# RF08indx.net
KiCad netlist of a schematic drawn in EAGLE
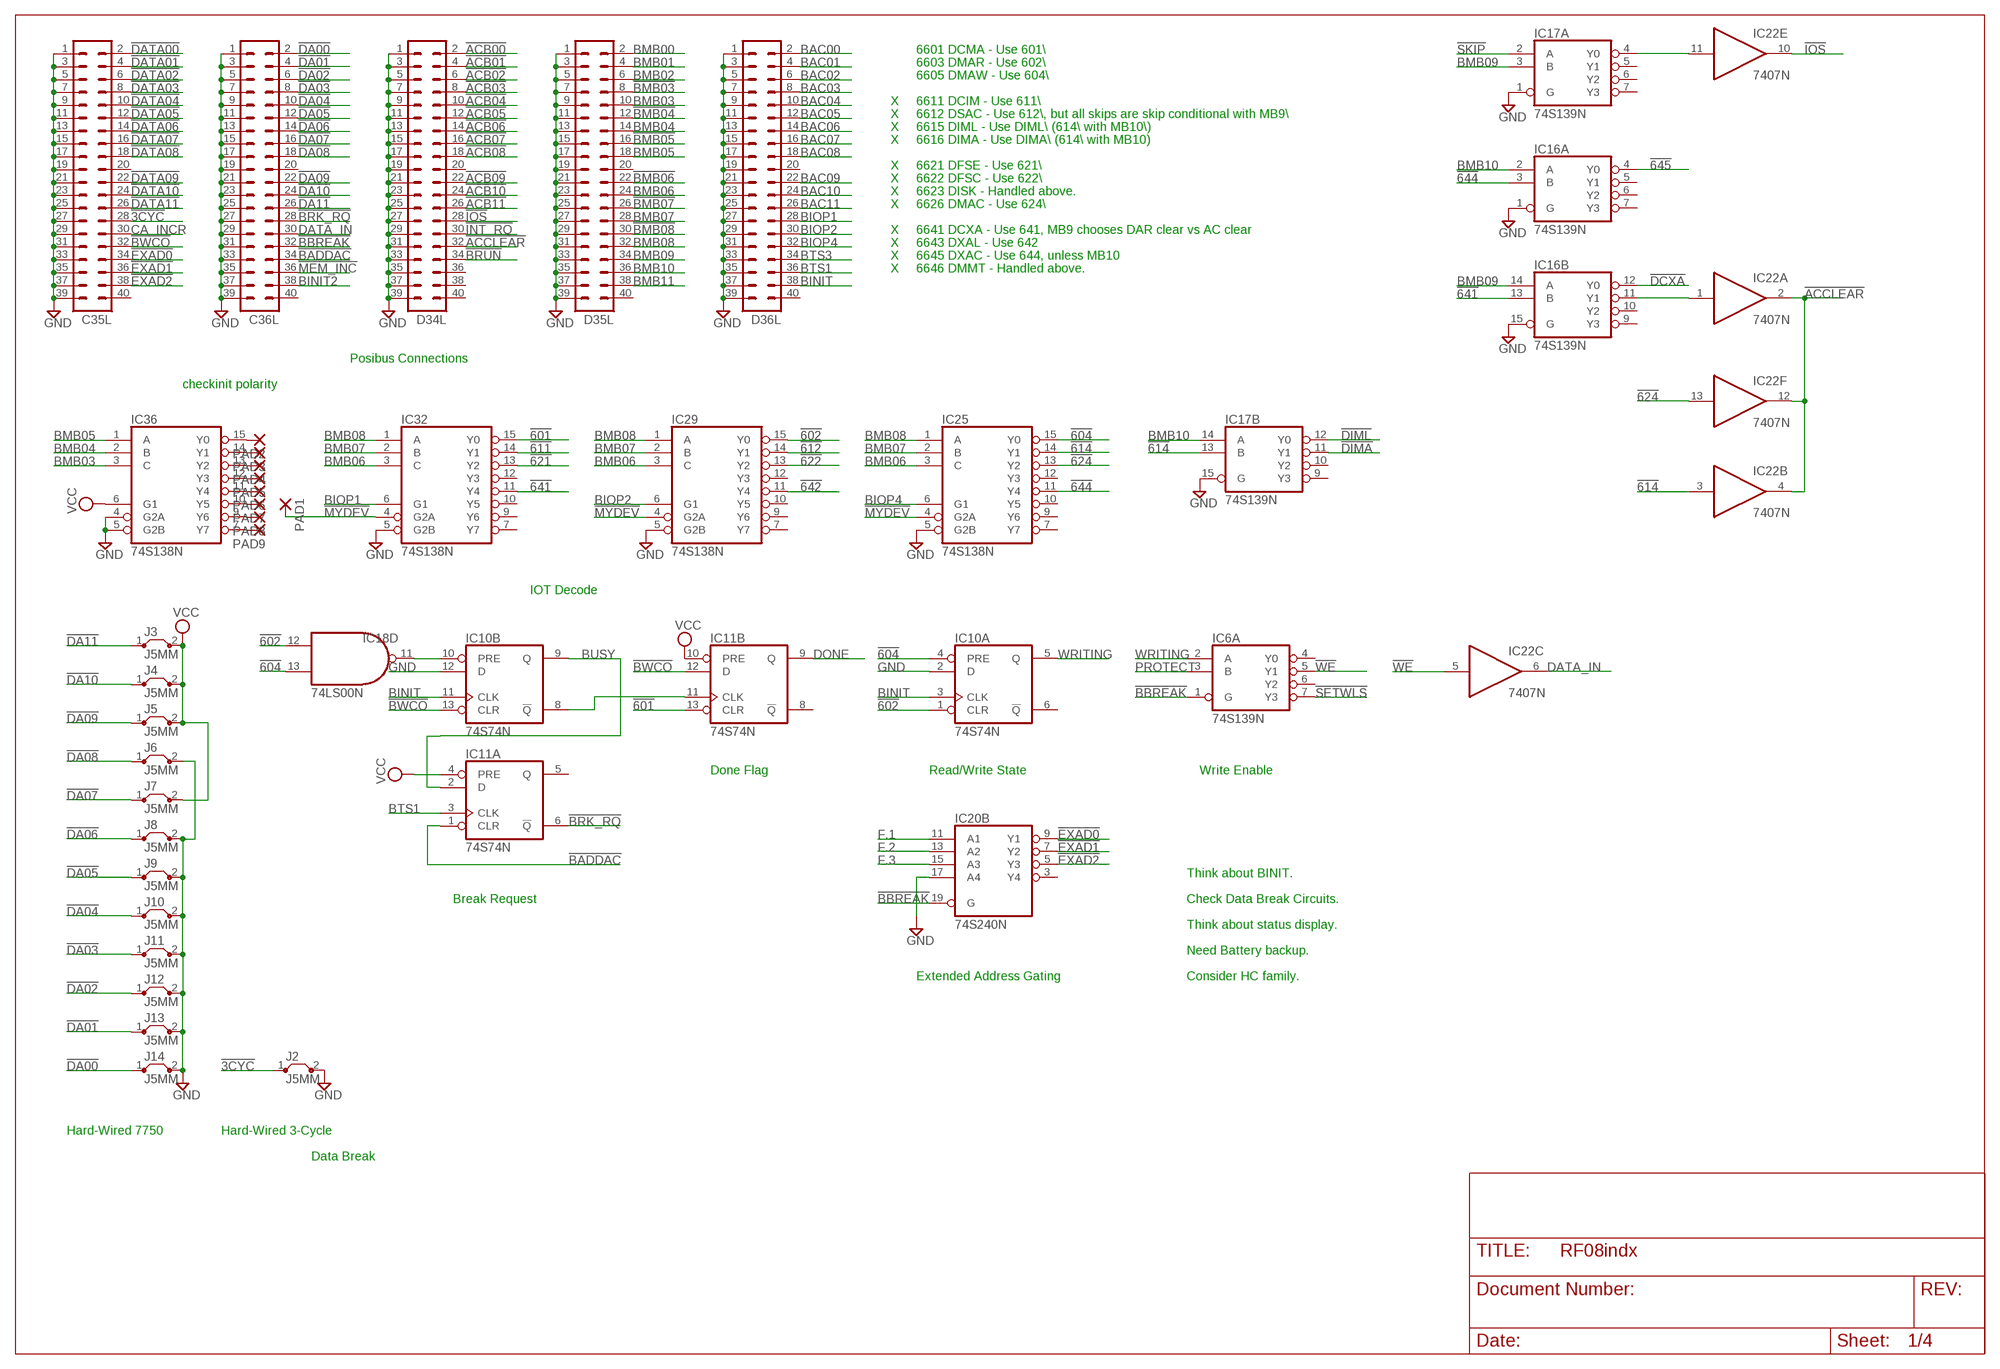
[diagram p0: schematic, sheet 1]
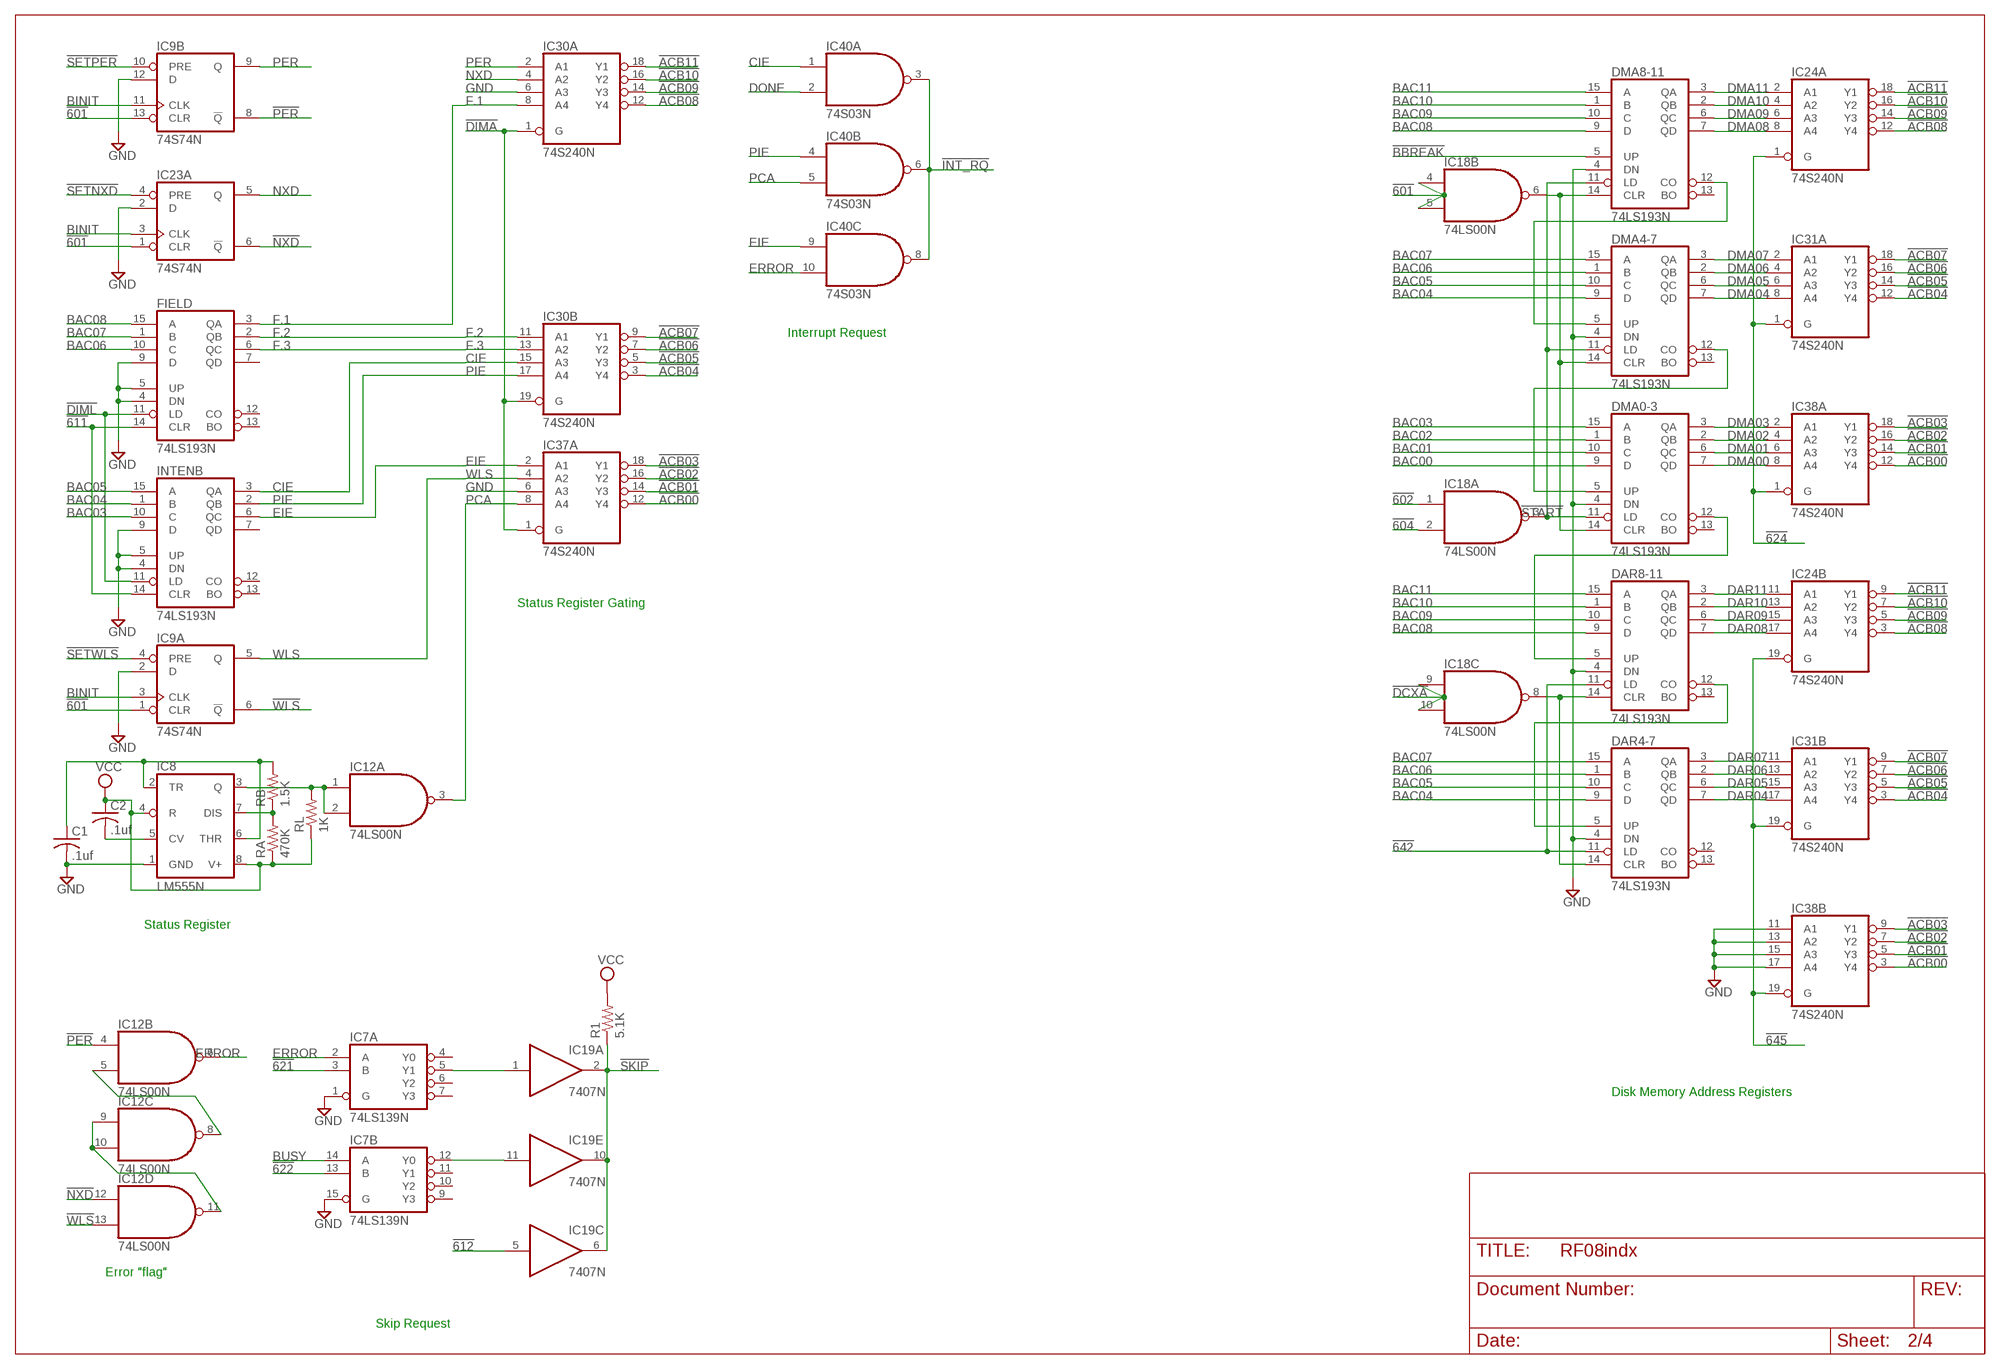
[diagram p1: schematic, sheet 2]
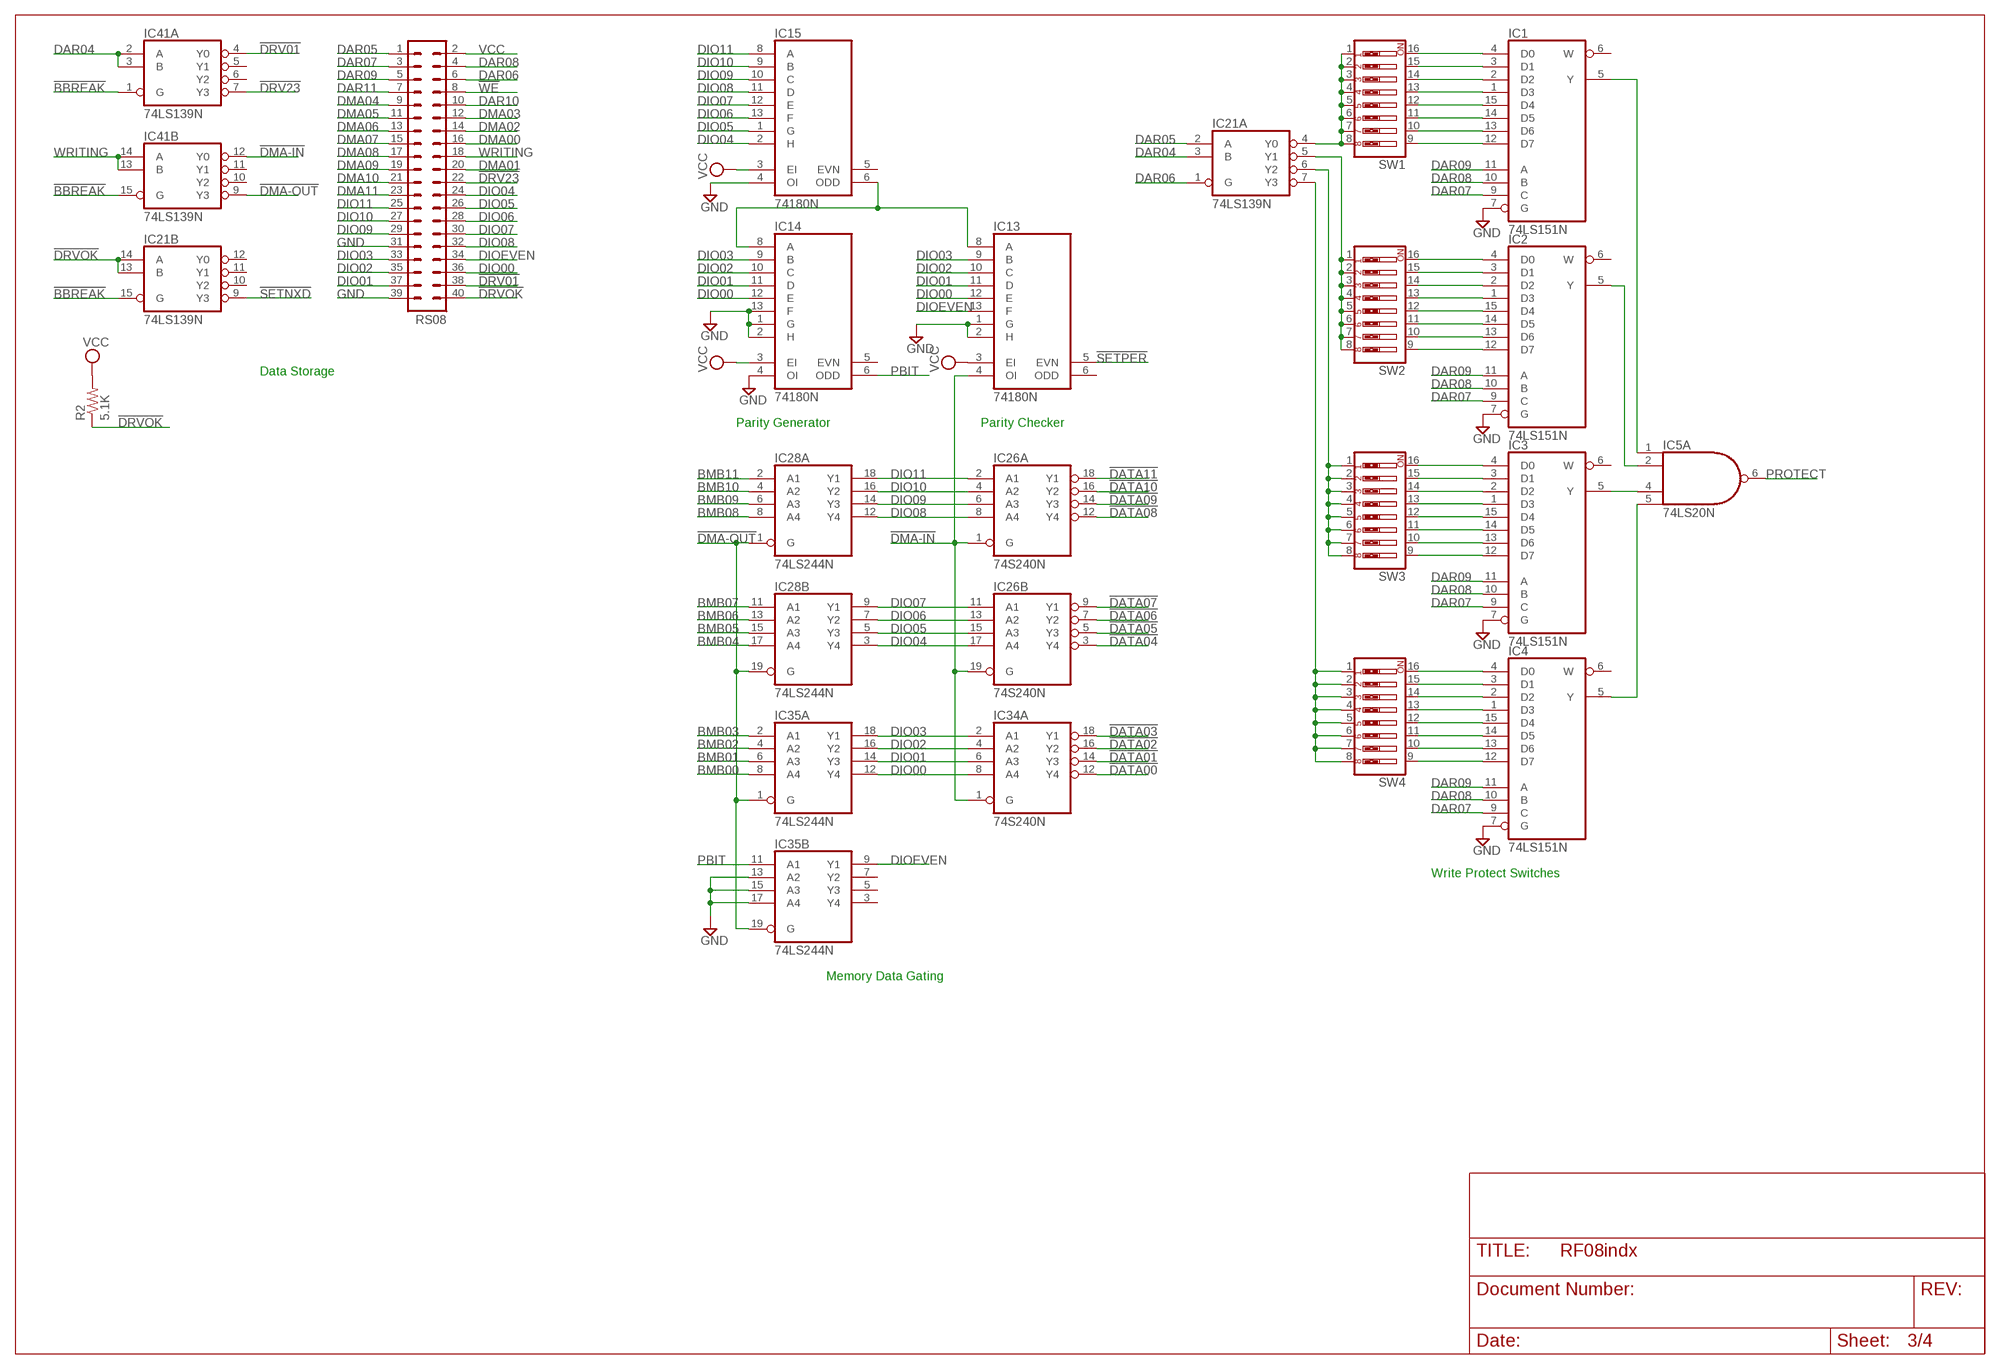
[diagram p2: schematic, sheet 3]
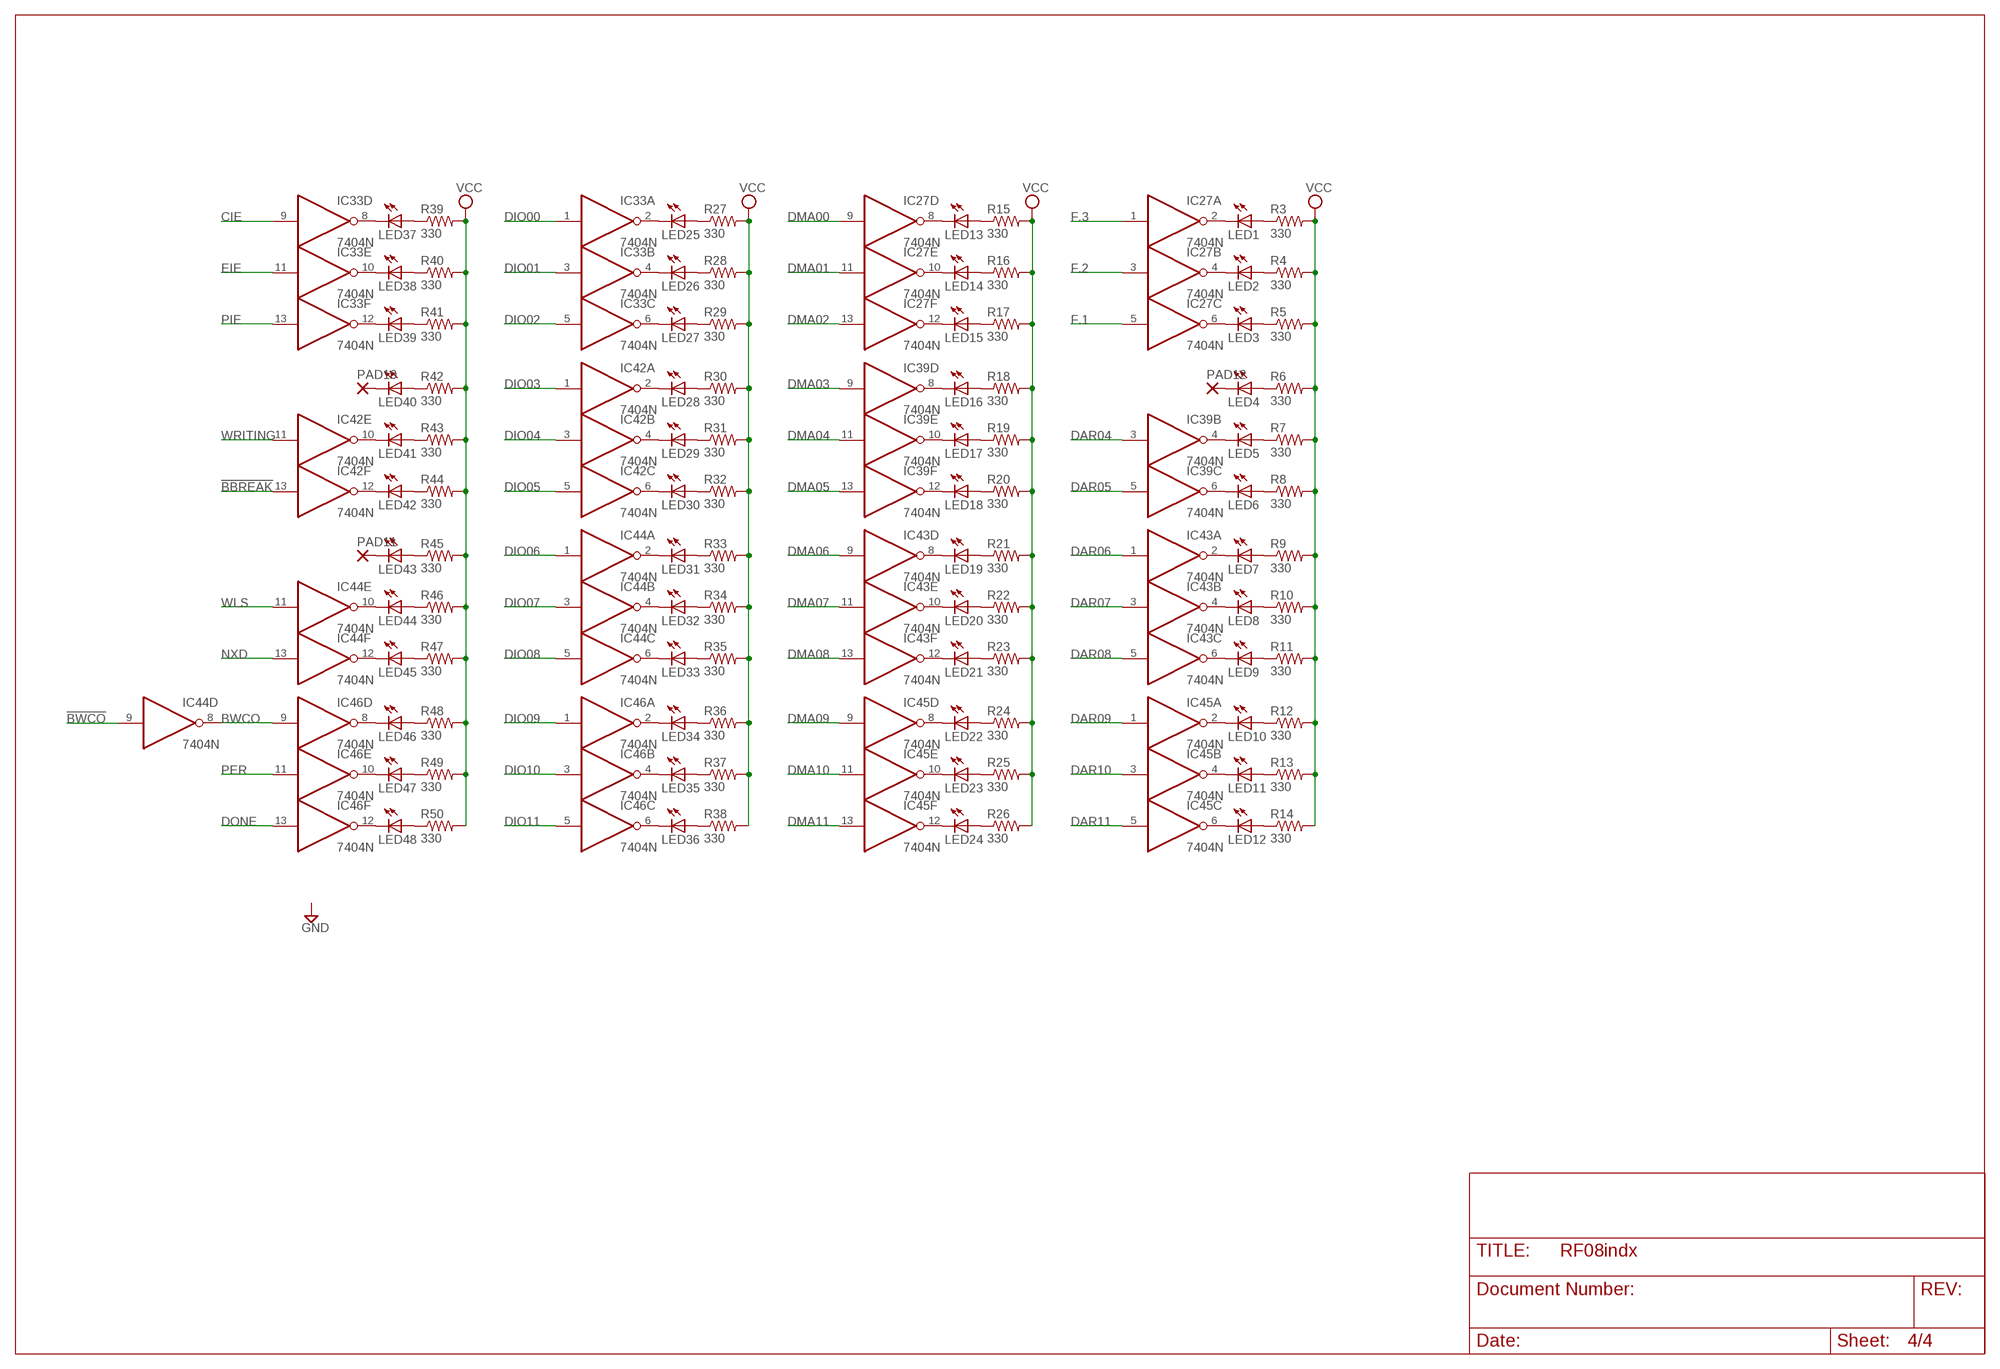
[diagram p3: schematic, sheet 4]

(export (version "E")
  (design (tool "Eeschema 10.0.6"))
  (components
    (comp (ref "C1")
      (value ".1uf")
      (footprint "eagle-import:C050-025X075")
      (libsource (lib "eagle-import") (part "C-US050-025X075"))
    )
    (comp (ref "C2")
      (value ".1uf")
      (footprint "eagle-import:C050-025X075")
      (libsource (lib "eagle-import") (part "C-US050-025X075"))
    )
    (comp (ref "DAR4-7")
      (value "74LS193N")
      (footprint "eagle-import:DIL16")
      (libsource (lib "eagle-import") (part "74192NLS"))
    )
    (comp (ref "DAR8-11")
      (value "74LS193N")
      (footprint "eagle-import:DIL16")
      (libsource (lib "eagle-import") (part "74192NLS"))
    )
    (comp (ref "DMA0-3")
      (value "74LS193N")
      (footprint "eagle-import:DIL16")
      (libsource (lib "eagle-import") (part "74192NLS"))
    )
    (comp (ref "DMA4-7")
      (value "74LS193N")
      (footprint "eagle-import:DIL16")
      (libsource (lib "eagle-import") (part "74192NLS"))
    )
    (comp (ref "DMA8-11")
      (value "74LS193N")
      (footprint "eagle-import:DIL16")
      (libsource (lib "eagle-import") (part "74192NLS"))
    )
    (comp (ref "FIELD")
      (value "74LS193N")
      (footprint "eagle-import:DIL16")
      (libsource (lib "eagle-import") (part "74192NLS"))
    )
    (comp (ref "IC7")
      (value "74LS139N")
      (footprint "eagle-import:DIL16")
      (libsource (lib "eagle-import") (part "74139NLS"))
    )
    (comp (ref "IC8")
      (value "LM555N")
      (footprint "eagle-import:DIL08")
      (libsource (lib "eagle-import") (part "555NLM"))
    )
    (comp (ref "IC9")
      (value "74S74N")
      (footprint "eagle-import:DIL14")
      (libsource (lib "eagle-import") (part "7474NS"))
    )
    (comp (ref "IC12")
      (value "74LS00N")
      (footprint "eagle-import:DIL14")
      (libsource (lib "eagle-import") (part "7400NLS"))
    )
    (comp (ref "IC18")
      (value "74LS00N")
      (footprint "eagle-import:DIL14")
      (libsource (lib "eagle-import") (part "7400NLS"))
    )
    (comp (ref "IC19")
      (value "7407N")
      (footprint "eagle-import:DIL14")
      (libsource (lib "eagle-import") (part "7407N"))
    )
    (comp (ref "IC23")
      (value "74S74N")
      (footprint "eagle-import:DIL14")
      (libsource (lib "eagle-import") (part "7474NS"))
    )
    (comp (ref "IC24")
      (value "74S240N")
      (footprint "eagle-import:DIL20")
      (libsource (lib "eagle-import") (part "74240NS"))
    )
    (comp (ref "IC30")
      (value "74S240N")
      (footprint "eagle-import:DIL20")
      (libsource (lib "eagle-import") (part "74240NS"))
    )
    (comp (ref "IC31")
      (value "74S240N")
      (footprint "eagle-import:DIL20")
      (libsource (lib "eagle-import") (part "74240NS"))
    )
    (comp (ref "IC37")
      (value "74S240N")
      (footprint "eagle-import:DIL20")
      (libsource (lib "eagle-import") (part "74240NS"))
    )
    (comp (ref "IC38")
      (value "74S240N")
      (footprint "eagle-import:DIL20")
      (libsource (lib "eagle-import") (part "74240NS"))
    )
    (comp (ref "IC40")
      (value "74S03N")
      (footprint "eagle-import:DIL14")
      (libsource (lib "eagle-import") (part "7403NS"))
    )
    (comp (ref "INTENB")
      (value "74LS193N")
      (footprint "eagle-import:DIL16")
      (libsource (lib "eagle-import") (part "74192NLS"))
    )
    (comp (ref "R1")
      (value "5.1K")
      (footprint "eagle-import:0207_10")
      (libsource (lib "eagle-import") (part "R-US_0207/10"))
    )
    (comp (ref "RA")
      (value "470K")
      (footprint "eagle-import:0207_10")
      (libsource (lib "eagle-import") (part "R-US_0207/10"))
    )
    (comp (ref "RB")
      (value "1.5K")
      (footprint "eagle-import:0207_10")
      (libsource (lib "eagle-import") (part "R-US_0207/10"))
    )
    (comp (ref "RL")
      (value "1K")
      (footprint "eagle-import:0207_10")
      (libsource (lib "eagle-import") (part "R-US_0207/10"))
    )
    (comp (ref "C35L")
      (value "MA20-2")
      (footprint "eagle-import:MA20-2")
      (libsource (lib "eagle-import") (part "MA20-2"))
    )
    (comp (ref "C36L")
      (value "MA20-2")
      (footprint "eagle-import:MA20-2")
      (libsource (lib "eagle-import") (part "MA20-2"))
    )
    (comp (ref "D34L")
      (value "MA20-2")
      (footprint "eagle-import:MA20-2")
      (libsource (lib "eagle-import") (part "MA20-2"))
    )
    (comp (ref "D35L")
      (value "MA20-2")
      (footprint "eagle-import:MA20-2")
      (libsource (lib "eagle-import") (part "MA20-2"))
    )
    (comp (ref "D36L")
      (value "MA20-2")
      (footprint "eagle-import:MA20-2")
      (libsource (lib "eagle-import") (part "MA20-2"))
    )
    (comp (ref "IC6")
      (value "74S139N")
      (footprint "eagle-import:DIL16")
      (libsource (lib "eagle-import") (part "74139NS"))
    )
    (comp (ref "IC10")
      (value "74S74N")
      (footprint "eagle-import:DIL14")
      (libsource (lib "eagle-import") (part "7474NS"))
    )
    (comp (ref "IC11")
      (value "74S74N")
      (footprint "eagle-import:DIL14")
      (libsource (lib "eagle-import") (part "7474NS"))
    )
    (comp (ref "IC16")
      (value "74S139N")
      (footprint "eagle-import:DIL16")
      (libsource (lib "eagle-import") (part "74139NS"))
    )
    (comp (ref "IC17")
      (value "74S139N")
      (footprint "eagle-import:DIL16")
      (libsource (lib "eagle-import") (part "74139NS"))
    )
    (comp (ref "IC20")
      (value "74S240N")
      (footprint "eagle-import:DIL20")
      (libsource (lib "eagle-import") (part "74240NS"))
    )
    (comp (ref "IC22")
      (value "7407N")
      (footprint "eagle-import:DIL14")
      (libsource (lib "eagle-import") (part "7407N"))
    )
    (comp (ref "IC25")
      (value "74S138N")
      (footprint "eagle-import:DIL16")
      (libsource (lib "eagle-import") (part "74138NS"))
    )
    (comp (ref "IC29")
      (value "74S138N")
      (footprint "eagle-import:DIL16")
      (libsource (lib "eagle-import") (part "74138NS"))
    )
    (comp (ref "IC32")
      (value "74S138N")
      (footprint "eagle-import:DIL16")
      (libsource (lib "eagle-import") (part "74138NS"))
    )
    (comp (ref "IC36")
      (value "74S138N")
      (footprint "eagle-import:DIL16")
      (libsource (lib "eagle-import") (part "74138NS"))
    )
    (comp (ref "J2")
      (value "J5MM")
      (footprint "eagle-import:05")
      (libsource (lib "eagle-import") (part "J5MM"))
    )
    (comp (ref "J3")
      (value "J5MM")
      (footprint "eagle-import:05")
      (libsource (lib "eagle-import") (part "J5MM"))
    )
    (comp (ref "J4")
      (value "J5MM")
      (footprint "eagle-import:05")
      (libsource (lib "eagle-import") (part "J5MM"))
    )
    (comp (ref "J5")
      (value "J5MM")
      (footprint "eagle-import:05")
      (libsource (lib "eagle-import") (part "J5MM"))
    )
    (comp (ref "J6")
      (value "J5MM")
      (footprint "eagle-import:05")
      (libsource (lib "eagle-import") (part "J5MM"))
    )
    (comp (ref "J7")
      (value "J5MM")
      (footprint "eagle-import:05")
      (libsource (lib "eagle-import") (part "J5MM"))
    )
    (comp (ref "J8")
      (value "J5MM")
      (footprint "eagle-import:05")
      (libsource (lib "eagle-import") (part "J5MM"))
    )
    (comp (ref "J9")
      (value "J5MM")
      (footprint "eagle-import:05")
      (libsource (lib "eagle-import") (part "J5MM"))
    )
    (comp (ref "J10")
      (value "J5MM")
      (footprint "eagle-import:05")
      (libsource (lib "eagle-import") (part "J5MM"))
    )
    (comp (ref "J11")
      (value "J5MM")
      (footprint "eagle-import:05")
      (libsource (lib "eagle-import") (part "J5MM"))
    )
    (comp (ref "J12")
      (value "J5MM")
      (footprint "eagle-import:05")
      (libsource (lib "eagle-import") (part "J5MM"))
    )
    (comp (ref "J13")
      (value "J5MM")
      (footprint "eagle-import:05")
      (libsource (lib "eagle-import") (part "J5MM"))
    )
    (comp (ref "J14")
      (value "J5MM")
      (footprint "eagle-import:05")
      (libsource (lib "eagle-import") (part "J5MM"))
    )
    (comp (ref "PAD1")
      (value "1,6/0,8")
      (footprint "eagle-import:1,6_0,8")
      (libsource (lib "eagle-import") (part "1,6/0,8"))
    )
    (comp (ref "PAD2")
      (value "1,6/0,8")
      (footprint "eagle-import:1,6_0,8")
      (libsource (lib "eagle-import") (part "1,6/0,8"))
    )
    (comp (ref "PAD3")
      (value "1,6/0,8")
      (footprint "eagle-import:1,6_0,8")
      (libsource (lib "eagle-import") (part "1,6/0,8"))
    )
    (comp (ref "PAD4")
      (value "1,6/0,8")
      (footprint "eagle-import:1,6_0,8")
      (libsource (lib "eagle-import") (part "1,6/0,8"))
    )
    (comp (ref "PAD5")
      (value "1,6/0,8")
      (footprint "eagle-import:1,6_0,8")
      (libsource (lib "eagle-import") (part "1,6/0,8"))
    )
    (comp (ref "PAD6")
      (value "1,6/0,8")
      (footprint "eagle-import:1,6_0,8")
      (libsource (lib "eagle-import") (part "1,6/0,8"))
    )
    (comp (ref "PAD7")
      (value "1,6/0,8")
      (footprint "eagle-import:1,6_0,8")
      (libsource (lib "eagle-import") (part "1,6/0,8"))
    )
    (comp (ref "PAD8")
      (value "1,6/0,8")
      (footprint "eagle-import:1,6_0,8")
      (libsource (lib "eagle-import") (part "1,6/0,8"))
    )
    (comp (ref "PAD9")
      (value "1,6/0,8")
      (footprint "eagle-import:1,6_0,8")
      (libsource (lib "eagle-import") (part "1,6/0,8"))
    )
    (comp (ref "IC1")
      (value "74LS151N")
      (footprint "eagle-import:DIL16")
      (libsource (lib "eagle-import") (part "74151NLS"))
    )
    (comp (ref "IC2")
      (value "74LS151N")
      (footprint "eagle-import:DIL16")
      (libsource (lib "eagle-import") (part "74151NLS"))
    )
    (comp (ref "IC3")
      (value "74LS151N")
      (footprint "eagle-import:DIL16")
      (libsource (lib "eagle-import") (part "74151NLS"))
    )
    (comp (ref "IC4")
      (value "74LS151N")
      (footprint "eagle-import:DIL16")
      (libsource (lib "eagle-import") (part "74151NLS"))
    )
    (comp (ref "IC5")
      (value "74LS20N")
      (footprint "eagle-import:DIL14")
      (libsource (lib "eagle-import") (part "7420NLS"))
    )
    (comp (ref "IC13")
      (value "74180N")
      (footprint "eagle-import:DIL14")
      (libsource (lib "eagle-import") (part "74180N"))
    )
    (comp (ref "IC14")
      (value "74180N")
      (footprint "eagle-import:DIL14")
      (libsource (lib "eagle-import") (part "74180N"))
    )
    (comp (ref "IC15")
      (value "74180N")
      (footprint "eagle-import:DIL14")
      (libsource (lib "eagle-import") (part "74180N"))
    )
    (comp (ref "IC21")
      (value "74LS139N")
      (footprint "eagle-import:DIL16")
      (libsource (lib "eagle-import") (part "74139NLS"))
    )
    (comp (ref "IC26")
      (value "74S240N")
      (footprint "eagle-import:DIL20")
      (libsource (lib "eagle-import") (part "74240NS"))
    )
    (comp (ref "IC28")
      (value "74LS244N")
      (footprint "eagle-import:DIL20")
      (libsource (lib "eagle-import") (part "74244NLS"))
    )
    (comp (ref "IC34")
      (value "74S240N")
      (footprint "eagle-import:DIL20")
      (libsource (lib "eagle-import") (part "74240NS"))
    )
    (comp (ref "IC35")
      (value "74LS244N")
      (footprint "eagle-import:DIL20")
      (libsource (lib "eagle-import") (part "74244NLS"))
    )
    (comp (ref "IC41")
      (value "74LS139N")
      (footprint "eagle-import:DIL16")
      (libsource (lib "eagle-import") (part "74139NLS"))
    )
    (comp (ref "R2")
      (value "5.1K")
      (footprint "eagle-import:0207_10")
      (libsource (lib "eagle-import") (part "R-US_0207/10"))
    )
    (comp (ref "RS08")
      (value "MA20-2")
      (footprint "eagle-import:MA20-2")
      (libsource (lib "eagle-import") (part "MA20-2"))
    )
    (comp (ref "SW1")
      (value "SW_DIP-8")
      (footprint "eagle-import:EDG-08")
      (libsource (lib "eagle-import") (part "SW_DIP-8"))
    )
    (comp (ref "SW2")
      (value "SW_DIP-8")
      (footprint "eagle-import:EDG-08")
      (libsource (lib "eagle-import") (part "SW_DIP-8"))
    )
    (comp (ref "SW3")
      (value "SW_DIP-8")
      (footprint "eagle-import:EDG-08")
      (libsource (lib "eagle-import") (part "SW_DIP-8"))
    )
    (comp (ref "SW4")
      (value "SW_DIP-8")
      (footprint "eagle-import:EDG-08")
      (libsource (lib "eagle-import") (part "SW_DIP-8"))
    )
    (comp (ref "IC27")
      (value "7404N")
      (footprint "eagle-import:DIL14")
      (libsource (lib "eagle-import") (part "7404N"))
    )
    (comp (ref "IC33")
      (value "7404N")
      (footprint "eagle-import:DIL14")
      (libsource (lib "eagle-import") (part "7404N"))
    )
    (comp (ref "IC39")
      (value "7404N")
      (footprint "eagle-import:DIL14")
      (libsource (lib "eagle-import") (part "7404N"))
    )
    (comp (ref "IC42")
      (value "7404N")
      (footprint "eagle-import:DIL14")
      (libsource (lib "eagle-import") (part "7404N"))
    )
    (comp (ref "IC43")
      (value "7404N")
      (footprint "eagle-import:DIL14")
      (libsource (lib "eagle-import") (part "7404N"))
    )
    (comp (ref "IC44")
      (value "7404N")
      (footprint "eagle-import:DIL14")
      (libsource (lib "eagle-import") (part "7404N"))
    )
    (comp (ref "IC45")
      (value "7404N")
      (footprint "eagle-import:DIL14")
      (libsource (lib "eagle-import") (part "7404N"))
    )
    (comp (ref "IC46")
      (value "7404N")
      (footprint "eagle-import:DIL14")
      (libsource (lib "eagle-import") (part "7404N"))
    )
    (comp (ref "LED1")
      (value "LED5MM")
      (footprint "eagle-import:LED5MM")
      (libsource (lib "eagle-import") (part "LED5MM"))
    )
    (comp (ref "LED2")
      (value "LED5MM")
      (footprint "eagle-import:LED5MM")
      (libsource (lib "eagle-import") (part "LED5MM"))
    )
    (comp (ref "LED3")
      (value "LED5MM")
      (footprint "eagle-import:LED5MM")
      (libsource (lib "eagle-import") (part "LED5MM"))
    )
    (comp (ref "LED4")
      (value "LED5MM")
      (footprint "eagle-import:LED5MM")
      (libsource (lib "eagle-import") (part "LED5MM"))
    )
    (comp (ref "LED5")
      (value "LED5MM")
      (footprint "eagle-import:LED5MM")
      (libsource (lib "eagle-import") (part "LED5MM"))
    )
    (comp (ref "LED6")
      (value "LED5MM")
      (footprint "eagle-import:LED5MM")
      (libsource (lib "eagle-import") (part "LED5MM"))
    )
    (comp (ref "LED7")
      (value "LED5MM")
      (footprint "eagle-import:LED5MM")
      (libsource (lib "eagle-import") (part "LED5MM"))
    )
    (comp (ref "LED8")
      (value "LED5MM")
      (footprint "eagle-import:LED5MM")
      (libsource (lib "eagle-import") (part "LED5MM"))
    )
    (comp (ref "LED9")
      (value "LED5MM")
      (footprint "eagle-import:LED5MM")
      (libsource (lib "eagle-import") (part "LED5MM"))
    )
    (comp (ref "LED10")
      (value "LED5MM")
      (footprint "eagle-import:LED5MM")
      (libsource (lib "eagle-import") (part "LED5MM"))
    )
    (comp (ref "LED11")
      (value "LED5MM")
      (footprint "eagle-import:LED5MM")
      (libsource (lib "eagle-import") (part "LED5MM"))
    )
    (comp (ref "LED12")
      (value "LED5MM")
      (footprint "eagle-import:LED5MM")
      (libsource (lib "eagle-import") (part "LED5MM"))
    )
    (comp (ref "LED13")
      (value "LED5MM")
      (footprint "eagle-import:LED5MM")
      (libsource (lib "eagle-import") (part "LED5MM"))
    )
    (comp (ref "LED14")
      (value "LED5MM")
      (footprint "eagle-import:LED5MM")
      (libsource (lib "eagle-import") (part "LED5MM"))
    )
    (comp (ref "LED15")
      (value "LED5MM")
      (footprint "eagle-import:LED5MM")
      (libsource (lib "eagle-import") (part "LED5MM"))
    )
    (comp (ref "LED16")
      (value "LED5MM")
      (footprint "eagle-import:LED5MM")
      (libsource (lib "eagle-import") (part "LED5MM"))
    )
    (comp (ref "LED17")
      (value "LED5MM")
      (footprint "eagle-import:LED5MM")
      (libsource (lib "eagle-import") (part "LED5MM"))
    )
    (comp (ref "LED18")
      (value "LED5MM")
      (footprint "eagle-import:LED5MM")
      (libsource (lib "eagle-import") (part "LED5MM"))
    )
    (comp (ref "LED19")
      (value "LED5MM")
      (footprint "eagle-import:LED5MM")
      (libsource (lib "eagle-import") (part "LED5MM"))
    )
    (comp (ref "LED20")
      (value "LED5MM")
      (footprint "eagle-import:LED5MM")
      (libsource (lib "eagle-import") (part "LED5MM"))
    )
    (comp (ref "LED21")
      (value "LED5MM")
      (footprint "eagle-import:LED5MM")
      (libsource (lib "eagle-import") (part "LED5MM"))
    )
    (comp (ref "LED22")
      (value "LED5MM")
      (footprint "eagle-import:LED5MM")
      (libsource (lib "eagle-import") (part "LED5MM"))
    )
    (comp (ref "LED23")
      (value "LED5MM")
      (footprint "eagle-import:LED5MM")
      (libsource (lib "eagle-import") (part "LED5MM"))
    )
    (comp (ref "LED24")
      (value "LED5MM")
      (footprint "eagle-import:LED5MM")
      (libsource (lib "eagle-import") (part "LED5MM"))
    )
    (comp (ref "LED25")
      (value "LED5MM")
      (footprint "eagle-import:LED5MM")
      (libsource (lib "eagle-import") (part "LED5MM"))
    )
    (comp (ref "LED26")
      (value "LED5MM")
      (footprint "eagle-import:LED5MM")
      (libsource (lib "eagle-import") (part "LED5MM"))
    )
    (comp (ref "LED27")
      (value "LED5MM")
      (footprint "eagle-import:LED5MM")
      (libsource (lib "eagle-import") (part "LED5MM"))
    )
    (comp (ref "LED28")
      (value "LED5MM")
      (footprint "eagle-import:LED5MM")
      (libsource (lib "eagle-import") (part "LED5MM"))
    )
    (comp (ref "LED29")
      (value "LED5MM")
      (footprint "eagle-import:LED5MM")
      (libsource (lib "eagle-import") (part "LED5MM"))
    )
    (comp (ref "LED30")
      (value "LED5MM")
      (footprint "eagle-import:LED5MM")
      (libsource (lib "eagle-import") (part "LED5MM"))
    )
    (comp (ref "LED31")
      (value "LED5MM")
      (footprint "eagle-import:LED5MM")
      (libsource (lib "eagle-import") (part "LED5MM"))
    )
    (comp (ref "LED32")
      (value "LED5MM")
      (footprint "eagle-import:LED5MM")
      (libsource (lib "eagle-import") (part "LED5MM"))
    )
    (comp (ref "LED33")
      (value "LED5MM")
      (footprint "eagle-import:LED5MM")
      (libsource (lib "eagle-import") (part "LED5MM"))
    )
    (comp (ref "LED34")
      (value "LED5MM")
      (footprint "eagle-import:LED5MM")
      (libsource (lib "eagle-import") (part "LED5MM"))
    )
    (comp (ref "LED35")
      (value "LED5MM")
      (footprint "eagle-import:LED5MM")
      (libsource (lib "eagle-import") (part "LED5MM"))
    )
    (comp (ref "LED36")
      (value "LED5MM")
      (footprint "eagle-import:LED5MM")
      (libsource (lib "eagle-import") (part "LED5MM"))
    )
    (comp (ref "LED37")
      (value "LED5MM")
      (footprint "eagle-import:LED5MM")
      (libsource (lib "eagle-import") (part "LED5MM"))
    )
    (comp (ref "LED38")
      (value "LED5MM")
      (footprint "eagle-import:LED5MM")
      (libsource (lib "eagle-import") (part "LED5MM"))
    )
    (comp (ref "LED39")
      (value "LED5MM")
      (footprint "eagle-import:LED5MM")
      (libsource (lib "eagle-import") (part "LED5MM"))
    )
    (comp (ref "LED40")
      (value "LED5MM")
      (footprint "eagle-import:LED5MM")
      (libsource (lib "eagle-import") (part "LED5MM"))
    )
    (comp (ref "LED41")
      (value "LED5MM")
      (footprint "eagle-import:LED5MM")
      (libsource (lib "eagle-import") (part "LED5MM"))
    )
    (comp (ref "LED42")
      (value "LED5MM")
      (footprint "eagle-import:LED5MM")
      (libsource (lib "eagle-import") (part "LED5MM"))
    )
    (comp (ref "LED43")
      (value "LED5MM")
      (footprint "eagle-import:LED5MM")
      (libsource (lib "eagle-import") (part "LED5MM"))
    )
    (comp (ref "LED44")
      (value "LED5MM")
      (footprint "eagle-import:LED5MM")
      (libsource (lib "eagle-import") (part "LED5MM"))
    )
    (comp (ref "LED45")
      (value "LED5MM")
      (footprint "eagle-import:LED5MM")
      (libsource (lib "eagle-import") (part "LED5MM"))
    )
    (comp (ref "LED46")
      (value "LED5MM")
      (footprint "eagle-import:LED5MM")
      (libsource (lib "eagle-import") (part "LED5MM"))
    )
    (comp (ref "LED47")
      (value "LED5MM")
      (footprint "eagle-import:LED5MM")
      (libsource (lib "eagle-import") (part "LED5MM"))
    )
    (comp (ref "LED48")
      (value "LED5MM")
      (footprint "eagle-import:LED5MM")
      (libsource (lib "eagle-import") (part "LED5MM"))
    )
    (comp (ref "PAD10")
      (value "1,6/0,8")
      (footprint "eagle-import:1,6_0,8")
      (libsource (lib "eagle-import") (part "1,6/0,8"))
    )
    (comp (ref "PAD11")
      (value "1,6/0,8")
      (footprint "eagle-import:1,6_0,8")
      (libsource (lib "eagle-import") (part "1,6/0,8"))
    )
    (comp (ref "PAD12")
      (value "1,6/0,8")
      (footprint "eagle-import:1,6_0,8")
      (libsource (lib "eagle-import") (part "1,6/0,8"))
    )
    (comp (ref "R3")
      (value "330")
      (footprint "eagle-import:0207_10")
      (libsource (lib "eagle-import") (part "R-US_0207/10"))
    )
    (comp (ref "R4")
      (value "330")
      (footprint "eagle-import:0207_10")
      (libsource (lib "eagle-import") (part "R-US_0207/10"))
    )
    (comp (ref "R5")
      (value "330")
      (footprint "eagle-import:0207_10")
      (libsource (lib "eagle-import") (part "R-US_0207/10"))
    )
    (comp (ref "R6")
      (value "330")
      (footprint "eagle-import:0207_10")
      (libsource (lib "eagle-import") (part "R-US_0207/10"))
    )
    (comp (ref "R7")
      (value "330")
      (footprint "eagle-import:0207_10")
      (libsource (lib "eagle-import") (part "R-US_0207/10"))
    )
    (comp (ref "R8")
      (value "330")
      (footprint "eagle-import:0207_10")
      (libsource (lib "eagle-import") (part "R-US_0207/10"))
    )
    (comp (ref "R9")
      (value "330")
      (footprint "eagle-import:0207_10")
      (libsource (lib "eagle-import") (part "R-US_0207/10"))
    )
    (comp (ref "R10")
      (value "330")
      (footprint "eagle-import:0207_10")
      (libsource (lib "eagle-import") (part "R-US_0207/10"))
    )
    (comp (ref "R11")
      (value "330")
      (footprint "eagle-import:0207_10")
      (libsource (lib "eagle-import") (part "R-US_0207/10"))
    )
    (comp (ref "R12")
      (value "330")
      (footprint "eagle-import:0207_10")
      (libsource (lib "eagle-import") (part "R-US_0207/10"))
    )
    (comp (ref "R13")
      (value "330")
      (footprint "eagle-import:0207_10")
      (libsource (lib "eagle-import") (part "R-US_0207/10"))
    )
    (comp (ref "R14")
      (value "330")
      (footprint "eagle-import:0207_10")
      (libsource (lib "eagle-import") (part "R-US_0207/10"))
    )
    (comp (ref "R15")
      (value "330")
      (footprint "eagle-import:0207_10")
      (libsource (lib "eagle-import") (part "R-US_0207/10"))
    )
    (comp (ref "R16")
      (value "330")
      (footprint "eagle-import:0207_10")
      (libsource (lib "eagle-import") (part "R-US_0207/10"))
    )
    (comp (ref "R17")
      (value "330")
      (footprint "eagle-import:0207_10")
      (libsource (lib "eagle-import") (part "R-US_0207/10"))
    )
    (comp (ref "R18")
      (value "330")
      (footprint "eagle-import:0207_10")
      (libsource (lib "eagle-import") (part "R-US_0207/10"))
    )
    (comp (ref "R19")
      (value "330")
      (footprint "eagle-import:0207_10")
      (libsource (lib "eagle-import") (part "R-US_0207/10"))
    )
    (comp (ref "R20")
      (value "330")
      (footprint "eagle-import:0207_10")
      (libsource (lib "eagle-import") (part "R-US_0207/10"))
    )
    (comp (ref "R21")
      (value "330")
      (footprint "eagle-import:0207_10")
      (libsource (lib "eagle-import") (part "R-US_0207/10"))
    )
    (comp (ref "R22")
      (value "330")
      (footprint "eagle-import:0207_10")
      (libsource (lib "eagle-import") (part "R-US_0207/10"))
    )
    (comp (ref "R23")
      (value "330")
      (footprint "eagle-import:0207_10")
      (libsource (lib "eagle-import") (part "R-US_0207/10"))
    )
    (comp (ref "R24")
      (value "330")
      (footprint "eagle-import:0207_10")
      (libsource (lib "eagle-import") (part "R-US_0207/10"))
    )
    (comp (ref "R25")
      (value "330")
      (footprint "eagle-import:0207_10")
      (libsource (lib "eagle-import") (part "R-US_0207/10"))
    )
    (comp (ref "R26")
      (value "330")
      (footprint "eagle-import:0207_10")
      (libsource (lib "eagle-import") (part "R-US_0207/10"))
    )
    (comp (ref "R27")
      (value "330")
      (footprint "eagle-import:0207_10")
      (libsource (lib "eagle-import") (part "R-US_0207/10"))
    )
    (comp (ref "R28")
      (value "330")
      (footprint "eagle-import:0207_10")
      (libsource (lib "eagle-import") (part "R-US_0207/10"))
    )
    (comp (ref "R29")
      (value "330")
      (footprint "eagle-import:0207_10")
      (libsource (lib "eagle-import") (part "R-US_0207/10"))
    )
    (comp (ref "R30")
      (value "330")
      (footprint "eagle-import:0207_10")
      (libsource (lib "eagle-import") (part "R-US_0207/10"))
    )
    (comp (ref "R31")
      (value "330")
      (footprint "eagle-import:0207_10")
      (libsource (lib "eagle-import") (part "R-US_0207/10"))
    )
    (comp (ref "R32")
      (value "330")
      (footprint "eagle-import:0207_10")
      (libsource (lib "eagle-import") (part "R-US_0207/10"))
    )
    (comp (ref "R33")
      (value "330")
      (footprint "eagle-import:0207_10")
      (libsource (lib "eagle-import") (part "R-US_0207/10"))
    )
    (comp (ref "R34")
      (value "330")
      (footprint "eagle-import:0207_10")
      (libsource (lib "eagle-import") (part "R-US_0207/10"))
    )
    (comp (ref "R35")
      (value "330")
      (footprint "eagle-import:0207_10")
      (libsource (lib "eagle-import") (part "R-US_0207/10"))
    )
    (comp (ref "R36")
      (value "330")
      (footprint "eagle-import:0207_10")
      (libsource (lib "eagle-import") (part "R-US_0207/10"))
    )
    (comp (ref "R37")
      (value "330")
      (footprint "eagle-import:0207_10")
      (libsource (lib "eagle-import") (part "R-US_0207/10"))
    )
    (comp (ref "R38")
      (value "330")
      (footprint "eagle-import:0207_10")
      (libsource (lib "eagle-import") (part "R-US_0207/10"))
    )
    (comp (ref "R39")
      (value "330")
      (footprint "eagle-import:0207_10")
      (libsource (lib "eagle-import") (part "R-US_0207/10"))
    )
    (comp (ref "R40")
      (value "330")
      (footprint "eagle-import:0207_10")
      (libsource (lib "eagle-import") (part "R-US_0207/10"))
    )
    (comp (ref "R41")
      (value "330")
      (footprint "eagle-import:0207_10")
      (libsource (lib "eagle-import") (part "R-US_0207/10"))
    )
    (comp (ref "R42")
      (value "330")
      (footprint "eagle-import:0207_10")
      (libsource (lib "eagle-import") (part "R-US_0207/10"))
    )
    (comp (ref "R43")
      (value "330")
      (footprint "eagle-import:0207_10")
      (libsource (lib "eagle-import") (part "R-US_0207/10"))
    )
    (comp (ref "R44")
      (value "330")
      (footprint "eagle-import:0207_10")
      (libsource (lib "eagle-import") (part "R-US_0207/10"))
    )
    (comp (ref "R45")
      (value "330")
      (footprint "eagle-import:0207_10")
      (libsource (lib "eagle-import") (part "R-US_0207/10"))
    )
    (comp (ref "R46")
      (value "330")
      (footprint "eagle-import:0207_10")
      (libsource (lib "eagle-import") (part "R-US_0207/10"))
    )
    (comp (ref "R47")
      (value "330")
      (footprint "eagle-import:0207_10")
      (libsource (lib "eagle-import") (part "R-US_0207/10"))
    )
    (comp (ref "R48")
      (value "330")
      (footprint "eagle-import:0207_10")
      (libsource (lib "eagle-import") (part "R-US_0207/10"))
    )
    (comp (ref "R49")
      (value "330")
      (footprint "eagle-import:0207_10")
      (libsource (lib "eagle-import") (part "R-US_0207/10"))
    )
    (comp (ref "R50")
      (value "330")
      (footprint "eagle-import:0207_10")
      (libsource (lib "eagle-import") (part "R-US_0207/10"))
    )
  )
  (nets
    (net (code "1") (name "BAC00") (class "Default")
      (node (ref "D36L") (pin "2") (pinfunction "2_2") (pintype "passive"))
      (node (ref "DMA0-3") (pin "9") (pinfunction "D_9") (pintype "input"))
    )
    (net (code "2") (name "BAC01") (class "Default")
      (node (ref "D36L") (pin "4") (pinfunction "4_4") (pintype "passive"))
      (node (ref "DMA0-3") (pin "10") (pinfunction "C_10") (pintype "input"))
    )
    (net (code "3") (name "BAC02") (class "Default")
      (node (ref "D36L") (pin "6") (pinfunction "6_6") (pintype "passive"))
      (node (ref "DMA0-3") (pin "1") (pinfunction "B_1") (pintype "input"))
    )
    (net (code "4") (name "BAC03") (class "Default")
      (node (ref "D36L") (pin "8") (pinfunction "8_8") (pintype "passive"))
      (node (ref "DMA0-3") (pin "15") (pinfunction "A_15") (pintype "input"))
      (node (ref "INTENB") (pin "10") (pinfunction "C_10") (pintype "input"))
    )
    (net (code "5") (name "BAC04") (class "Default")
      (node (ref "D36L") (pin "10") (pinfunction "10_10") (pintype "passive"))
      (node (ref "DAR4-7") (pin "9") (pinfunction "D_9") (pintype "input"))
      (node (ref "DMA4-7") (pin "9") (pinfunction "D_9") (pintype "input"))
      (node (ref "INTENB") (pin "1") (pinfunction "B_1") (pintype "input"))
    )
    (net (code "6") (name "BAC05") (class "Default")
      (node (ref "D36L") (pin "12") (pinfunction "12_12") (pintype "passive"))
      (node (ref "DAR4-7") (pin "10") (pinfunction "C_10") (pintype "input"))
      (node (ref "DMA4-7") (pin "10") (pinfunction "C_10") (pintype "input"))
      (node (ref "INTENB") (pin "15") (pinfunction "A_15") (pintype "input"))
    )
    (net (code "7") (name "BAC06") (class "Default")
      (node (ref "D36L") (pin "14") (pinfunction "14_14") (pintype "passive"))
      (node (ref "DAR4-7") (pin "1") (pinfunction "B_1") (pintype "input"))
      (node (ref "DMA4-7") (pin "1") (pinfunction "B_1") (pintype "input"))
      (node (ref "FIELD") (pin "10") (pinfunction "C_10") (pintype "input"))
    )
    (net (code "8") (name "BAC07") (class "Default")
      (node (ref "D36L") (pin "16") (pinfunction "16_16") (pintype "passive"))
      (node (ref "DAR4-7") (pin "15") (pinfunction "A_15") (pintype "input"))
      (node (ref "DMA4-7") (pin "15") (pinfunction "A_15") (pintype "input"))
      (node (ref "FIELD") (pin "1") (pinfunction "B_1") (pintype "input"))
    )
    (net (code "9") (name "BAC08") (class "Default")
      (node (ref "D36L") (pin "18") (pinfunction "18_18") (pintype "passive"))
      (node (ref "DAR8-11") (pin "9") (pinfunction "D_9") (pintype "input"))
      (node (ref "DMA8-11") (pin "9") (pinfunction "D_9") (pintype "input"))
      (node (ref "FIELD") (pin "15") (pinfunction "A_15") (pintype "input"))
    )
    (net (code "10") (name "BAC09") (class "Default")
      (node (ref "D36L") (pin "22") (pinfunction "22_22") (pintype "passive"))
      (node (ref "DAR8-11") (pin "10") (pinfunction "C_10") (pintype "input"))
      (node (ref "DMA8-11") (pin "10") (pinfunction "C_10") (pintype "input"))
    )
    (net (code "11") (name "BAC10") (class "Default")
      (node (ref "D36L") (pin "24") (pinfunction "24_24") (pintype "passive"))
      (node (ref "DAR8-11") (pin "1") (pinfunction "B_1") (pintype "input"))
      (node (ref "DMA8-11") (pin "1") (pinfunction "B_1") (pintype "input"))
    )
    (net (code "12") (name "BAC11") (class "Default")
      (node (ref "D36L") (pin "26") (pinfunction "26_26") (pintype "passive"))
      (node (ref "DAR8-11") (pin "15") (pinfunction "A_15") (pintype "input"))
      (node (ref "DMA8-11") (pin "15") (pinfunction "A_15") (pintype "input"))
    )
    (net (code "13") (name "BINIT") (class "Default")
      (node (ref "D36L") (pin "38") (pinfunction "38_38") (pintype "passive"))
      (node (ref "IC10") (pin "11") (pinfunction "CLK_11") (pintype "input"))
      (node (ref "IC10") (pin "3") (pinfunction "CLK_3") (pintype "input"))
      (node (ref "IC23") (pin "3") (pinfunction "CLK_3") (pintype "input"))
      (node (ref "IC9") (pin "11") (pinfunction "CLK_11") (pintype "input"))
      (node (ref "IC9") (pin "3") (pinfunction "CLK_3") (pintype "input"))
    )
    (net (code "14") (name "BINIT2") (class "Default")
      (node (ref "C36L") (pin "38") (pinfunction "38_38") (pintype "passive"))
    )
    (net (code "15") (name "BIOP1") (class "Default")
      (node (ref "D36L") (pin "28") (pinfunction "28_28") (pintype "passive"))
      (node (ref "IC32") (pin "6") (pinfunction "G1_6") (pintype "input"))
    )
    (net (code "16") (name "BIOP2") (class "Default")
      (node (ref "D36L") (pin "30") (pinfunction "30_30") (pintype "passive"))
      (node (ref "IC29") (pin "6") (pinfunction "G1_6") (pintype "input"))
    )
    (net (code "17") (name "BIOP4") (class "Default")
      (node (ref "D36L") (pin "32") (pinfunction "32_32") (pintype "passive"))
      (node (ref "IC25") (pin "6") (pinfunction "G1_6") (pintype "input"))
    )
    (net (code "18") (name "BMB00") (class "Default")
      (node (ref "D35L") (pin "2") (pinfunction "2_2") (pintype "passive"))
      (node (ref "IC35") (pin "8") (pinfunction "A4_8") (pintype "input"))
    )
    (net (code "19") (name "BMB01") (class "Default")
      (node (ref "D35L") (pin "4") (pinfunction "4_4") (pintype "passive"))
      (node (ref "IC35") (pin "6") (pinfunction "A3_6") (pintype "input"))
    )
    (net (code "20") (name "BMB02") (class "Default")
      (node (ref "D35L") (pin "6") (pinfunction "6_6") (pintype "passive"))
      (node (ref "IC35") (pin "4") (pinfunction "A2_4") (pintype "input"))
    )
    (net (code "21") (name "BMB03") (class "Default")
      (node (ref "D35L") (pin "10") (pinfunction "10_10") (pintype "passive"))
      (node (ref "IC35") (pin "2") (pinfunction "A1_2") (pintype "input"))
      (node (ref "IC36") (pin "3") (pinfunction "C_3") (pintype "input"))
    )
    (net (code "22") (name "BMB04") (class "Default")
      (node (ref "D35L") (pin "14") (pinfunction "14_14") (pintype "passive"))
      (node (ref "IC28") (pin "17") (pinfunction "A4_17") (pintype "input"))
      (node (ref "IC36") (pin "2") (pinfunction "B_2") (pintype "input"))
    )
    (net (code "23") (name "BMB05") (class "Default")
      (node (ref "D35L") (pin "18") (pinfunction "18_18") (pintype "passive"))
      (node (ref "IC28") (pin "15") (pinfunction "A3_15") (pintype "input"))
      (node (ref "IC36") (pin "1") (pinfunction "A_1") (pintype "input"))
    )
    (net (code "24") (name "BMB06") (class "Default")
      (node (ref "D35L") (pin "24") (pinfunction "24_24") (pintype "passive"))
      (node (ref "IC25") (pin "3") (pinfunction "C_3") (pintype "input"))
      (node (ref "IC28") (pin "13") (pinfunction "A2_13") (pintype "input"))
      (node (ref "IC29") (pin "3") (pinfunction "C_3") (pintype "input"))
      (node (ref "IC32") (pin "3") (pinfunction "C_3") (pintype "input"))
    )
    (net (code "25") (name "BMB07") (class "Default")
      (node (ref "D35L") (pin "28") (pinfunction "28_28") (pintype "passive"))
      (node (ref "IC25") (pin "2") (pinfunction "B_2") (pintype "input"))
      (node (ref "IC28") (pin "11") (pinfunction "A1_11") (pintype "input"))
      (node (ref "IC29") (pin "2") (pinfunction "B_2") (pintype "input"))
      (node (ref "IC32") (pin "2") (pinfunction "B_2") (pintype "input"))
    )
    (net (code "26") (name "BMB08") (class "Default")
      (node (ref "D35L") (pin "32") (pinfunction "32_32") (pintype "passive"))
      (node (ref "IC25") (pin "1") (pinfunction "A_1") (pintype "input"))
      (node (ref "IC28") (pin "8") (pinfunction "A4_8") (pintype "input"))
      (node (ref "IC29") (pin "1") (pinfunction "A_1") (pintype "input"))
      (node (ref "IC32") (pin "1") (pinfunction "A_1") (pintype "input"))
    )
    (net (code "27") (name "BMB09") (class "Default")
      (node (ref "D35L") (pin "34") (pinfunction "34_34") (pintype "passive"))
      (node (ref "IC16") (pin "14") (pinfunction "A_14") (pintype "input"))
      (node (ref "IC17") (pin "3") (pinfunction "B_3") (pintype "input"))
      (node (ref "IC28") (pin "6") (pinfunction "A3_6") (pintype "input"))
    )
    (net (code "28") (name "BMB10") (class "Default")
      (node (ref "D35L") (pin "36") (pinfunction "36_36") (pintype "passive"))
      (node (ref "IC16") (pin "2") (pinfunction "A_2") (pintype "input"))
      (node (ref "IC17") (pin "14") (pinfunction "A_14") (pintype "input"))
      (node (ref "IC28") (pin "4") (pinfunction "A2_4") (pintype "input"))
    )
    (net (code "29") (name "BMB11") (class "Default")
      (node (ref "D35L") (pin "38") (pinfunction "38_38") (pintype "passive"))
      (node (ref "IC28") (pin "2") (pinfunction "A1_2") (pintype "input"))
    )
    (net (code "30") (name "BTS1") (class "Default")
      (node (ref "D36L") (pin "36") (pinfunction "36_36") (pintype "passive"))
      (node (ref "IC11") (pin "3") (pinfunction "CLK_3") (pintype "input"))
    )
    (net (code "31") (name "BTS3") (class "Default")
      (node (ref "D36L") (pin "34") (pinfunction "34_34") (pintype "passive"))
    )
    (net (code "32") (name "BUSY") (class "Default")
      (node (ref "IC10") (pin "9") (pinfunction "Q_9") (pintype "output"))
      (node (ref "IC11") (pin "2") (pinfunction "D_2") (pintype "input"))
      (node (ref "IC7") (pin "14") (pinfunction "A_14") (pintype "input"))
    )
    (net (code "33") (name "BWCO") (class "Default")
      (node (ref "IC44") (pin "8") (pinfunction "O_8") (pintype "output"))
      (node (ref "IC46") (pin "9") (pinfunction "I_9") (pintype "input"))
    )
    (net (code "34") (name "CA_INCR") (class "Default")
      (node (ref "C35L") (pin "30") (pinfunction "30_30") (pintype "passive"))
    )
    (net (code "35") (name "CIE") (class "Default")
      (node (ref "IC30") (pin "15") (pinfunction "A3_15") (pintype "input"))
      (node (ref "IC33") (pin "9") (pinfunction "I_9") (pintype "input"))
      (node (ref "IC40") (pin "1") (pinfunction "I0_1") (pintype "input"))
      (node (ref "INTENB") (pin "3") (pinfunction "QA_3") (pintype "output"))
    )
    (net (code "36") (name "DAR04") (class "Default")
      (node (ref "DAR4-7") (pin "7") (pinfunction "QD_7") (pintype "output"))
      (node (ref "IC21") (pin "3") (pinfunction "B_3") (pintype "input"))
      (node (ref "IC31") (pin "17") (pinfunction "A4_17") (pintype "input"))
      (node (ref "IC39") (pin "3") (pinfunction "I_3") (pintype "input"))
      (node (ref "IC41") (pin "2") (pinfunction "A_2") (pintype "input"))
      (node (ref "IC41") (pin "3") (pinfunction "B_3") (pintype "input"))
    )
    (net (code "37") (name "DAR05") (class "Default")
      (node (ref "DAR4-7") (pin "6") (pinfunction "QC_6") (pintype "output"))
      (node (ref "IC21") (pin "2") (pinfunction "A_2") (pintype "input"))
      (node (ref "IC31") (pin "15") (pinfunction "A3_15") (pintype "input"))
      (node (ref "IC39") (pin "5") (pinfunction "I_5") (pintype "input"))
      (node (ref "RS08") (pin "1") (pinfunction "1_1") (pintype "passive"))
    )
    (net (code "38") (name "DAR06") (class "Default")
      (node (ref "DAR4-7") (pin "2") (pinfunction "QB_2") (pintype "output"))
      (node (ref "IC21") (pin "1") (pinfunction "G_1") (pintype "input"))
      (node (ref "IC31") (pin "13") (pinfunction "A2_13") (pintype "input"))
      (node (ref "IC43") (pin "1") (pinfunction "I_1") (pintype "input"))
      (node (ref "RS08") (pin "6") (pinfunction "6_6") (pintype "passive"))
    )
    (net (code "39") (name "DAR07") (class "Default")
      (node (ref "DAR4-7") (pin "3") (pinfunction "QA_3") (pintype "output"))
      (node (ref "IC1") (pin "9") (pinfunction "C_9") (pintype "input"))
      (node (ref "IC2") (pin "9") (pinfunction "C_9") (pintype "input"))
      (node (ref "IC3") (pin "9") (pinfunction "C_9") (pintype "input"))
      (node (ref "IC31") (pin "11") (pinfunction "A1_11") (pintype "input"))
      (node (ref "IC4") (pin "9") (pinfunction "C_9") (pintype "input"))
      (node (ref "IC43") (pin "3") (pinfunction "I_3") (pintype "input"))
      (node (ref "RS08") (pin "3") (pinfunction "3_3") (pintype "passive"))
    )
    (net (code "40") (name "DAR08") (class "Default")
      (node (ref "DAR8-11") (pin "7") (pinfunction "QD_7") (pintype "output"))
      (node (ref "IC1") (pin "10") (pinfunction "B_10") (pintype "input"))
      (node (ref "IC2") (pin "10") (pinfunction "B_10") (pintype "input"))
      (node (ref "IC24") (pin "17") (pinfunction "A4_17") (pintype "input"))
      (node (ref "IC3") (pin "10") (pinfunction "B_10") (pintype "input"))
      (node (ref "IC4") (pin "10") (pinfunction "B_10") (pintype "input"))
      (node (ref "IC43") (pin "5") (pinfunction "I_5") (pintype "input"))
      (node (ref "RS08") (pin "4") (pinfunction "4_4") (pintype "passive"))
    )
    (net (code "41") (name "DAR09") (class "Default")
      (node (ref "DAR8-11") (pin "6") (pinfunction "QC_6") (pintype "output"))
      (node (ref "IC1") (pin "11") (pinfunction "A_11") (pintype "input"))
      (node (ref "IC2") (pin "11") (pinfunction "A_11") (pintype "input"))
      (node (ref "IC24") (pin "15") (pinfunction "A3_15") (pintype "input"))
      (node (ref "IC3") (pin "11") (pinfunction "A_11") (pintype "input"))
      (node (ref "IC4") (pin "11") (pinfunction "A_11") (pintype "input"))
      (node (ref "IC45") (pin "1") (pinfunction "I_1") (pintype "input"))
      (node (ref "RS08") (pin "5") (pinfunction "5_5") (pintype "passive"))
    )
    (net (code "42") (name "DAR10") (class "Default")
      (node (ref "DAR8-11") (pin "2") (pinfunction "QB_2") (pintype "output"))
      (node (ref "IC24") (pin "13") (pinfunction "A2_13") (pintype "input"))
      (node (ref "IC45") (pin "3") (pinfunction "I_3") (pintype "input"))
      (node (ref "RS08") (pin "10") (pinfunction "10_10") (pintype "passive"))
    )
    (net (code "43") (name "DAR11") (class "Default")
      (node (ref "DAR8-11") (pin "3") (pinfunction "QA_3") (pintype "output"))
      (node (ref "IC24") (pin "11") (pinfunction "A1_11") (pintype "input"))
      (node (ref "IC45") (pin "5") (pinfunction "I_5") (pintype "input"))
      (node (ref "RS08") (pin "7") (pinfunction "7_7") (pintype "passive"))
    )
    (net (code "44") (name "DATA_IN") (class "Default")
      (node (ref "C36L") (pin "30") (pinfunction "30_30") (pintype "passive"))
      (node (ref "IC22") (pin "6") (pinfunction "O_6") (pintype "open_collector"))
    )
    (net (code "45") (name "DIO00") (class "Default")
      (node (ref "IC13") (pin "12") (pinfunction "E_12") (pintype "input"))
      (node (ref "IC14") (pin "12") (pinfunction "E_12") (pintype "input"))
      (node (ref "IC33") (pin "1") (pinfunction "I_1") (pintype "input"))
      (node (ref "IC34") (pin "8") (pinfunction "A4_8") (pintype "input"))
      (node (ref "IC35") (pin "12") (pinfunction "Y4_12") (pintype "tri_state"))
      (node (ref "RS08") (pin "36") (pinfunction "36_36") (pintype "passive"))
    )
    (net (code "46") (name "DIO01") (class "Default")
      (node (ref "IC13") (pin "11") (pinfunction "D_11") (pintype "input"))
      (node (ref "IC14") (pin "11") (pinfunction "D_11") (pintype "input"))
      (node (ref "IC33") (pin "3") (pinfunction "I_3") (pintype "input"))
      (node (ref "IC34") (pin "6") (pinfunction "A3_6") (pintype "input"))
      (node (ref "IC35") (pin "14") (pinfunction "Y3_14") (pintype "tri_state"))
      (node (ref "RS08") (pin "37") (pinfunction "37_37") (pintype "passive"))
    )
    (net (code "47") (name "DIO02") (class "Default")
      (node (ref "IC13") (pin "10") (pinfunction "C_10") (pintype "input"))
      (node (ref "IC14") (pin "10") (pinfunction "C_10") (pintype "input"))
      (node (ref "IC33") (pin "5") (pinfunction "I_5") (pintype "input"))
      (node (ref "IC34") (pin "4") (pinfunction "A2_4") (pintype "input"))
      (node (ref "IC35") (pin "16") (pinfunction "Y2_16") (pintype "tri_state"))
      (node (ref "RS08") (pin "35") (pinfunction "35_35") (pintype "passive"))
    )
    (net (code "48") (name "DIO03") (class "Default")
      (node (ref "IC13") (pin "9") (pinfunction "B_9") (pintype "input"))
      (node (ref "IC14") (pin "9") (pinfunction "B_9") (pintype "input"))
      (node (ref "IC34") (pin "2") (pinfunction "A1_2") (pintype "input"))
      (node (ref "IC35") (pin "18") (pinfunction "Y1_18") (pintype "tri_state"))
      (node (ref "IC42") (pin "1") (pinfunction "I_1") (pintype "input"))
      (node (ref "RS08") (pin "33") (pinfunction "33_33") (pintype "passive"))
    )
    (net (code "49") (name "DIO04") (class "Default")
      (node (ref "IC15") (pin "2") (pinfunction "H_2") (pintype "input"))
      (node (ref "IC26") (pin "17") (pinfunction "A4_17") (pintype "input"))
      (node (ref "IC28") (pin "3") (pinfunction "Y4_3") (pintype "tri_state"))
      (node (ref "IC42") (pin "3") (pinfunction "I_3") (pintype "input"))
      (node (ref "RS08") (pin "24") (pinfunction "24_24") (pintype "passive"))
    )
    (net (code "50") (name "DIO05") (class "Default")
      (node (ref "IC15") (pin "1") (pinfunction "G_1") (pintype "input"))
      (node (ref "IC26") (pin "15") (pinfunction "A3_15") (pintype "input"))
      (node (ref "IC28") (pin "5") (pinfunction "Y3_5") (pintype "tri_state"))
      (node (ref "IC42") (pin "5") (pinfunction "I_5") (pintype "input"))
      (node (ref "RS08") (pin "26") (pinfunction "26_26") (pintype "passive"))
    )
    (net (code "51") (name "DIO06") (class "Default")
      (node (ref "IC15") (pin "13") (pinfunction "F_13") (pintype "input"))
      (node (ref "IC26") (pin "13") (pinfunction "A2_13") (pintype "input"))
      (node (ref "IC28") (pin "7") (pinfunction "Y2_7") (pintype "tri_state"))
      (node (ref "IC44") (pin "1") (pinfunction "I_1") (pintype "input"))
      (node (ref "RS08") (pin "28") (pinfunction "28_28") (pintype "passive"))
    )
    (net (code "52") (name "DIO07") (class "Default")
      (node (ref "IC15") (pin "12") (pinfunction "E_12") (pintype "input"))
      (node (ref "IC26") (pin "11") (pinfunction "A1_11") (pintype "input"))
      (node (ref "IC28") (pin "9") (pinfunction "Y1_9") (pintype "tri_state"))
      (node (ref "IC44") (pin "3") (pinfunction "I_3") (pintype "input"))
      (node (ref "RS08") (pin "30") (pinfunction "30_30") (pintype "passive"))
    )
    (net (code "53") (name "DIO08") (class "Default")
      (node (ref "IC15") (pin "11") (pinfunction "D_11") (pintype "input"))
      (node (ref "IC26") (pin "8") (pinfunction "A4_8") (pintype "input"))
      (node (ref "IC28") (pin "12") (pinfunction "Y4_12") (pintype "tri_state"))
      (node (ref "IC44") (pin "5") (pinfunction "I_5") (pintype "input"))
      (node (ref "RS08") (pin "32") (pinfunction "32_32") (pintype "passive"))
    )
    (net (code "54") (name "DIO09") (class "Default")
      (node (ref "IC15") (pin "10") (pinfunction "C_10") (pintype "input"))
      (node (ref "IC26") (pin "6") (pinfunction "A3_6") (pintype "input"))
      (node (ref "IC28") (pin "14") (pinfunction "Y3_14") (pintype "tri_state"))
      (node (ref "IC46") (pin "1") (pinfunction "I_1") (pintype "input"))
      (node (ref "RS08") (pin "29") (pinfunction "29_29") (pintype "passive"))
    )
    (net (code "55") (name "DIO10") (class "Default")
      (node (ref "IC15") (pin "9") (pinfunction "B_9") (pintype "input"))
      (node (ref "IC26") (pin "4") (pinfunction "A2_4") (pintype "input"))
      (node (ref "IC28") (pin "16") (pinfunction "Y2_16") (pintype "tri_state"))
      (node (ref "IC46") (pin "3") (pinfunction "I_3") (pintype "input"))
      (node (ref "RS08") (pin "27") (pinfunction "27_27") (pintype "passive"))
    )
    (net (code "56") (name "DIO11") (class "Default")
      (node (ref "IC15") (pin "8") (pinfunction "A_8") (pintype "input"))
      (node (ref "IC26") (pin "2") (pinfunction "A1_2") (pintype "input"))
      (node (ref "IC28") (pin "18") (pinfunction "Y1_18") (pintype "tri_state"))
      (node (ref "IC46") (pin "5") (pinfunction "I_5") (pintype "input"))
      (node (ref "RS08") (pin "25") (pinfunction "25_25") (pintype "passive"))
    )
    (net (code "57") (name "DIOEVEN") (class "Default")
      (node (ref "IC13") (pin "13") (pinfunction "F_13") (pintype "input"))
      (node (ref "IC35") (pin "9") (pinfunction "Y1_9") (pintype "tri_state"))
      (node (ref "RS08") (pin "34") (pinfunction "34_34") (pintype "passive"))
    )
    (net (code "58") (name "DMA00") (class "Default")
      (node (ref "DMA0-3") (pin "7") (pinfunction "QD_7") (pintype "output"))
      (node (ref "IC27") (pin "9") (pinfunction "I_9") (pintype "input"))
      (node (ref "IC38") (pin "8") (pinfunction "A4_8") (pintype "input"))
      (node (ref "RS08") (pin "16") (pinfunction "16_16") (pintype "passive"))
    )
    (net (code "59") (name "DMA01") (class "Default")
      (node (ref "DMA0-3") (pin "6") (pinfunction "QC_6") (pintype "output"))
      (node (ref "IC27") (pin "11") (pinfunction "I_11") (pintype "input"))
      (node (ref "IC38") (pin "6") (pinfunction "A3_6") (pintype "input"))
      (node (ref "RS08") (pin "20") (pinfunction "20_20") (pintype "passive"))
    )
    (net (code "60") (name "DMA02") (class "Default")
      (node (ref "DMA0-3") (pin "2") (pinfunction "QB_2") (pintype "output"))
      (node (ref "IC27") (pin "13") (pinfunction "I_13") (pintype "input"))
      (node (ref "IC38") (pin "4") (pinfunction "A2_4") (pintype "input"))
      (node (ref "RS08") (pin "14") (pinfunction "14_14") (pintype "passive"))
    )
    (net (code "61") (name "DMA03") (class "Default")
      (node (ref "DMA0-3") (pin "3") (pinfunction "QA_3") (pintype "output"))
      (node (ref "IC38") (pin "2") (pinfunction "A1_2") (pintype "input"))
      (node (ref "IC39") (pin "9") (pinfunction "I_9") (pintype "input"))
      (node (ref "RS08") (pin "12") (pinfunction "12_12") (pintype "passive"))
    )
    (net (code "62") (name "DMA04") (class "Default")
      (node (ref "DMA4-7") (pin "7") (pinfunction "QD_7") (pintype "output"))
      (node (ref "IC31") (pin "8") (pinfunction "A4_8") (pintype "input"))
      (node (ref "IC39") (pin "11") (pinfunction "I_11") (pintype "input"))
      (node (ref "RS08") (pin "9") (pinfunction "9_9") (pintype "passive"))
    )
    (net (code "63") (name "DMA05") (class "Default")
      (node (ref "DMA4-7") (pin "6") (pinfunction "QC_6") (pintype "output"))
      (node (ref "IC31") (pin "6") (pinfunction "A3_6") (pintype "input"))
      (node (ref "IC39") (pin "13") (pinfunction "I_13") (pintype "input"))
      (node (ref "RS08") (pin "11") (pinfunction "11_11") (pintype "passive"))
    )
    (net (code "64") (name "DMA06") (class "Default")
      (node (ref "DMA4-7") (pin "2") (pinfunction "QB_2") (pintype "output"))
      (node (ref "IC31") (pin "4") (pinfunction "A2_4") (pintype "input"))
      (node (ref "IC43") (pin "9") (pinfunction "I_9") (pintype "input"))
      (node (ref "RS08") (pin "13") (pinfunction "13_13") (pintype "passive"))
    )
    (net (code "65") (name "DMA07") (class "Default")
      (node (ref "DMA4-7") (pin "3") (pinfunction "QA_3") (pintype "output"))
      (node (ref "IC31") (pin "2") (pinfunction "A1_2") (pintype "input"))
      (node (ref "IC43") (pin "11") (pinfunction "I_11") (pintype "input"))
      (node (ref "RS08") (pin "15") (pinfunction "15_15") (pintype "passive"))
    )
    (net (code "66") (name "DMA08") (class "Default")
      (node (ref "DMA8-11") (pin "7") (pinfunction "QD_7") (pintype "output"))
      (node (ref "IC24") (pin "8") (pinfunction "A4_8") (pintype "input"))
      (node (ref "IC43") (pin "13") (pinfunction "I_13") (pintype "input"))
      (node (ref "RS08") (pin "17") (pinfunction "17_17") (pintype "passive"))
    )
    (net (code "67") (name "DMA09") (class "Default")
      (node (ref "DMA8-11") (pin "6") (pinfunction "QC_6") (pintype "output"))
      (node (ref "IC24") (pin "6") (pinfunction "A3_6") (pintype "input"))
      (node (ref "IC45") (pin "9") (pinfunction "I_9") (pintype "input"))
      (node (ref "RS08") (pin "19") (pinfunction "19_19") (pintype "passive"))
    )
    (net (code "68") (name "DMA10") (class "Default")
      (node (ref "DMA8-11") (pin "2") (pinfunction "QB_2") (pintype "output"))
      (node (ref "IC24") (pin "4") (pinfunction "A2_4") (pintype "input"))
      (node (ref "IC45") (pin "11") (pinfunction "I_11") (pintype "input"))
      (node (ref "RS08") (pin "21") (pinfunction "21_21") (pintype "passive"))
    )
    (net (code "69") (name "DMA11") (class "Default")
      (node (ref "DMA8-11") (pin "3") (pinfunction "QA_3") (pintype "output"))
      (node (ref "IC24") (pin "2") (pinfunction "A1_2") (pintype "input"))
      (node (ref "IC45") (pin "13") (pinfunction "I_13") (pintype "input"))
      (node (ref "RS08") (pin "23") (pinfunction "23_23") (pintype "passive"))
    )
    (net (code "70") (name "DONE") (class "Default")
      (node (ref "IC11") (pin "9") (pinfunction "Q_9") (pintype "output"))
      (node (ref "IC40") (pin "2") (pinfunction "I1_2") (pintype "input"))
      (node (ref "IC46") (pin "13") (pinfunction "I_13") (pintype "input"))
    )
    (net (code "71") (name "EIE") (class "Default")
      (node (ref "IC33") (pin "11") (pinfunction "I_11") (pintype "input"))
      (node (ref "IC37") (pin "2") (pinfunction "A1_2") (pintype "input"))
      (node (ref "IC40") (pin "9") (pinfunction "I0_9") (pintype "input"))
      (node (ref "INTENB") (pin "6") (pinfunction "QC_6") (pintype "output"))
    )
    (net (code "72") (name "ERROR") (class "Default")
      (node (ref "IC12") (pin "6") (pinfunction "O_6") (pintype "output"))
      (node (ref "IC40") (pin "10") (pinfunction "I1_10") (pintype "input"))
      (node (ref "IC7") (pin "2") (pinfunction "A_2") (pintype "input"))
    )
    (net (code "73") (name "F.1") (class "Default")
      (node (ref "FIELD") (pin "3") (pinfunction "QA_3") (pintype "output"))
      (node (ref "IC20") (pin "11") (pinfunction "A1_11") (pintype "input"))
      (node (ref "IC27") (pin "5") (pinfunction "I_5") (pintype "input"))
      (node (ref "IC30") (pin "8") (pinfunction "A4_8") (pintype "input"))
    )
    (net (code "74") (name "F.2") (class "Default")
      (node (ref "FIELD") (pin "2") (pinfunction "QB_2") (pintype "output"))
      (node (ref "IC20") (pin "13") (pinfunction "A2_13") (pintype "input"))
      (node (ref "IC27") (pin "3") (pinfunction "I_3") (pintype "input"))
      (node (ref "IC30") (pin "11") (pinfunction "A1_11") (pintype "input"))
    )
    (net (code "75") (name "F.3") (class "Default")
      (node (ref "FIELD") (pin "6") (pinfunction "QC_6") (pintype "output"))
      (node (ref "IC20") (pin "15") (pinfunction "A3_15") (pintype "input"))
      (node (ref "IC27") (pin "1") (pinfunction "I_1") (pintype "input"))
      (node (ref "IC30") (pin "13") (pinfunction "A2_13") (pintype "input"))
    )
    (net (code "76") (name "GND") (class "Default")
      (node (ref "C1") (pin "2") (pinfunction "2_2") (pintype "passive"))
      (node (ref "C35L") (pin "1") (pinfunction "1_1") (pintype "passive"))
      (node (ref "C35L") (pin "11") (pinfunction "11_11") (pintype "passive"))
      (node (ref "C35L") (pin "13") (pinfunction "13_13") (pintype "passive"))
      (node (ref "C35L") (pin "15") (pinfunction "15_15") (pintype "passive"))
      (node (ref "C35L") (pin "17") (pinfunction "17_17") (pintype "passive"))
      (node (ref "C35L") (pin "19") (pinfunction "19_19") (pintype "passive"))
      (node (ref "C35L") (pin "21") (pinfunction "21_21") (pintype "passive"))
      (node (ref "C35L") (pin "23") (pinfunction "23_23") (pintype "passive"))
      (node (ref "C35L") (pin "25") (pinfunction "25_25") (pintype "passive"))
      (node (ref "C35L") (pin "27") (pinfunction "27_27") (pintype "passive"))
      (node (ref "C35L") (pin "29") (pinfunction "29_29") (pintype "passive"))
      (node (ref "C35L") (pin "3") (pinfunction "3_3") (pintype "passive"))
      (node (ref "C35L") (pin "31") (pinfunction "31_31") (pintype "passive"))
      (node (ref "C35L") (pin "33") (pinfunction "33_33") (pintype "passive"))
      (node (ref "C35L") (pin "35") (pinfunction "35_35") (pintype "passive"))
      (node (ref "C35L") (pin "37") (pinfunction "37_37") (pintype "passive"))
      (node (ref "C35L") (pin "39") (pinfunction "39_39") (pintype "passive"))
      (node (ref "C35L") (pin "5") (pinfunction "5_5") (pintype "passive"))
      (node (ref "C35L") (pin "7") (pinfunction "7_7") (pintype "passive"))
      (node (ref "C35L") (pin "9") (pinfunction "9_9") (pintype "passive"))
      (node (ref "C36L") (pin "1") (pinfunction "1_1") (pintype "passive"))
      (node (ref "C36L") (pin "11") (pinfunction "11_11") (pintype "passive"))
      (node (ref "C36L") (pin "13") (pinfunction "13_13") (pintype "passive"))
      (node (ref "C36L") (pin "15") (pinfunction "15_15") (pintype "passive"))
      (node (ref "C36L") (pin "17") (pinfunction "17_17") (pintype "passive"))
      (node (ref "C36L") (pin "19") (pinfunction "19_19") (pintype "passive"))
      (node (ref "C36L") (pin "21") (pinfunction "21_21") (pintype "passive"))
      (node (ref "C36L") (pin "23") (pinfunction "23_23") (pintype "passive"))
      (node (ref "C36L") (pin "25") (pinfunction "25_25") (pintype "passive"))
      (node (ref "C36L") (pin "27") (pinfunction "27_27") (pintype "passive"))
      (node (ref "C36L") (pin "29") (pinfunction "29_29") (pintype "passive"))
      (node (ref "C36L") (pin "3") (pinfunction "3_3") (pintype "passive"))
      (node (ref "C36L") (pin "31") (pinfunction "31_31") (pintype "passive"))
      (node (ref "C36L") (pin "33") (pinfunction "33_33") (pintype "passive"))
      (node (ref "C36L") (pin "35") (pinfunction "35_35") (pintype "passive"))
      (node (ref "C36L") (pin "37") (pinfunction "37_37") (pintype "passive"))
      (node (ref "C36L") (pin "39") (pinfunction "39_39") (pintype "passive"))
      (node (ref "C36L") (pin "5") (pinfunction "5_5") (pintype "passive"))
      (node (ref "C36L") (pin "7") (pinfunction "7_7") (pintype "passive"))
      (node (ref "C36L") (pin "9") (pinfunction "9_9") (pintype "passive"))
      (node (ref "D34L") (pin "1") (pinfunction "1_1") (pintype "passive"))
      (node (ref "D34L") (pin "11") (pinfunction "11_11") (pintype "passive"))
      (node (ref "D34L") (pin "13") (pinfunction "13_13") (pintype "passive"))
      (node (ref "D34L") (pin "15") (pinfunction "15_15") (pintype "passive"))
      (node (ref "D34L") (pin "17") (pinfunction "17_17") (pintype "passive"))
      (node (ref "D34L") (pin "19") (pinfunction "19_19") (pintype "passive"))
      (node (ref "D34L") (pin "21") (pinfunction "21_21") (pintype "passive"))
      (node (ref "D34L") (pin "23") (pinfunction "23_23") (pintype "passive"))
      (node (ref "D34L") (pin "25") (pinfunction "25_25") (pintype "passive"))
      (node (ref "D34L") (pin "27") (pinfunction "27_27") (pintype "passive"))
      (node (ref "D34L") (pin "29") (pinfunction "29_29") (pintype "passive"))
      (node (ref "D34L") (pin "3") (pinfunction "3_3") (pintype "passive"))
      (node (ref "D34L") (pin "31") (pinfunction "31_31") (pintype "passive"))
      (node (ref "D34L") (pin "33") (pinfunction "33_33") (pintype "passive"))
      (node (ref "D34L") (pin "35") (pinfunction "35_35") (pintype "passive"))
      (node (ref "D34L") (pin "37") (pinfunction "37_37") (pintype "passive"))
      (node (ref "D34L") (pin "39") (pinfunction "39_39") (pintype "passive"))
      (node (ref "D34L") (pin "5") (pinfunction "5_5") (pintype "passive"))
      (node (ref "D34L") (pin "7") (pinfunction "7_7") (pintype "passive"))
      (node (ref "D34L") (pin "9") (pinfunction "9_9") (pintype "passive"))
      (node (ref "D35L") (pin "1") (pinfunction "1_1") (pintype "passive"))
      (node (ref "D35L") (pin "11") (pinfunction "11_11") (pintype "passive"))
      (node (ref "D35L") (pin "13") (pinfunction "13_13") (pintype "passive"))
      (node (ref "D35L") (pin "15") (pinfunction "15_15") (pintype "passive"))
      (node (ref "D35L") (pin "17") (pinfunction "17_17") (pintype "passive"))
      (node (ref "D35L") (pin "19") (pinfunction "19_19") (pintype "passive"))
      (node (ref "D35L") (pin "21") (pinfunction "21_21") (pintype "passive"))
      (node (ref "D35L") (pin "23") (pinfunction "23_23") (pintype "passive"))
      (node (ref "D35L") (pin "25") (pinfunction "25_25") (pintype "passive"))
      (node (ref "D35L") (pin "27") (pinfunction "27_27") (pintype "passive"))
      (node (ref "D35L") (pin "29") (pinfunction "29_29") (pintype "passive"))
      (node (ref "D35L") (pin "3") (pinfunction "3_3") (pintype "passive"))
      (node (ref "D35L") (pin "31") (pinfunction "31_31") (pintype "passive"))
      (node (ref "D35L") (pin "33") (pinfunction "33_33") (pintype "passive"))
      (node (ref "D35L") (pin "35") (pinfunction "35_35") (pintype "passive"))
      (node (ref "D35L") (pin "37") (pinfunction "37_37") (pintype "passive"))
      (node (ref "D35L") (pin "39") (pinfunction "39_39") (pintype "passive"))
      (node (ref "D35L") (pin "5") (pinfunction "5_5") (pintype "passive"))
      (node (ref "D35L") (pin "7") (pinfunction "7_7") (pintype "passive"))
      (node (ref "D35L") (pin "9") (pinfunction "9_9") (pintype "passive"))
      (node (ref "D36L") (pin "1") (pinfunction "1_1") (pintype "passive"))
      (node (ref "D36L") (pin "11") (pinfunction "11_11") (pintype "passive"))
      (node (ref "D36L") (pin "13") (pinfunction "13_13") (pintype "passive"))
      (node (ref "D36L") (pin "15") (pinfunction "15_15") (pintype "passive"))
      (node (ref "D36L") (pin "17") (pinfunction "17_17") (pintype "passive"))
      (node (ref "D36L") (pin "19") (pinfunction "19_19") (pintype "passive"))
      (node (ref "D36L") (pin "21") (pinfunction "21_21") (pintype "passive"))
      (node (ref "D36L") (pin "23") (pinfunction "23_23") (pintype "passive"))
      (node (ref "D36L") (pin "25") (pinfunction "25_25") (pintype "passive"))
      (node (ref "D36L") (pin "27") (pinfunction "27_27") (pintype "passive"))
      (node (ref "D36L") (pin "29") (pinfunction "29_29") (pintype "passive"))
      (node (ref "D36L") (pin "3") (pinfunction "3_3") (pintype "passive"))
      (node (ref "D36L") (pin "31") (pinfunction "31_31") (pintype "passive"))
      (node (ref "D36L") (pin "33") (pinfunction "33_33") (pintype "passive"))
      (node (ref "D36L") (pin "35") (pinfunction "35_35") (pintype "passive"))
      (node (ref "D36L") (pin "37") (pinfunction "37_37") (pintype "passive"))
      (node (ref "D36L") (pin "39") (pinfunction "39_39") (pintype "passive"))
      (node (ref "D36L") (pin "5") (pinfunction "5_5") (pintype "passive"))
      (node (ref "D36L") (pin "7") (pinfunction "7_7") (pintype "passive"))
      (node (ref "D36L") (pin "9") (pinfunction "9_9") (pintype "passive"))
      (node (ref "DAR4-7") (pin "4") (pinfunction "DN_4") (pintype "input"))
      (node (ref "DAR8-11") (pin "4") (pinfunction "DN_4") (pintype "input"))
      (node (ref "DMA0-3") (pin "4") (pinfunction "DN_4") (pintype "input"))
      (node (ref "DMA4-7") (pin "4") (pinfunction "DN_4") (pintype "input"))
      (node (ref "DMA8-11") (pin "4") (pinfunction "DN_4") (pintype "input"))
      (node (ref "FIELD") (pin "4") (pinfunction "DN_4") (pintype "input"))
      (node (ref "FIELD") (pin "5") (pinfunction "UP_5") (pintype "input"))
      (node (ref "FIELD") (pin "9") (pinfunction "D_9") (pintype "input"))
      (node (ref "IC1") (pin "7") (pinfunction "G_7") (pintype "input"))
      (node (ref "IC10") (pin "12") (pinfunction "D_12") (pintype "input"))
      (node (ref "IC10") (pin "2") (pinfunction "D_2") (pintype "input"))
      (node (ref "IC13") (pin "1") (pinfunction "G_1") (pintype "input"))
      (node (ref "IC13") (pin "2") (pinfunction "H_2") (pintype "input"))
      (node (ref "IC14") (pin "1") (pinfunction "G_1") (pintype "input"))
      (node (ref "IC14") (pin "13") (pinfunction "F_13") (pintype "input"))
      (node (ref "IC14") (pin "2") (pinfunction "H_2") (pintype "input"))
      (node (ref "IC14") (pin "4") (pinfunction "OI_4") (pintype "input"))
      (node (ref "IC15") (pin "4") (pinfunction "OI_4") (pintype "input"))
      (node (ref "IC16") (pin "1") (pinfunction "G_1") (pintype "input"))
      (node (ref "IC16") (pin "15") (pinfunction "G_15") (pintype "input"))
      (node (ref "IC17") (pin "1") (pinfunction "G_1") (pintype "input"))
      (node (ref "IC17") (pin "15") (pinfunction "G_15") (pintype "input"))
      (node (ref "IC2") (pin "7") (pinfunction "G_7") (pintype "input"))
      (node (ref "IC20") (pin "17") (pinfunction "A4_17") (pintype "input"))
      (node (ref "IC23") (pin "2") (pinfunction "D_2") (pintype "input"))
      (node (ref "IC25") (pin "5") (pinfunction "G2B_5") (pintype "input"))
      (node (ref "IC29") (pin "5") (pinfunction "G2B_5") (pintype "input"))
      (node (ref "IC3") (pin "7") (pinfunction "G_7") (pintype "input"))
      (node (ref "IC30") (pin "6") (pinfunction "A3_6") (pintype "input"))
      (node (ref "IC32") (pin "5") (pinfunction "G2B_5") (pintype "input"))
      (node (ref "IC35") (pin "13") (pinfunction "A2_13") (pintype "input"))
      (node (ref "IC35") (pin "15") (pinfunction "A3_15") (pintype "input"))
      (node (ref "IC35") (pin "17") (pinfunction "A4_17") (pintype "input"))
      (node (ref "IC36") (pin "4") (pinfunction "G2A_4") (pintype "input"))
      (node (ref "IC36") (pin "5") (pinfunction "G2B_5") (pintype "input"))
      (node (ref "IC37") (pin "6") (pinfunction "A3_6") (pintype "input"))
      (node (ref "IC38") (pin "11") (pinfunction "A1_11") (pintype "input"))
      (node (ref "IC38") (pin "13") (pinfunction "A2_13") (pintype "input"))
      (node (ref "IC38") (pin "15") (pinfunction "A3_15") (pintype "input"))
      (node (ref "IC38") (pin "17") (pinfunction "A4_17") (pintype "input"))
      (node (ref "IC4") (pin "7") (pinfunction "G_7") (pintype "input"))
      (node (ref "IC7") (pin "1") (pinfunction "G_1") (pintype "input"))
      (node (ref "IC7") (pin "15") (pinfunction "G_15") (pintype "input"))
      (node (ref "IC8") (pin "1") (pinfunction "GND_1") (pintype "power_in"))
      (node (ref "IC9") (pin "12") (pinfunction "D_12") (pintype "input"))
      (node (ref "IC9") (pin "2") (pinfunction "D_2") (pintype "input"))
      (node (ref "INTENB") (pin "4") (pinfunction "DN_4") (pintype "input"))
      (node (ref "INTENB") (pin "5") (pinfunction "UP_5") (pintype "input"))
      (node (ref "INTENB") (pin "9") (pinfunction "D_9") (pintype "input"))
      (node (ref "J10") (pin "2") (pinfunction "2_2") (pintype "passive"))
      (node (ref "J11") (pin "2") (pinfunction "2_2") (pintype "passive"))
      (node (ref "J12") (pin "2") (pinfunction "2_2") (pintype "passive"))
      (node (ref "J13") (pin "2") (pinfunction "2_2") (pintype "passive"))
      (node (ref "J14") (pin "2") (pinfunction "2_2") (pintype "passive"))
      (node (ref "J2") (pin "2") (pinfunction "2_2") (pintype "passive"))
      (node (ref "J6") (pin "2") (pinfunction "2_2") (pintype "passive"))
      (node (ref "J8") (pin "2") (pinfunction "2_2") (pintype "passive"))
      (node (ref "J9") (pin "2") (pinfunction "2_2") (pintype "passive"))
      (node (ref "RS08") (pin "31") (pinfunction "31_31") (pintype "passive"))
      (node (ref "RS08") (pin "39") (pinfunction "39_39") (pintype "passive"))
    )
    (net (code "77") (name "NXD") (class "Default")
      (node (ref "IC23") (pin "5") (pinfunction "Q_5") (pintype "output"))
      (node (ref "IC30") (pin "4") (pinfunction "A2_4") (pintype "input"))
      (node (ref "IC44") (pin "13") (pinfunction "I_13") (pintype "input"))
    )
    (net (code "78") (name "Net-(DAR4-7A-CLR)") (class "Default")
      (node (ref "DAR4-7") (pin "14") (pinfunction "CLR_14") (pintype "input"))
      (node (ref "DAR8-11") (pin "14") (pinfunction "CLR_14") (pintype "input"))
      (node (ref "IC18") (pin "8") (pinfunction "O_8") (pintype "output"))
    )
    (net (code "79") (name "Net-(DAR4-7A-UP)") (class "Default")
      (node (ref "DAR4-7") (pin "5") (pinfunction "UP_5") (pintype "input"))
      (node (ref "DAR8-11") (pin "12") (pinfunction "CO_12") (pintype "output"))
    )
    (net (code "80") (name "Net-(DAR8-11A-UP)") (class "Default")
      (node (ref "DAR8-11") (pin "5") (pinfunction "UP_5") (pintype "input"))
      (node (ref "DMA0-3") (pin "12") (pinfunction "CO_12") (pintype "output"))
    )
    (net (code "81") (name "Net-(DMA0-3A-CLR)") (class "Default")
      (node (ref "DMA0-3") (pin "14") (pinfunction "CLR_14") (pintype "input"))
      (node (ref "DMA4-7") (pin "14") (pinfunction "CLR_14") (pintype "input"))
      (node (ref "DMA8-11") (pin "14") (pinfunction "CLR_14") (pintype "input"))
      (node (ref "IC18") (pin "6") (pinfunction "O_6") (pintype "output"))
    )
    (net (code "82") (name "Net-(DMA0-3A-UP)") (class "Default")
      (node (ref "DMA0-3") (pin "5") (pinfunction "UP_5") (pintype "input"))
      (node (ref "DMA4-7") (pin "12") (pinfunction "CO_12") (pintype "output"))
    )
    (net (code "83") (name "Net-(DMA4-7A-UP)") (class "Default")
      (node (ref "DMA4-7") (pin "5") (pinfunction "UP_5") (pintype "input"))
      (node (ref "DMA8-11") (pin "12") (pinfunction "CO_12") (pintype "output"))
    )
    (net (code "84") (name "Net-(IC1A-D0)") (class "Default")
      (node (ref "IC1") (pin "4") (pinfunction "D0_4") (pintype "input"))
      (node (ref "SW1") (pin "16") (pinfunction "16_16") (pintype "passive"))
    )
    (net (code "85") (name "Net-(IC1A-D1)") (class "Default")
      (node (ref "IC1") (pin "3") (pinfunction "D1_3") (pintype "input"))
      (node (ref "SW1") (pin "15") (pinfunction "15_15") (pintype "passive"))
    )
    (net (code "86") (name "Net-(IC1A-D2)") (class "Default")
      (node (ref "IC1") (pin "2") (pinfunction "D2_2") (pintype "input"))
      (node (ref "SW1") (pin "14") (pinfunction "14_14") (pintype "passive"))
    )
    (net (code "87") (name "Net-(IC1A-D3)") (class "Default")
      (node (ref "IC1") (pin "1") (pinfunction "D3_1") (pintype "input"))
      (node (ref "SW1") (pin "13") (pinfunction "13_13") (pintype "passive"))
    )
    (net (code "88") (name "Net-(IC1A-D4)") (class "Default")
      (node (ref "IC1") (pin "15") (pinfunction "D4_15") (pintype "input"))
      (node (ref "SW1") (pin "12") (pinfunction "12_12") (pintype "passive"))
    )
    (net (code "89") (name "Net-(IC1A-D5)") (class "Default")
      (node (ref "IC1") (pin "14") (pinfunction "D5_14") (pintype "input"))
      (node (ref "SW1") (pin "11") (pinfunction "11_11") (pintype "passive"))
    )
    (net (code "90") (name "Net-(IC1A-D6)") (class "Default")
      (node (ref "IC1") (pin "13") (pinfunction "D6_13") (pintype "input"))
      (node (ref "SW1") (pin "10") (pinfunction "10_10") (pintype "passive"))
    )
    (net (code "91") (name "Net-(IC1A-D7)") (class "Default")
      (node (ref "IC1") (pin "12") (pinfunction "D7_12") (pintype "input"))
      (node (ref "SW1") (pin "9") (pinfunction "9_9") (pintype "passive"))
    )
    (net (code "92") (name "Net-(IC1A-Y)") (class "Default")
      (node (ref "IC1") (pin "5") (pinfunction "Y_5") (pintype "output"))
      (node (ref "IC5") (pin "1") (pinfunction "I0_1") (pintype "input"))
    )
    (net (code "93") (name "Net-(IC2A-D0)") (class "Default")
      (node (ref "IC2") (pin "4") (pinfunction "D0_4") (pintype "input"))
      (node (ref "SW2") (pin "16") (pinfunction "16_16") (pintype "passive"))
    )
    (net (code "94") (name "Net-(IC2A-D1)") (class "Default")
      (node (ref "IC2") (pin "3") (pinfunction "D1_3") (pintype "input"))
      (node (ref "SW2") (pin "15") (pinfunction "15_15") (pintype "passive"))
    )
    (net (code "95") (name "Net-(IC2A-D2)") (class "Default")
      (node (ref "IC2") (pin "2") (pinfunction "D2_2") (pintype "input"))
      (node (ref "SW2") (pin "14") (pinfunction "14_14") (pintype "passive"))
    )
    (net (code "96") (name "Net-(IC2A-D3)") (class "Default")
      (node (ref "IC2") (pin "1") (pinfunction "D3_1") (pintype "input"))
      (node (ref "SW2") (pin "13") (pinfunction "13_13") (pintype "passive"))
    )
    (net (code "97") (name "Net-(IC2A-D4)") (class "Default")
      (node (ref "IC2") (pin "15") (pinfunction "D4_15") (pintype "input"))
      (node (ref "SW2") (pin "12") (pinfunction "12_12") (pintype "passive"))
    )
    (net (code "98") (name "Net-(IC2A-D5)") (class "Default")
      (node (ref "IC2") (pin "14") (pinfunction "D5_14") (pintype "input"))
      (node (ref "SW2") (pin "11") (pinfunction "11_11") (pintype "passive"))
    )
    (net (code "99") (name "Net-(IC2A-D6)") (class "Default")
      (node (ref "IC2") (pin "13") (pinfunction "D6_13") (pintype "input"))
      (node (ref "SW2") (pin "10") (pinfunction "10_10") (pintype "passive"))
    )
    (net (code "100") (name "Net-(IC2A-D7)") (class "Default")
      (node (ref "IC2") (pin "12") (pinfunction "D7_12") (pintype "input"))
      (node (ref "SW2") (pin "9") (pinfunction "9_9") (pintype "passive"))
    )
    (net (code "101") (name "Net-(IC2A-Y)") (class "Default")
      (node (ref "IC2") (pin "5") (pinfunction "Y_5") (pintype "output"))
      (node (ref "IC5") (pin "2") (pinfunction "I1_2") (pintype "input"))
    )
    (net (code "102") (name "Net-(IC3A-D0)") (class "Default")
      (node (ref "IC3") (pin "4") (pinfunction "D0_4") (pintype "input"))
      (node (ref "SW3") (pin "16") (pinfunction "16_16") (pintype "passive"))
    )
    (net (code "103") (name "Net-(IC3A-D1)") (class "Default")
      (node (ref "IC3") (pin "3") (pinfunction "D1_3") (pintype "input"))
      (node (ref "SW3") (pin "15") (pinfunction "15_15") (pintype "passive"))
    )
    (net (code "104") (name "Net-(IC3A-D2)") (class "Default")
      (node (ref "IC3") (pin "2") (pinfunction "D2_2") (pintype "input"))
      (node (ref "SW3") (pin "14") (pinfunction "14_14") (pintype "passive"))
    )
    (net (code "105") (name "Net-(IC3A-D3)") (class "Default")
      (node (ref "IC3") (pin "1") (pinfunction "D3_1") (pintype "input"))
      (node (ref "SW3") (pin "13") (pinfunction "13_13") (pintype "passive"))
    )
    (net (code "106") (name "Net-(IC3A-D4)") (class "Default")
      (node (ref "IC3") (pin "15") (pinfunction "D4_15") (pintype "input"))
      (node (ref "SW3") (pin "12") (pinfunction "12_12") (pintype "passive"))
    )
    (net (code "107") (name "Net-(IC3A-D5)") (class "Default")
      (node (ref "IC3") (pin "14") (pinfunction "D5_14") (pintype "input"))
      (node (ref "SW3") (pin "11") (pinfunction "11_11") (pintype "passive"))
    )
    (net (code "108") (name "Net-(IC3A-D6)") (class "Default")
      (node (ref "IC3") (pin "13") (pinfunction "D6_13") (pintype "input"))
      (node (ref "SW3") (pin "10") (pinfunction "10_10") (pintype "passive"))
    )
    (net (code "109") (name "Net-(IC3A-D7)") (class "Default")
      (node (ref "IC3") (pin "12") (pinfunction "D7_12") (pintype "input"))
      (node (ref "SW3") (pin "9") (pinfunction "9_9") (pintype "passive"))
    )
    (net (code "110") (name "Net-(IC3A-Y)") (class "Default")
      (node (ref "IC3") (pin "5") (pinfunction "Y_5") (pintype "output"))
      (node (ref "IC5") (pin "4") (pinfunction "I2_4") (pintype "input"))
    )
    (net (code "111") (name "Net-(IC4A-D0)") (class "Default")
      (node (ref "IC4") (pin "4") (pinfunction "D0_4") (pintype "input"))
      (node (ref "SW4") (pin "16") (pinfunction "16_16") (pintype "passive"))
    )
    (net (code "112") (name "Net-(IC4A-D1)") (class "Default")
      (node (ref "IC4") (pin "3") (pinfunction "D1_3") (pintype "input"))
      (node (ref "SW4") (pin "15") (pinfunction "15_15") (pintype "passive"))
    )
    (net (code "113") (name "Net-(IC4A-D2)") (class "Default")
      (node (ref "IC4") (pin "2") (pinfunction "D2_2") (pintype "input"))
      (node (ref "SW4") (pin "14") (pinfunction "14_14") (pintype "passive"))
    )
    (net (code "114") (name "Net-(IC4A-D3)") (class "Default")
      (node (ref "IC4") (pin "1") (pinfunction "D3_1") (pintype "input"))
      (node (ref "SW4") (pin "13") (pinfunction "13_13") (pintype "passive"))
    )
    (net (code "115") (name "Net-(IC4A-D4)") (class "Default")
      (node (ref "IC4") (pin "15") (pinfunction "D4_15") (pintype "input"))
      (node (ref "SW4") (pin "12") (pinfunction "12_12") (pintype "passive"))
    )
    (net (code "116") (name "Net-(IC4A-D5)") (class "Default")
      (node (ref "IC4") (pin "14") (pinfunction "D5_14") (pintype "input"))
      (node (ref "SW4") (pin "11") (pinfunction "11_11") (pintype "passive"))
    )
    (net (code "117") (name "Net-(IC4A-D6)") (class "Default")
      (node (ref "IC4") (pin "13") (pinfunction "D6_13") (pintype "input"))
      (node (ref "SW4") (pin "10") (pinfunction "10_10") (pintype "passive"))
    )
    (net (code "118") (name "Net-(IC4A-D7)") (class "Default")
      (node (ref "IC4") (pin "12") (pinfunction "D7_12") (pintype "input"))
      (node (ref "SW4") (pin "9") (pinfunction "9_9") (pintype "passive"))
    )
    (net (code "119") (name "Net-(IC4A-Y)") (class "Default")
      (node (ref "IC4") (pin "5") (pinfunction "Y_5") (pintype "output"))
      (node (ref "IC5") (pin "5") (pinfunction "I3_5") (pintype "input"))
    )
    (net (code "120") (name "Net-(IC8-CV)") (class "Default")
      (node (ref "C2") (pin "2") (pinfunction "2_2") (pintype "passive"))
      (node (ref "IC8") (pin "5") (pinfunction "CV_5") (pintype "input"))
    )
    (net (code "121") (name "Net-(IC8-DIS)") (class "Default")
      (node (ref "IC8") (pin "7") (pinfunction "DIS_7") (pintype "input"))
      (node (ref "RA") (pin "2") (pinfunction "2_2") (pintype "passive"))
      (node (ref "RB") (pin "1") (pinfunction "1_1") (pintype "passive"))
    )
    (net (code "122") (name "Net-(IC8-THR)") (class "Default")
      (node (ref "C1") (pin "1") (pinfunction "1_1") (pintype "passive"))
      (node (ref "IC8") (pin "2") (pinfunction "TR_2") (pintype "input"))
      (node (ref "IC8") (pin "6") (pinfunction "THR_6") (pintype "input"))
      (node (ref "RB") (pin "2") (pinfunction "2_2") (pintype "passive"))
    )
    (net (code "123") (name "Net-(IC10B-PRE)") (class "Default")
      (node (ref "IC10") (pin "10") (pinfunction "PRE_10") (pintype "input"))
      (node (ref "IC18") (pin "11") (pinfunction "O_11") (pintype "output"))
    )
    (net (code "124") (name "Net-(IC10B-~{Q})") (class "Default")
      (node (ref "IC10") (pin "8") (pinfunction "~{Q}_8") (pintype "output"))
      (node (ref "IC11") (pin "11") (pinfunction "CLK_11") (pintype "input"))
    )
    (net (code "125") (name "Net-(IC12A-I0)") (class "Default")
      (node (ref "IC12") (pin "1") (pinfunction "I0_1") (pintype "input"))
      (node (ref "IC12") (pin "2") (pinfunction "I1_2") (pintype "input"))
      (node (ref "IC8") (pin "3") (pinfunction "Q_3") (pintype "output"))
      (node (ref "RL") (pin "2") (pinfunction "2_2") (pintype "passive"))
    )
    (net (code "126") (name "Net-(IC12B-I1)") (class "Default")
      (node (ref "IC12") (pin "5") (pinfunction "I1_5") (pintype "input"))
      (node (ref "IC12") (pin "8") (pinfunction "O_8") (pintype "output"))
    )
    (net (code "127") (name "Net-(IC12C-I0)") (class "Default")
      (node (ref "IC12") (pin "10") (pinfunction "I1_10") (pintype "input"))
      (node (ref "IC12") (pin "11") (pinfunction "O_11") (pintype "output"))
      (node (ref "IC12") (pin "9") (pinfunction "I0_9") (pintype "input"))
    )
    (net (code "128") (name "Net-(IC13A-A)") (class "Default")
      (node (ref "IC13") (pin "8") (pinfunction "A_8") (pintype "input"))
      (node (ref "IC14") (pin "8") (pinfunction "A_8") (pintype "input"))
      (node (ref "IC15") (pin "6") (pinfunction "ODD_6") (pintype "output"))
    )
    (net (code "129") (name "Net-(IC16B-Y1)") (class "Default")
      (node (ref "IC16") (pin "11") (pinfunction "Y1_11") (pintype "output"))
      (node (ref "IC22") (pin "1") (pinfunction "I_1") (pintype "input"))
    )
    (net (code "130") (name "Net-(IC17A-Y0)") (class "Default")
      (node (ref "IC17") (pin "4") (pinfunction "Y0_4") (pintype "output"))
      (node (ref "IC22") (pin "11") (pinfunction "I_11") (pintype "input"))
    )
    (net (code "131") (name "Net-(IC19A-I)") (class "Default")
      (node (ref "IC19") (pin "1") (pinfunction "I_1") (pintype "input"))
      (node (ref "IC7") (pin "5") (pinfunction "Y1_5") (pintype "output"))
    )
    (net (code "132") (name "Net-(IC19E-I)") (class "Default")
      (node (ref "IC19") (pin "11") (pinfunction "I_11") (pintype "input"))
      (node (ref "IC7") (pin "12") (pinfunction "Y0_12") (pintype "output"))
    )
    (net (code "133") (name "Net-(IC21A-Y0)") (class "Default")
      (node (ref "IC21") (pin "4") (pinfunction "Y0_4") (pintype "output"))
      (node (ref "SW1") (pin "1") (pinfunction "1_1") (pintype "passive"))
      (node (ref "SW1") (pin "2") (pinfunction "2_2") (pintype "passive"))
      (node (ref "SW1") (pin "3") (pinfunction "3_3") (pintype "passive"))
      (node (ref "SW1") (pin "4") (pinfunction "4_4") (pintype "passive"))
      (node (ref "SW1") (pin "5") (pinfunction "5_5") (pintype "passive"))
      (node (ref "SW1") (pin "6") (pinfunction "6_6") (pintype "passive"))
      (node (ref "SW1") (pin "7") (pinfunction "7_7") (pintype "passive"))
      (node (ref "SW1") (pin "8") (pinfunction "8_8") (pintype "passive"))
    )
    (net (code "134") (name "Net-(IC21A-Y1)") (class "Default")
      (node (ref "IC21") (pin "5") (pinfunction "Y1_5") (pintype "output"))
      (node (ref "SW2") (pin "1") (pinfunction "1_1") (pintype "passive"))
      (node (ref "SW2") (pin "2") (pinfunction "2_2") (pintype "passive"))
      (node (ref "SW2") (pin "3") (pinfunction "3_3") (pintype "passive"))
      (node (ref "SW2") (pin "4") (pinfunction "4_4") (pintype "passive"))
      (node (ref "SW2") (pin "5") (pinfunction "5_5") (pintype "passive"))
      (node (ref "SW2") (pin "6") (pinfunction "6_6") (pintype "passive"))
      (node (ref "SW2") (pin "7") (pinfunction "7_7") (pintype "passive"))
      (node (ref "SW2") (pin "8") (pinfunction "8_8") (pintype "passive"))
    )
    (net (code "135") (name "Net-(IC21A-Y2)") (class "Default")
      (node (ref "IC21") (pin "6") (pinfunction "Y2_6") (pintype "output"))
      (node (ref "SW3") (pin "1") (pinfunction "1_1") (pintype "passive"))
      (node (ref "SW3") (pin "2") (pinfunction "2_2") (pintype "passive"))
      (node (ref "SW3") (pin "3") (pinfunction "3_3") (pintype "passive"))
      (node (ref "SW3") (pin "4") (pinfunction "4_4") (pintype "passive"))
      (node (ref "SW3") (pin "5") (pinfunction "5_5") (pintype "passive"))
      (node (ref "SW3") (pin "6") (pinfunction "6_6") (pintype "passive"))
      (node (ref "SW3") (pin "7") (pinfunction "7_7") (pintype "passive"))
      (node (ref "SW3") (pin "8") (pinfunction "8_8") (pintype "passive"))
    )
    (net (code "136") (name "Net-(IC21A-Y3)") (class "Default")
      (node (ref "IC21") (pin "7") (pinfunction "Y3_7") (pintype "output"))
      (node (ref "SW4") (pin "1") (pinfunction "1_1") (pintype "passive"))
      (node (ref "SW4") (pin "2") (pinfunction "2_2") (pintype "passive"))
      (node (ref "SW4") (pin "3") (pinfunction "3_3") (pintype "passive"))
      (node (ref "SW4") (pin "4") (pinfunction "4_4") (pintype "passive"))
      (node (ref "SW4") (pin "5") (pinfunction "5_5") (pintype "passive"))
      (node (ref "SW4") (pin "6") (pinfunction "6_6") (pintype "passive"))
      (node (ref "SW4") (pin "7") (pinfunction "7_7") (pintype "passive"))
      (node (ref "SW4") (pin "8") (pinfunction "8_8") (pintype "passive"))
    )
    (net (code "137") (name "Net-(IC27A-O)") (class "Default")
      (node (ref "IC27") (pin "2") (pinfunction "O_2") (pintype "output"))
      (node (ref "LED1") (pin "K") (pinfunction "C_K") (pintype "passive"))
    )
    (net (code "138") (name "Net-(IC27B-O)") (class "Default")
      (node (ref "IC27") (pin "4") (pinfunction "O_4") (pintype "output"))
      (node (ref "LED2") (pin "K") (pinfunction "C_K") (pintype "passive"))
    )
    (net (code "139") (name "Net-(IC27C-O)") (class "Default")
      (node (ref "IC27") (pin "6") (pinfunction "O_6") (pintype "output"))
      (node (ref "LED3") (pin "K") (pinfunction "C_K") (pintype "passive"))
    )
    (net (code "140") (name "Net-(IC27D-O)") (class "Default")
      (node (ref "IC27") (pin "8") (pinfunction "O_8") (pintype "output"))
      (node (ref "LED13") (pin "K") (pinfunction "C_K") (pintype "passive"))
    )
    (net (code "141") (name "Net-(IC27E-O)") (class "Default")
      (node (ref "IC27") (pin "10") (pinfunction "O_10") (pintype "output"))
      (node (ref "LED14") (pin "K") (pinfunction "C_K") (pintype "passive"))
    )
    (net (code "142") (name "Net-(IC27F-O)") (class "Default")
      (node (ref "IC27") (pin "12") (pinfunction "O_12") (pintype "output"))
      (node (ref "LED15") (pin "K") (pinfunction "C_K") (pintype "passive"))
    )
    (net (code "143") (name "Net-(IC33A-O)") (class "Default")
      (node (ref "IC33") (pin "2") (pinfunction "O_2") (pintype "output"))
      (node (ref "LED25") (pin "K") (pinfunction "C_K") (pintype "passive"))
    )
    (net (code "144") (name "Net-(IC33B-O)") (class "Default")
      (node (ref "IC33") (pin "4") (pinfunction "O_4") (pintype "output"))
      (node (ref "LED26") (pin "K") (pinfunction "C_K") (pintype "passive"))
    )
    (net (code "145") (name "Net-(IC33C-O)") (class "Default")
      (node (ref "IC33") (pin "6") (pinfunction "O_6") (pintype "output"))
      (node (ref "LED27") (pin "K") (pinfunction "C_K") (pintype "passive"))
    )
    (net (code "146") (name "Net-(IC33D-O)") (class "Default")
      (node (ref "IC33") (pin "8") (pinfunction "O_8") (pintype "output"))
      (node (ref "LED37") (pin "K") (pinfunction "C_K") (pintype "passive"))
    )
    (net (code "147") (name "Net-(IC33E-O)") (class "Default")
      (node (ref "IC33") (pin "10") (pinfunction "O_10") (pintype "output"))
      (node (ref "LED38") (pin "K") (pinfunction "C_K") (pintype "passive"))
    )
    (net (code "148") (name "Net-(IC33F-O)") (class "Default")
      (node (ref "IC33") (pin "12") (pinfunction "O_12") (pintype "output"))
      (node (ref "LED39") (pin "K") (pinfunction "C_K") (pintype "passive"))
    )
    (net (code "149") (name "Net-(IC36A-Y0)") (class "Default")
      (node (ref "IC36") (pin "15") (pinfunction "Y0_15") (pintype "output"))
      (node (ref "PAD2") (pin "1") (pinfunction "P_1") (pintype "passive"))
    )
    (net (code "150") (name "Net-(IC36A-Y1)") (class "Default")
      (node (ref "IC36") (pin "14") (pinfunction "Y1_14") (pintype "output"))
      (node (ref "PAD3") (pin "1") (pinfunction "P_1") (pintype "passive"))
    )
    (net (code "151") (name "Net-(IC36A-Y2)") (class "Default")
      (node (ref "IC36") (pin "13") (pinfunction "Y2_13") (pintype "output"))
      (node (ref "PAD4") (pin "1") (pinfunction "P_1") (pintype "passive"))
    )
    (net (code "152") (name "Net-(IC36A-Y3)") (class "Default")
      (node (ref "IC36") (pin "12") (pinfunction "Y3_12") (pintype "output"))
      (node (ref "PAD5") (pin "1") (pinfunction "P_1") (pintype "passive"))
    )
    (net (code "153") (name "Net-(IC36A-Y4)") (class "Default")
      (node (ref "IC36") (pin "11") (pinfunction "Y4_11") (pintype "output"))
      (node (ref "PAD6") (pin "1") (pinfunction "P_1") (pintype "passive"))
    )
    (net (code "154") (name "Net-(IC36A-Y5)") (class "Default")
      (node (ref "IC36") (pin "10") (pinfunction "Y5_10") (pintype "output"))
      (node (ref "PAD7") (pin "1") (pinfunction "P_1") (pintype "passive"))
    )
    (net (code "155") (name "Net-(IC36A-Y6)") (class "Default")
      (node (ref "IC36") (pin "9") (pinfunction "Y6_9") (pintype "output"))
      (node (ref "PAD8") (pin "1") (pinfunction "P_1") (pintype "passive"))
    )
    (net (code "156") (name "Net-(IC36A-Y7)") (class "Default")
      (node (ref "IC36") (pin "7") (pinfunction "Y7_7") (pintype "output"))
      (node (ref "PAD9") (pin "1") (pinfunction "P_1") (pintype "passive"))
    )
    (net (code "157") (name "Net-(IC39B-O)") (class "Default")
      (node (ref "IC39") (pin "4") (pinfunction "O_4") (pintype "output"))
      (node (ref "LED5") (pin "K") (pinfunction "C_K") (pintype "passive"))
    )
    (net (code "158") (name "Net-(IC39C-O)") (class "Default")
      (node (ref "IC39") (pin "6") (pinfunction "O_6") (pintype "output"))
      (node (ref "LED6") (pin "K") (pinfunction "C_K") (pintype "passive"))
    )
    (net (code "159") (name "Net-(IC39D-O)") (class "Default")
      (node (ref "IC39") (pin "8") (pinfunction "O_8") (pintype "output"))
      (node (ref "LED16") (pin "K") (pinfunction "C_K") (pintype "passive"))
    )
    (net (code "160") (name "Net-(IC39E-O)") (class "Default")
      (node (ref "IC39") (pin "10") (pinfunction "O_10") (pintype "output"))
      (node (ref "LED17") (pin "K") (pinfunction "C_K") (pintype "passive"))
    )
    (net (code "161") (name "Net-(IC39F-O)") (class "Default")
      (node (ref "IC39") (pin "12") (pinfunction "O_12") (pintype "output"))
      (node (ref "LED18") (pin "K") (pinfunction "C_K") (pintype "passive"))
    )
    (net (code "162") (name "Net-(IC42A-O)") (class "Default")
      (node (ref "IC42") (pin "2") (pinfunction "O_2") (pintype "output"))
      (node (ref "LED28") (pin "K") (pinfunction "C_K") (pintype "passive"))
    )
    (net (code "163") (name "Net-(IC42B-O)") (class "Default")
      (node (ref "IC42") (pin "4") (pinfunction "O_4") (pintype "output"))
      (node (ref "LED29") (pin "K") (pinfunction "C_K") (pintype "passive"))
    )
    (net (code "164") (name "Net-(IC42C-O)") (class "Default")
      (node (ref "IC42") (pin "6") (pinfunction "O_6") (pintype "output"))
      (node (ref "LED30") (pin "K") (pinfunction "C_K") (pintype "passive"))
    )
    (net (code "165") (name "Net-(IC42E-O)") (class "Default")
      (node (ref "IC42") (pin "10") (pinfunction "O_10") (pintype "output"))
      (node (ref "LED41") (pin "K") (pinfunction "C_K") (pintype "passive"))
    )
    (net (code "166") (name "Net-(IC42F-O)") (class "Default")
      (node (ref "IC42") (pin "12") (pinfunction "O_12") (pintype "output"))
      (node (ref "LED42") (pin "K") (pinfunction "C_K") (pintype "passive"))
    )
    (net (code "167") (name "Net-(IC43A-O)") (class "Default")
      (node (ref "IC43") (pin "2") (pinfunction "O_2") (pintype "output"))
      (node (ref "LED7") (pin "K") (pinfunction "C_K") (pintype "passive"))
    )
    (net (code "168") (name "Net-(IC43B-O)") (class "Default")
      (node (ref "IC43") (pin "4") (pinfunction "O_4") (pintype "output"))
      (node (ref "LED8") (pin "K") (pinfunction "C_K") (pintype "passive"))
    )
    (net (code "169") (name "Net-(IC43C-O)") (class "Default")
      (node (ref "IC43") (pin "6") (pinfunction "O_6") (pintype "output"))
      (node (ref "LED9") (pin "K") (pinfunction "C_K") (pintype "passive"))
    )
    (net (code "170") (name "Net-(IC43D-O)") (class "Default")
      (node (ref "IC43") (pin "8") (pinfunction "O_8") (pintype "output"))
      (node (ref "LED19") (pin "K") (pinfunction "C_K") (pintype "passive"))
    )
    (net (code "171") (name "Net-(IC43E-O)") (class "Default")
      (node (ref "IC43") (pin "10") (pinfunction "O_10") (pintype "output"))
      (node (ref "LED20") (pin "K") (pinfunction "C_K") (pintype "passive"))
    )
    (net (code "172") (name "Net-(IC43F-O)") (class "Default")
      (node (ref "IC43") (pin "12") (pinfunction "O_12") (pintype "output"))
      (node (ref "LED21") (pin "K") (pinfunction "C_K") (pintype "passive"))
    )
    (net (code "173") (name "Net-(IC44A-O)") (class "Default")
      (node (ref "IC44") (pin "2") (pinfunction "O_2") (pintype "output"))
      (node (ref "LED31") (pin "K") (pinfunction "C_K") (pintype "passive"))
    )
    (net (code "174") (name "Net-(IC44B-O)") (class "Default")
      (node (ref "IC44") (pin "4") (pinfunction "O_4") (pintype "output"))
      (node (ref "LED32") (pin "K") (pinfunction "C_K") (pintype "passive"))
    )
    (net (code "175") (name "Net-(IC44C-O)") (class "Default")
      (node (ref "IC44") (pin "6") (pinfunction "O_6") (pintype "output"))
      (node (ref "LED33") (pin "K") (pinfunction "C_K") (pintype "passive"))
    )
    (net (code "176") (name "Net-(IC44E-O)") (class "Default")
      (node (ref "IC44") (pin "10") (pinfunction "O_10") (pintype "output"))
      (node (ref "LED44") (pin "K") (pinfunction "C_K") (pintype "passive"))
    )
    (net (code "177") (name "Net-(IC44F-O)") (class "Default")
      (node (ref "IC44") (pin "12") (pinfunction "O_12") (pintype "output"))
      (node (ref "LED45") (pin "K") (pinfunction "C_K") (pintype "passive"))
    )
    (net (code "178") (name "Net-(IC45A-O)") (class "Default")
      (node (ref "IC45") (pin "2") (pinfunction "O_2") (pintype "output"))
      (node (ref "LED10") (pin "K") (pinfunction "C_K") (pintype "passive"))
    )
    (net (code "179") (name "Net-(IC45B-O)") (class "Default")
      (node (ref "IC45") (pin "4") (pinfunction "O_4") (pintype "output"))
      (node (ref "LED11") (pin "K") (pinfunction "C_K") (pintype "passive"))
    )
    (net (code "180") (name "Net-(IC45C-O)") (class "Default")
      (node (ref "IC45") (pin "6") (pinfunction "O_6") (pintype "output"))
      (node (ref "LED12") (pin "K") (pinfunction "C_K") (pintype "passive"))
    )
    (net (code "181") (name "Net-(IC45D-O)") (class "Default")
      (node (ref "IC45") (pin "8") (pinfunction "O_8") (pintype "output"))
      (node (ref "LED22") (pin "K") (pinfunction "C_K") (pintype "passive"))
    )
    (net (code "182") (name "Net-(IC45E-O)") (class "Default")
      (node (ref "IC45") (pin "10") (pinfunction "O_10") (pintype "output"))
      (node (ref "LED23") (pin "K") (pinfunction "C_K") (pintype "passive"))
    )
    (net (code "183") (name "Net-(IC45F-O)") (class "Default")
      (node (ref "IC45") (pin "12") (pinfunction "O_12") (pintype "output"))
      (node (ref "LED24") (pin "K") (pinfunction "C_K") (pintype "passive"))
    )
    (net (code "184") (name "Net-(IC46A-O)") (class "Default")
      (node (ref "IC46") (pin "2") (pinfunction "O_2") (pintype "output"))
      (node (ref "LED34") (pin "K") (pinfunction "C_K") (pintype "passive"))
    )
    (net (code "185") (name "Net-(IC46B-O)") (class "Default")
      (node (ref "IC46") (pin "4") (pinfunction "O_4") (pintype "output"))
      (node (ref "LED35") (pin "K") (pinfunction "C_K") (pintype "passive"))
    )
    (net (code "186") (name "Net-(IC46C-O)") (class "Default")
      (node (ref "IC46") (pin "6") (pinfunction "O_6") (pintype "output"))
      (node (ref "LED36") (pin "K") (pinfunction "C_K") (pintype "passive"))
    )
    (net (code "187") (name "Net-(IC46D-O)") (class "Default")
      (node (ref "IC46") (pin "8") (pinfunction "O_8") (pintype "output"))
      (node (ref "LED46") (pin "K") (pinfunction "C_K") (pintype "passive"))
    )
    (net (code "188") (name "Net-(IC46E-O)") (class "Default")
      (node (ref "IC46") (pin "10") (pinfunction "O_10") (pintype "output"))
      (node (ref "LED47") (pin "K") (pinfunction "C_K") (pintype "passive"))
    )
    (net (code "189") (name "Net-(IC46F-O)") (class "Default")
      (node (ref "IC46") (pin "12") (pinfunction "O_12") (pintype "output"))
      (node (ref "LED48") (pin "K") (pinfunction "C_K") (pintype "passive"))
    )
    (net (code "190") (name "Net-(LED1-PadA)") (class "Default")
      (node (ref "LED1") (pin "A") (pinfunction "A_A") (pintype "passive"))
      (node (ref "R3") (pin "1") (pinfunction "1_1") (pintype "passive"))
    )
    (net (code "191") (name "Net-(LED2-PadA)") (class "Default")
      (node (ref "LED2") (pin "A") (pinfunction "A_A") (pintype "passive"))
      (node (ref "R4") (pin "1") (pinfunction "1_1") (pintype "passive"))
    )
    (net (code "192") (name "Net-(LED3-PadA)") (class "Default")
      (node (ref "LED3") (pin "A") (pinfunction "A_A") (pintype "passive"))
      (node (ref "R5") (pin "1") (pinfunction "1_1") (pintype "passive"))
    )
    (net (code "193") (name "Net-(LED4-C)") (class "Default")
      (node (ref "LED4") (pin "K") (pinfunction "C_K") (pintype "passive"))
      (node (ref "PAD12") (pin "1") (pinfunction "P_1") (pintype "passive"))
    )
    (net (code "194") (name "Net-(LED4-PadA)") (class "Default")
      (node (ref "LED4") (pin "A") (pinfunction "A_A") (pintype "passive"))
      (node (ref "R6") (pin "1") (pinfunction "1_1") (pintype "passive"))
    )
    (net (code "195") (name "Net-(LED5-PadA)") (class "Default")
      (node (ref "LED5") (pin "A") (pinfunction "A_A") (pintype "passive"))
      (node (ref "R7") (pin "1") (pinfunction "1_1") (pintype "passive"))
    )
    (net (code "196") (name "Net-(LED6-PadA)") (class "Default")
      (node (ref "LED6") (pin "A") (pinfunction "A_A") (pintype "passive"))
      (node (ref "R8") (pin "1") (pinfunction "1_1") (pintype "passive"))
    )
    (net (code "197") (name "Net-(LED7-PadA)") (class "Default")
      (node (ref "LED7") (pin "A") (pinfunction "A_A") (pintype "passive"))
      (node (ref "R9") (pin "1") (pinfunction "1_1") (pintype "passive"))
    )
    (net (code "198") (name "Net-(LED8-PadA)") (class "Default")
      (node (ref "LED8") (pin "A") (pinfunction "A_A") (pintype "passive"))
      (node (ref "R10") (pin "1") (pinfunction "1_1") (pintype "passive"))
    )
    (net (code "199") (name "Net-(LED9-PadA)") (class "Default")
      (node (ref "LED9") (pin "A") (pinfunction "A_A") (pintype "passive"))
      (node (ref "R11") (pin "1") (pinfunction "1_1") (pintype "passive"))
    )
    (net (code "200") (name "Net-(LED10-PadA)") (class "Default")
      (node (ref "LED10") (pin "A") (pinfunction "A_A") (pintype "passive"))
      (node (ref "R12") (pin "1") (pinfunction "1_1") (pintype "passive"))
    )
    (net (code "201") (name "Net-(LED11-PadA)") (class "Default")
      (node (ref "LED11") (pin "A") (pinfunction "A_A") (pintype "passive"))
      (node (ref "R13") (pin "1") (pinfunction "1_1") (pintype "passive"))
    )
    (net (code "202") (name "Net-(LED12-PadA)") (class "Default")
      (node (ref "LED12") (pin "A") (pinfunction "A_A") (pintype "passive"))
      (node (ref "R14") (pin "1") (pinfunction "1_1") (pintype "passive"))
    )
    (net (code "203") (name "Net-(LED13-PadA)") (class "Default")
      (node (ref "LED13") (pin "A") (pinfunction "A_A") (pintype "passive"))
      (node (ref "R15") (pin "1") (pinfunction "1_1") (pintype "passive"))
    )
    (net (code "204") (name "Net-(LED14-PadA)") (class "Default")
      (node (ref "LED14") (pin "A") (pinfunction "A_A") (pintype "passive"))
      (node (ref "R16") (pin "1") (pinfunction "1_1") (pintype "passive"))
    )
    (net (code "205") (name "Net-(LED15-PadA)") (class "Default")
      (node (ref "LED15") (pin "A") (pinfunction "A_A") (pintype "passive"))
      (node (ref "R17") (pin "1") (pinfunction "1_1") (pintype "passive"))
    )
    (net (code "206") (name "Net-(LED16-PadA)") (class "Default")
      (node (ref "LED16") (pin "A") (pinfunction "A_A") (pintype "passive"))
      (node (ref "R18") (pin "1") (pinfunction "1_1") (pintype "passive"))
    )
    (net (code "207") (name "Net-(LED17-PadA)") (class "Default")
      (node (ref "LED17") (pin "A") (pinfunction "A_A") (pintype "passive"))
      (node (ref "R19") (pin "1") (pinfunction "1_1") (pintype "passive"))
    )
    (net (code "208") (name "Net-(LED18-PadA)") (class "Default")
      (node (ref "LED18") (pin "A") (pinfunction "A_A") (pintype "passive"))
      (node (ref "R20") (pin "1") (pinfunction "1_1") (pintype "passive"))
    )
    (net (code "209") (name "Net-(LED19-PadA)") (class "Default")
      (node (ref "LED19") (pin "A") (pinfunction "A_A") (pintype "passive"))
      (node (ref "R21") (pin "1") (pinfunction "1_1") (pintype "passive"))
    )
    (net (code "210") (name "Net-(LED20-PadA)") (class "Default")
      (node (ref "LED20") (pin "A") (pinfunction "A_A") (pintype "passive"))
      (node (ref "R22") (pin "1") (pinfunction "1_1") (pintype "passive"))
    )
    (net (code "211") (name "Net-(LED21-PadA)") (class "Default")
      (node (ref "LED21") (pin "A") (pinfunction "A_A") (pintype "passive"))
      (node (ref "R23") (pin "1") (pinfunction "1_1") (pintype "passive"))
    )
    (net (code "212") (name "Net-(LED22-PadA)") (class "Default")
      (node (ref "LED22") (pin "A") (pinfunction "A_A") (pintype "passive"))
      (node (ref "R24") (pin "1") (pinfunction "1_1") (pintype "passive"))
    )
    (net (code "213") (name "Net-(LED23-PadA)") (class "Default")
      (node (ref "LED23") (pin "A") (pinfunction "A_A") (pintype "passive"))
      (node (ref "R25") (pin "1") (pinfunction "1_1") (pintype "passive"))
    )
    (net (code "214") (name "Net-(LED24-PadA)") (class "Default")
      (node (ref "LED24") (pin "A") (pinfunction "A_A") (pintype "passive"))
      (node (ref "R26") (pin "1") (pinfunction "1_1") (pintype "passive"))
    )
    (net (code "215") (name "Net-(LED25-PadA)") (class "Default")
      (node (ref "LED25") (pin "A") (pinfunction "A_A") (pintype "passive"))
      (node (ref "R27") (pin "1") (pinfunction "1_1") (pintype "passive"))
    )
    (net (code "216") (name "Net-(LED26-PadA)") (class "Default")
      (node (ref "LED26") (pin "A") (pinfunction "A_A") (pintype "passive"))
      (node (ref "R28") (pin "1") (pinfunction "1_1") (pintype "passive"))
    )
    (net (code "217") (name "Net-(LED27-PadA)") (class "Default")
      (node (ref "LED27") (pin "A") (pinfunction "A_A") (pintype "passive"))
      (node (ref "R29") (pin "1") (pinfunction "1_1") (pintype "passive"))
    )
    (net (code "218") (name "Net-(LED28-PadA)") (class "Default")
      (node (ref "LED28") (pin "A") (pinfunction "A_A") (pintype "passive"))
      (node (ref "R30") (pin "1") (pinfunction "1_1") (pintype "passive"))
    )
    (net (code "219") (name "Net-(LED29-PadA)") (class "Default")
      (node (ref "LED29") (pin "A") (pinfunction "A_A") (pintype "passive"))
      (node (ref "R31") (pin "1") (pinfunction "1_1") (pintype "passive"))
    )
    (net (code "220") (name "Net-(LED30-PadA)") (class "Default")
      (node (ref "LED30") (pin "A") (pinfunction "A_A") (pintype "passive"))
      (node (ref "R32") (pin "1") (pinfunction "1_1") (pintype "passive"))
    )
    (net (code "221") (name "Net-(LED31-PadA)") (class "Default")
      (node (ref "LED31") (pin "A") (pinfunction "A_A") (pintype "passive"))
      (node (ref "R33") (pin "1") (pinfunction "1_1") (pintype "passive"))
    )
    (net (code "222") (name "Net-(LED32-PadA)") (class "Default")
      (node (ref "LED32") (pin "A") (pinfunction "A_A") (pintype "passive"))
      (node (ref "R34") (pin "1") (pinfunction "1_1") (pintype "passive"))
    )
    (net (code "223") (name "Net-(LED33-PadA)") (class "Default")
      (node (ref "LED33") (pin "A") (pinfunction "A_A") (pintype "passive"))
      (node (ref "R35") (pin "1") (pinfunction "1_1") (pintype "passive"))
    )
    (net (code "224") (name "Net-(LED34-PadA)") (class "Default")
      (node (ref "LED34") (pin "A") (pinfunction "A_A") (pintype "passive"))
      (node (ref "R36") (pin "1") (pinfunction "1_1") (pintype "passive"))
    )
    (net (code "225") (name "Net-(LED35-PadA)") (class "Default")
      (node (ref "LED35") (pin "A") (pinfunction "A_A") (pintype "passive"))
      (node (ref "R37") (pin "1") (pinfunction "1_1") (pintype "passive"))
    )
    (net (code "226") (name "Net-(LED36-PadA)") (class "Default")
      (node (ref "LED36") (pin "A") (pinfunction "A_A") (pintype "passive"))
      (node (ref "R38") (pin "1") (pinfunction "1_1") (pintype "passive"))
    )
    (net (code "227") (name "Net-(LED37-PadA)") (class "Default")
      (node (ref "LED37") (pin "A") (pinfunction "A_A") (pintype "passive"))
      (node (ref "R39") (pin "1") (pinfunction "1_1") (pintype "passive"))
    )
    (net (code "228") (name "Net-(LED38-PadA)") (class "Default")
      (node (ref "LED38") (pin "A") (pinfunction "A_A") (pintype "passive"))
      (node (ref "R40") (pin "1") (pinfunction "1_1") (pintype "passive"))
    )
    (net (code "229") (name "Net-(LED39-PadA)") (class "Default")
      (node (ref "LED39") (pin "A") (pinfunction "A_A") (pintype "passive"))
      (node (ref "R41") (pin "1") (pinfunction "1_1") (pintype "passive"))
    )
    (net (code "230") (name "Net-(LED40-C)") (class "Default")
      (node (ref "LED40") (pin "K") (pinfunction "C_K") (pintype "passive"))
      (node (ref "PAD10") (pin "1") (pinfunction "P_1") (pintype "passive"))
    )
    (net (code "231") (name "Net-(LED40-PadA)") (class "Default")
      (node (ref "LED40") (pin "A") (pinfunction "A_A") (pintype "passive"))
      (node (ref "R42") (pin "1") (pinfunction "1_1") (pintype "passive"))
    )
    (net (code "232") (name "Net-(LED41-PadA)") (class "Default")
      (node (ref "LED41") (pin "A") (pinfunction "A_A") (pintype "passive"))
      (node (ref "R43") (pin "1") (pinfunction "1_1") (pintype "passive"))
    )
    (net (code "233") (name "Net-(LED42-PadA)") (class "Default")
      (node (ref "LED42") (pin "A") (pinfunction "A_A") (pintype "passive"))
      (node (ref "R44") (pin "1") (pinfunction "1_1") (pintype "passive"))
    )
    (net (code "234") (name "Net-(LED43-C)") (class "Default")
      (node (ref "LED43") (pin "K") (pinfunction "C_K") (pintype "passive"))
      (node (ref "PAD11") (pin "1") (pinfunction "P_1") (pintype "passive"))
    )
    (net (code "235") (name "Net-(LED43-PadA)") (class "Default")
      (node (ref "LED43") (pin "A") (pinfunction "A_A") (pintype "passive"))
      (node (ref "R45") (pin "1") (pinfunction "1_1") (pintype "passive"))
    )
    (net (code "236") (name "Net-(LED44-PadA)") (class "Default")
      (node (ref "LED44") (pin "A") (pinfunction "A_A") (pintype "passive"))
      (node (ref "R46") (pin "1") (pinfunction "1_1") (pintype "passive"))
    )
    (net (code "237") (name "Net-(LED45-PadA)") (class "Default")
      (node (ref "LED45") (pin "A") (pinfunction "A_A") (pintype "passive"))
      (node (ref "R47") (pin "1") (pinfunction "1_1") (pintype "passive"))
    )
    (net (code "238") (name "Net-(LED46-PadA)") (class "Default")
      (node (ref "LED46") (pin "A") (pinfunction "A_A") (pintype "passive"))
      (node (ref "R48") (pin "1") (pinfunction "1_1") (pintype "passive"))
    )
    (net (code "239") (name "Net-(LED47-PadA)") (class "Default")
      (node (ref "LED47") (pin "A") (pinfunction "A_A") (pintype "passive"))
      (node (ref "R49") (pin "1") (pinfunction "1_1") (pintype "passive"))
    )
    (net (code "240") (name "Net-(LED48-PadA)") (class "Default")
      (node (ref "LED48") (pin "A") (pinfunction "A_A") (pintype "passive"))
      (node (ref "R50") (pin "1") (pinfunction "1_1") (pintype "passive"))
    )
    (net (code "241") (name "PBIT") (class "Default")
      (node (ref "IC14") (pin "6") (pinfunction "ODD_6") (pintype "output"))
      (node (ref "IC35") (pin "11") (pinfunction "A1_11") (pintype "input"))
    )
    (net (code "242") (name "PCA") (class "Default")
      (node (ref "IC12") (pin "3") (pinfunction "O_3") (pintype "output"))
      (node (ref "IC37") (pin "8") (pinfunction "A4_8") (pintype "input"))
      (node (ref "IC40") (pin "5") (pinfunction "I1_5") (pintype "input"))
    )
    (net (code "243") (name "PER") (class "Default")
      (node (ref "IC30") (pin "2") (pinfunction "A1_2") (pintype "input"))
      (node (ref "IC46") (pin "11") (pinfunction "I_11") (pintype "input"))
      (node (ref "IC9") (pin "9") (pinfunction "Q_9") (pintype "output"))
    )
    (net (code "244") (name "PIE") (class "Default")
      (node (ref "IC30") (pin "17") (pinfunction "A4_17") (pintype "input"))
      (node (ref "IC33") (pin "13") (pinfunction "I_13") (pintype "input"))
      (node (ref "IC40") (pin "4") (pinfunction "I0_4") (pintype "input"))
      (node (ref "INTENB") (pin "2") (pinfunction "QB_2") (pintype "output"))
    )
    (net (code "245") (name "PROTECT") (class "Default")
      (node (ref "IC5") (pin "6") (pinfunction "O_6") (pintype "output"))
      (node (ref "IC6") (pin "3") (pinfunction "B_3") (pintype "input"))
    )
    (net (code "246") (name "VCC") (class "Default")
      (node (ref "C2") (pin "1") (pinfunction "1_1") (pintype "passive"))
      (node (ref "IC11") (pin "10") (pinfunction "PRE_10") (pintype "input"))
      (node (ref "IC11") (pin "4") (pinfunction "PRE_4") (pintype "input"))
      (node (ref "IC13") (pin "3") (pinfunction "EI_3") (pintype "input"))
      (node (ref "IC14") (pin "3") (pinfunction "EI_3") (pintype "input"))
      (node (ref "IC15") (pin "3") (pinfunction "EI_3") (pintype "input"))
      (node (ref "IC36") (pin "6") (pinfunction "G1_6") (pintype "input"))
      (node (ref "IC8") (pin "4") (pinfunction "R_4") (pintype "input"))
      (node (ref "IC8") (pin "8") (pinfunction "V+_8") (pintype "power_in"))
      (node (ref "J3") (pin "2") (pinfunction "2_2") (pintype "passive"))
      (node (ref "J4") (pin "2") (pinfunction "2_2") (pintype "passive"))
      (node (ref "J5") (pin "2") (pinfunction "2_2") (pintype "passive"))
      (node (ref "J7") (pin "2") (pinfunction "2_2") (pintype "passive"))
      (node (ref "R1") (pin "2") (pinfunction "2_2") (pintype "passive"))
      (node (ref "R10") (pin "2") (pinfunction "2_2") (pintype "passive"))
      (node (ref "R11") (pin "2") (pinfunction "2_2") (pintype "passive"))
      (node (ref "R12") (pin "2") (pinfunction "2_2") (pintype "passive"))
      (node (ref "R13") (pin "2") (pinfunction "2_2") (pintype "passive"))
      (node (ref "R14") (pin "2") (pinfunction "2_2") (pintype "passive"))
      (node (ref "R15") (pin "2") (pinfunction "2_2") (pintype "passive"))
      (node (ref "R16") (pin "2") (pinfunction "2_2") (pintype "passive"))
      (node (ref "R17") (pin "2") (pinfunction "2_2") (pintype "passive"))
      (node (ref "R18") (pin "2") (pinfunction "2_2") (pintype "passive"))
      (node (ref "R19") (pin "2") (pinfunction "2_2") (pintype "passive"))
      (node (ref "R2") (pin "2") (pinfunction "2_2") (pintype "passive"))
      (node (ref "R20") (pin "2") (pinfunction "2_2") (pintype "passive"))
      (node (ref "R21") (pin "2") (pinfunction "2_2") (pintype "passive"))
      (node (ref "R22") (pin "2") (pinfunction "2_2") (pintype "passive"))
      (node (ref "R23") (pin "2") (pinfunction "2_2") (pintype "passive"))
      (node (ref "R24") (pin "2") (pinfunction "2_2") (pintype "passive"))
      (node (ref "R25") (pin "2") (pinfunction "2_2") (pintype "passive"))
      (node (ref "R26") (pin "2") (pinfunction "2_2") (pintype "passive"))
      (node (ref "R27") (pin "2") (pinfunction "2_2") (pintype "passive"))
      (node (ref "R28") (pin "2") (pinfunction "2_2") (pintype "passive"))
      (node (ref "R29") (pin "2") (pinfunction "2_2") (pintype "passive"))
      (node (ref "R3") (pin "2") (pinfunction "2_2") (pintype "passive"))
      (node (ref "R30") (pin "2") (pinfunction "2_2") (pintype "passive"))
      (node (ref "R31") (pin "2") (pinfunction "2_2") (pintype "passive"))
      (node (ref "R32") (pin "2") (pinfunction "2_2") (pintype "passive"))
      (node (ref "R33") (pin "2") (pinfunction "2_2") (pintype "passive"))
      (node (ref "R34") (pin "2") (pinfunction "2_2") (pintype "passive"))
      (node (ref "R35") (pin "2") (pinfunction "2_2") (pintype "passive"))
      (node (ref "R36") (pin "2") (pinfunction "2_2") (pintype "passive"))
      (node (ref "R37") (pin "2") (pinfunction "2_2") (pintype "passive"))
      (node (ref "R38") (pin "2") (pinfunction "2_2") (pintype "passive"))
      (node (ref "R39") (pin "2") (pinfunction "2_2") (pintype "passive"))
      (node (ref "R4") (pin "2") (pinfunction "2_2") (pintype "passive"))
      (node (ref "R40") (pin "2") (pinfunction "2_2") (pintype "passive"))
      (node (ref "R41") (pin "2") (pinfunction "2_2") (pintype "passive"))
      (node (ref "R42") (pin "2") (pinfunction "2_2") (pintype "passive"))
      (node (ref "R43") (pin "2") (pinfunction "2_2") (pintype "passive"))
      (node (ref "R44") (pin "2") (pinfunction "2_2") (pintype "passive"))
      (node (ref "R45") (pin "2") (pinfunction "2_2") (pintype "passive"))
      (node (ref "R46") (pin "2") (pinfunction "2_2") (pintype "passive"))
      (node (ref "R47") (pin "2") (pinfunction "2_2") (pintype "passive"))
      (node (ref "R48") (pin "2") (pinfunction "2_2") (pintype "passive"))
      (node (ref "R49") (pin "2") (pinfunction "2_2") (pintype "passive"))
      (node (ref "R5") (pin "2") (pinfunction "2_2") (pintype "passive"))
      (node (ref "R50") (pin "2") (pinfunction "2_2") (pintype "passive"))
      (node (ref "R6") (pin "2") (pinfunction "2_2") (pintype "passive"))
      (node (ref "R7") (pin "2") (pinfunction "2_2") (pintype "passive"))
      (node (ref "R8") (pin "2") (pinfunction "2_2") (pintype "passive"))
      (node (ref "R9") (pin "2") (pinfunction "2_2") (pintype "passive"))
      (node (ref "RA") (pin "1") (pinfunction "1_1") (pintype "passive"))
      (node (ref "RL") (pin "1") (pinfunction "1_1") (pintype "passive"))
      (node (ref "RS08") (pin "2") (pinfunction "2_2") (pintype "passive"))
    )
    (net (code "247") (name "WLS") (class "Default")
      (node (ref "IC37") (pin "4") (pinfunction "A2_4") (pintype "input"))
      (node (ref "IC44") (pin "11") (pinfunction "I_11") (pintype "input"))
      (node (ref "IC9") (pin "5") (pinfunction "Q_5") (pintype "output"))
    )
    (net (code "248") (name "WRITING") (class "Default")
      (node (ref "IC10") (pin "5") (pinfunction "Q_5") (pintype "output"))
      (node (ref "IC41") (pin "13") (pinfunction "B_13") (pintype "input"))
      (node (ref "IC41") (pin "14") (pinfunction "A_14") (pintype "input"))
      (node (ref "IC42") (pin "11") (pinfunction "I_11") (pintype "input"))
      (node (ref "IC6") (pin "2") (pinfunction "A_2") (pintype "input"))
      (node (ref "RS08") (pin "18") (pinfunction "18_18") (pintype "passive"))
    )
    (net (code "249") (name "unconnected-(C35L-Pad20)") (class "Default")
      (node (ref "C35L") (pin "20") (pinfunction "20_20") (pintype "passive"))
    )
    (net (code "250") (name "unconnected-(C35L-Pad40)") (class "Default")
      (node (ref "C35L") (pin "40") (pinfunction "40_40") (pintype "passive"))
    )
    (net (code "251") (name "unconnected-(C36L-Pad20)") (class "Default")
      (node (ref "C36L") (pin "20") (pinfunction "20_20") (pintype "passive"))
    )
    (net (code "252") (name "unconnected-(C36L-Pad40)") (class "Default")
      (node (ref "C36L") (pin "40") (pinfunction "40_40") (pintype "passive"))
    )
    (net (code "253") (name "unconnected-(D34L-Pad20)") (class "Default")
      (node (ref "D34L") (pin "20") (pinfunction "20_20") (pintype "passive"))
    )
    (net (code "254") (name "unconnected-(D34L-Pad36)") (class "Default")
      (node (ref "D34L") (pin "36") (pinfunction "36_36") (pintype "passive"))
    )
    (net (code "255") (name "unconnected-(D34L-Pad38)") (class "Default")
      (node (ref "D34L") (pin "38") (pinfunction "38_38") (pintype "passive"))
    )
    (net (code "256") (name "unconnected-(D34L-Pad40)") (class "Default")
      (node (ref "D34L") (pin "40") (pinfunction "40_40") (pintype "passive"))
    )
    (net (code "257") (name "unconnected-(D35L-Pad20)") (class "Default")
      (node (ref "D35L") (pin "20") (pinfunction "20_20") (pintype "passive"))
    )
    (net (code "258") (name "unconnected-(D35L-Pad40)") (class "Default")
      (node (ref "D35L") (pin "40") (pinfunction "40_40") (pintype "passive"))
    )
    (net (code "259") (name "unconnected-(D36L-Pad20)") (class "Default")
      (node (ref "D36L") (pin "20") (pinfunction "20_20") (pintype "passive"))
    )
    (net (code "260") (name "unconnected-(D36L-Pad40)") (class "Default")
      (node (ref "D36L") (pin "40") (pinfunction "40_40") (pintype "passive"))
    )
    (net (code "261") (name "unconnected-(DAR4-7A-BO-Pad13)") (class "Default")
      (node (ref "DAR4-7") (pin "13") (pinfunction "BO_13") (pintype "output"))
    )
    (net (code "262") (name "unconnected-(DAR4-7A-CO-Pad12)") (class "Default")
      (node (ref "DAR4-7") (pin "12") (pinfunction "CO_12") (pintype "output"))
    )
    (net (code "263") (name "unconnected-(DAR8-11A-BO-Pad13)") (class "Default")
      (node (ref "DAR8-11") (pin "13") (pinfunction "BO_13") (pintype "output"))
    )
    (net (code "264") (name "unconnected-(DMA0-3A-BO-Pad13)") (class "Default")
      (node (ref "DMA0-3") (pin "13") (pinfunction "BO_13") (pintype "output"))
    )
    (net (code "265") (name "unconnected-(DMA4-7A-BO-Pad13)") (class "Default")
      (node (ref "DMA4-7") (pin "13") (pinfunction "BO_13") (pintype "output"))
    )
    (net (code "266") (name "unconnected-(DMA8-11A-BO-Pad13)") (class "Default")
      (node (ref "DMA8-11") (pin "13") (pinfunction "BO_13") (pintype "output"))
    )
    (net (code "267") (name "unconnected-(FIELDA-BO-Pad13)") (class "Default")
      (node (ref "FIELD") (pin "13") (pinfunction "BO_13") (pintype "output"))
    )
    (net (code "268") (name "unconnected-(FIELDA-CO-Pad12)") (class "Default")
      (node (ref "FIELD") (pin "12") (pinfunction "CO_12") (pintype "output"))
    )
    (net (code "269") (name "unconnected-(FIELDA-QD-Pad7)") (class "Default")
      (node (ref "FIELD") (pin "7") (pinfunction "QD_7") (pintype "output"))
    )
    (net (code "270") (name "unconnected-(IC1A-W-Pad6)") (class "Default")
      (node (ref "IC1") (pin "6") (pinfunction "W_6") (pintype "output"))
    )
    (net (code "271") (name "unconnected-(IC2A-W-Pad6)") (class "Default")
      (node (ref "IC2") (pin "6") (pinfunction "W_6") (pintype "output"))
    )
    (net (code "272") (name "unconnected-(IC3A-W-Pad6)") (class "Default")
      (node (ref "IC3") (pin "6") (pinfunction "W_6") (pintype "output"))
    )
    (net (code "273") (name "unconnected-(IC4A-W-Pad6)") (class "Default")
      (node (ref "IC4") (pin "6") (pinfunction "W_6") (pintype "output"))
    )
    (net (code "274") (name "unconnected-(IC6A-Y0-Pad4)") (class "Default")
      (node (ref "IC6") (pin "4") (pinfunction "Y0_4") (pintype "output"))
    )
    (net (code "275") (name "unconnected-(IC6A-Y2-Pad6)") (class "Default")
      (node (ref "IC6") (pin "6") (pinfunction "Y2_6") (pintype "output"))
    )
    (net (code "276") (name "unconnected-(IC7A-Y0-Pad4)") (class "Default")
      (node (ref "IC7") (pin "4") (pinfunction "Y0_4") (pintype "output"))
    )
    (net (code "277") (name "unconnected-(IC7A-Y2-Pad6)") (class "Default")
      (node (ref "IC7") (pin "6") (pinfunction "Y2_6") (pintype "output"))
    )
    (net (code "278") (name "unconnected-(IC7A-Y3-Pad7)") (class "Default")
      (node (ref "IC7") (pin "7") (pinfunction "Y3_7") (pintype "output"))
    )
    (net (code "279") (name "unconnected-(IC7B-Y1-Pad11)") (class "Default")
      (node (ref "IC7") (pin "11") (pinfunction "Y1_11") (pintype "output"))
    )
    (net (code "280") (name "unconnected-(IC7B-Y2-Pad10)") (class "Default")
      (node (ref "IC7") (pin "10") (pinfunction "Y2_10") (pintype "output"))
    )
    (net (code "281") (name "unconnected-(IC7B-Y3-Pad9)") (class "Default")
      (node (ref "IC7") (pin "9") (pinfunction "Y3_9") (pintype "output"))
    )
    (net (code "282") (name "unconnected-(IC10A-~{Q}-Pad6)") (class "Default")
      (node (ref "IC10") (pin "6") (pinfunction "~{Q}_6") (pintype "output"))
    )
    (net (code "283") (name "unconnected-(IC11A-Q-Pad5)") (class "Default")
      (node (ref "IC11") (pin "5") (pinfunction "Q_5") (pintype "output"))
    )
    (net (code "284") (name "unconnected-(IC11B-~{Q}-Pad8)") (class "Default")
      (node (ref "IC11") (pin "8") (pinfunction "~{Q}_8") (pintype "output"))
    )
    (net (code "285") (name "unconnected-(IC13A-ODD-Pad6)") (class "Default")
      (node (ref "IC13") (pin "6") (pinfunction "ODD_6") (pintype "output"))
    )
    (net (code "286") (name "unconnected-(IC14A-EVN-Pad5)") (class "Default")
      (node (ref "IC14") (pin "5") (pinfunction "EVN_5") (pintype "output"))
    )
    (net (code "287") (name "unconnected-(IC15A-EVN-Pad5)") (class "Default")
      (node (ref "IC15") (pin "5") (pinfunction "EVN_5") (pintype "output"))
    )
    (net (code "288") (name "unconnected-(IC16A-Y1-Pad5)") (class "Default")
      (node (ref "IC16") (pin "5") (pinfunction "Y1_5") (pintype "output"))
    )
    (net (code "289") (name "unconnected-(IC16A-Y2-Pad6)") (class "Default")
      (node (ref "IC16") (pin "6") (pinfunction "Y2_6") (pintype "output"))
    )
    (net (code "290") (name "unconnected-(IC16A-Y3-Pad7)") (class "Default")
      (node (ref "IC16") (pin "7") (pinfunction "Y3_7") (pintype "output"))
    )
    (net (code "291") (name "unconnected-(IC16B-Y2-Pad10)") (class "Default")
      (node (ref "IC16") (pin "10") (pinfunction "Y2_10") (pintype "output"))
    )
    (net (code "292") (name "unconnected-(IC16B-Y3-Pad9)") (class "Default")
      (node (ref "IC16") (pin "9") (pinfunction "Y3_9") (pintype "output"))
    )
    (net (code "293") (name "unconnected-(IC17A-Y1-Pad5)") (class "Default")
      (node (ref "IC17") (pin "5") (pinfunction "Y1_5") (pintype "output"))
    )
    (net (code "294") (name "unconnected-(IC17A-Y2-Pad6)") (class "Default")
      (node (ref "IC17") (pin "6") (pinfunction "Y2_6") (pintype "output"))
    )
    (net (code "295") (name "unconnected-(IC17A-Y3-Pad7)") (class "Default")
      (node (ref "IC17") (pin "7") (pinfunction "Y3_7") (pintype "output"))
    )
    (net (code "296") (name "unconnected-(IC17B-Y2-Pad10)") (class "Default")
      (node (ref "IC17") (pin "10") (pinfunction "Y2_10") (pintype "output"))
    )
    (net (code "297") (name "unconnected-(IC17B-Y3-Pad9)") (class "Default")
      (node (ref "IC17") (pin "9") (pinfunction "Y3_9") (pintype "output"))
    )
    (net (code "298") (name "unconnected-(IC20B-Y4-Pad3)") (class "Default")
      (node (ref "IC20") (pin "3") (pinfunction "Y4_3") (pintype "tri_state"))
    )
    (net (code "299") (name "unconnected-(IC21B-Y0-Pad12)") (class "Default")
      (node (ref "IC21") (pin "12") (pinfunction "Y0_12") (pintype "output"))
    )
    (net (code "300") (name "unconnected-(IC21B-Y1-Pad11)") (class "Default")
      (node (ref "IC21") (pin "11") (pinfunction "Y1_11") (pintype "output"))
    )
    (net (code "301") (name "unconnected-(IC21B-Y2-Pad10)") (class "Default")
      (node (ref "IC21") (pin "10") (pinfunction "Y2_10") (pintype "output"))
    )
    (net (code "302") (name "unconnected-(IC25A-Y3-Pad12)") (class "Default")
      (node (ref "IC25") (pin "12") (pinfunction "Y3_12") (pintype "output"))
    )
    (net (code "303") (name "unconnected-(IC25A-Y5-Pad10)") (class "Default")
      (node (ref "IC25") (pin "10") (pinfunction "Y5_10") (pintype "output"))
    )
    (net (code "304") (name "unconnected-(IC25A-Y6-Pad9)") (class "Default")
      (node (ref "IC25") (pin "9") (pinfunction "Y6_9") (pintype "output"))
    )
    (net (code "305") (name "unconnected-(IC25A-Y7-Pad7)") (class "Default")
      (node (ref "IC25") (pin "7") (pinfunction "Y7_7") (pintype "output"))
    )
    (net (code "306") (name "unconnected-(IC29A-Y3-Pad12)") (class "Default")
      (node (ref "IC29") (pin "12") (pinfunction "Y3_12") (pintype "output"))
    )
    (net (code "307") (name "unconnected-(IC29A-Y5-Pad10)") (class "Default")
      (node (ref "IC29") (pin "10") (pinfunction "Y5_10") (pintype "output"))
    )
    (net (code "308") (name "unconnected-(IC29A-Y6-Pad9)") (class "Default")
      (node (ref "IC29") (pin "9") (pinfunction "Y6_9") (pintype "output"))
    )
    (net (code "309") (name "unconnected-(IC29A-Y7-Pad7)") (class "Default")
      (node (ref "IC29") (pin "7") (pinfunction "Y7_7") (pintype "output"))
    )
    (net (code "310") (name "unconnected-(IC32A-Y3-Pad12)") (class "Default")
      (node (ref "IC32") (pin "12") (pinfunction "Y3_12") (pintype "output"))
    )
    (net (code "311") (name "unconnected-(IC32A-Y5-Pad10)") (class "Default")
      (node (ref "IC32") (pin "10") (pinfunction "Y5_10") (pintype "output"))
    )
    (net (code "312") (name "unconnected-(IC32A-Y6-Pad9)") (class "Default")
      (node (ref "IC32") (pin "9") (pinfunction "Y6_9") (pintype "output"))
    )
    (net (code "313") (name "unconnected-(IC32A-Y7-Pad7)") (class "Default")
      (node (ref "IC32") (pin "7") (pinfunction "Y7_7") (pintype "output"))
    )
    (net (code "314") (name "unconnected-(IC35B-Y2-Pad7)") (class "Default")
      (node (ref "IC35") (pin "7") (pinfunction "Y2_7") (pintype "tri_state"))
    )
    (net (code "315") (name "unconnected-(IC35B-Y3-Pad5)") (class "Default")
      (node (ref "IC35") (pin "5") (pinfunction "Y3_5") (pintype "tri_state"))
    )
    (net (code "316") (name "unconnected-(IC35B-Y4-Pad3)") (class "Default")
      (node (ref "IC35") (pin "3") (pinfunction "Y4_3") (pintype "tri_state"))
    )
    (net (code "317") (name "unconnected-(IC41A-Y1-Pad5)") (class "Default")
      (node (ref "IC41") (pin "5") (pinfunction "Y1_5") (pintype "output"))
    )
    (net (code "318") (name "unconnected-(IC41A-Y2-Pad6)") (class "Default")
      (node (ref "IC41") (pin "6") (pinfunction "Y2_6") (pintype "output"))
    )
    (net (code "319") (name "unconnected-(IC41B-Y1-Pad11)") (class "Default")
      (node (ref "IC41") (pin "11") (pinfunction "Y1_11") (pintype "output"))
    )
    (net (code "320") (name "unconnected-(IC41B-Y2-Pad10)") (class "Default")
      (node (ref "IC41") (pin "10") (pinfunction "Y2_10") (pintype "output"))
    )
    (net (code "321") (name "unconnected-(INTENBA-BO-Pad13)") (class "Default")
      (node (ref "INTENB") (pin "13") (pinfunction "BO_13") (pintype "output"))
    )
    (net (code "322") (name "unconnected-(INTENBA-CO-Pad12)") (class "Default")
      (node (ref "INTENB") (pin "12") (pinfunction "CO_12") (pintype "output"))
    )
    (net (code "323") (name "unconnected-(INTENBA-QD-Pad7)") (class "Default")
      (node (ref "INTENB") (pin "7") (pinfunction "QD_7") (pintype "output"))
    )
    (net (code "324") (name "~{3CYC}") (class "Default")
      (node (ref "C35L") (pin "28") (pinfunction "28_28") (pintype "passive"))
      (node (ref "J2") (pin "1") (pinfunction "1_1") (pintype "passive"))
    )
    (net (code "325") (name "~{601}") (class "Default")
      (node (ref "IC11") (pin "13") (pinfunction "CLR_13") (pintype "input"))
      (node (ref "IC18") (pin "4") (pinfunction "I0_4") (pintype "input"))
      (node (ref "IC18") (pin "5") (pinfunction "I1_5") (pintype "input"))
      (node (ref "IC23") (pin "1") (pinfunction "CLR_1") (pintype "input"))
      (node (ref "IC32") (pin "15") (pinfunction "Y0_15") (pintype "output"))
      (node (ref "IC9") (pin "1") (pinfunction "CLR_1") (pintype "input"))
      (node (ref "IC9") (pin "13") (pinfunction "CLR_13") (pintype "input"))
    )
    (net (code "326") (name "~{602}") (class "Default")
      (node (ref "IC10") (pin "1") (pinfunction "CLR_1") (pintype "input"))
      (node (ref "IC18") (pin "1") (pinfunction "I0_1") (pintype "input"))
      (node (ref "IC18") (pin "12") (pinfunction "I0_12") (pintype "input"))
      (node (ref "IC29") (pin "15") (pinfunction "Y0_15") (pintype "output"))
    )
    (net (code "327") (name "~{604}") (class "Default")
      (node (ref "IC10") (pin "4") (pinfunction "PRE_4") (pintype "input"))
      (node (ref "IC18") (pin "13") (pinfunction "I1_13") (pintype "input"))
      (node (ref "IC18") (pin "2") (pinfunction "I1_2") (pintype "input"))
      (node (ref "IC25") (pin "15") (pinfunction "Y0_15") (pintype "output"))
    )
    (net (code "328") (name "~{611}") (class "Default")
      (node (ref "FIELD") (pin "14") (pinfunction "CLR_14") (pintype "input"))
      (node (ref "IC32") (pin "14") (pinfunction "Y1_14") (pintype "output"))
      (node (ref "INTENB") (pin "14") (pinfunction "CLR_14") (pintype "input"))
    )
    (net (code "329") (name "~{612}") (class "Default")
      (node (ref "IC19") (pin "5") (pinfunction "I_5") (pintype "input"))
      (node (ref "IC29") (pin "14") (pinfunction "Y1_14") (pintype "output"))
    )
    (net (code "330") (name "~{614}") (class "Default")
      (node (ref "IC17") (pin "13") (pinfunction "B_13") (pintype "input"))
      (node (ref "IC22") (pin "3") (pinfunction "I_3") (pintype "input"))
      (node (ref "IC25") (pin "14") (pinfunction "Y1_14") (pintype "output"))
    )
    (net (code "331") (name "~{621}") (class "Default")
      (node (ref "IC32") (pin "13") (pinfunction "Y2_13") (pintype "output"))
      (node (ref "IC7") (pin "3") (pinfunction "B_3") (pintype "input"))
    )
    (net (code "332") (name "~{622}") (class "Default")
      (node (ref "IC29") (pin "13") (pinfunction "Y2_13") (pintype "output"))
      (node (ref "IC7") (pin "13") (pinfunction "B_13") (pintype "input"))
    )
    (net (code "333") (name "~{624}") (class "Default")
      (node (ref "IC22") (pin "13") (pinfunction "I_13") (pintype "input"))
      (node (ref "IC24") (pin "1") (pinfunction "G_1") (pintype "input"))
      (node (ref "IC25") (pin "13") (pinfunction "Y2_13") (pintype "output"))
      (node (ref "IC31") (pin "1") (pinfunction "G_1") (pintype "input"))
      (node (ref "IC38") (pin "1") (pinfunction "G_1") (pintype "input"))
    )
    (net (code "334") (name "~{641}") (class "Default")
      (node (ref "IC16") (pin "13") (pinfunction "B_13") (pintype "input"))
      (node (ref "IC32") (pin "11") (pinfunction "Y4_11") (pintype "output"))
    )
    (net (code "335") (name "~{642}") (class "Default")
      (node (ref "DAR4-7") (pin "11") (pinfunction "LD_11") (pintype "input"))
      (node (ref "DAR8-11") (pin "11") (pinfunction "LD_11") (pintype "input"))
      (node (ref "IC29") (pin "11") (pinfunction "Y4_11") (pintype "output"))
    )
    (net (code "336") (name "~{644}") (class "Default")
      (node (ref "IC16") (pin "3") (pinfunction "B_3") (pintype "input"))
      (node (ref "IC25") (pin "11") (pinfunction "Y4_11") (pintype "output"))
    )
    (net (code "337") (name "~{645}") (class "Default")
      (node (ref "IC16") (pin "4") (pinfunction "Y0_4") (pintype "output"))
      (node (ref "IC24") (pin "19") (pinfunction "G_19") (pintype "input"))
      (node (ref "IC31") (pin "19") (pinfunction "G_19") (pintype "input"))
      (node (ref "IC38") (pin "19") (pinfunction "G_19") (pintype "input"))
    )
    (net (code "338") (name "~{ACB00}") (class "Default")
      (node (ref "D34L") (pin "2") (pinfunction "2_2") (pintype "passive"))
      (node (ref "IC37") (pin "12") (pinfunction "Y4_12") (pintype "tri_state"))
      (node (ref "IC38") (pin "12") (pinfunction "Y4_12") (pintype "tri_state"))
      (node (ref "IC38") (pin "3") (pinfunction "Y4_3") (pintype "tri_state"))
    )
    (net (code "339") (name "~{ACB01}") (class "Default")
      (node (ref "D34L") (pin "4") (pinfunction "4_4") (pintype "passive"))
      (node (ref "IC37") (pin "14") (pinfunction "Y3_14") (pintype "tri_state"))
      (node (ref "IC38") (pin "14") (pinfunction "Y3_14") (pintype "tri_state"))
      (node (ref "IC38") (pin "5") (pinfunction "Y3_5") (pintype "tri_state"))
    )
    (net (code "340") (name "~{ACB02}") (class "Default")
      (node (ref "D34L") (pin "6") (pinfunction "6_6") (pintype "passive"))
      (node (ref "IC37") (pin "16") (pinfunction "Y2_16") (pintype "tri_state"))
      (node (ref "IC38") (pin "16") (pinfunction "Y2_16") (pintype "tri_state"))
      (node (ref "IC38") (pin "7") (pinfunction "Y2_7") (pintype "tri_state"))
    )
    (net (code "341") (name "~{ACB03}") (class "Default")
      (node (ref "D34L") (pin "8") (pinfunction "8_8") (pintype "passive"))
      (node (ref "IC37") (pin "18") (pinfunction "Y1_18") (pintype "tri_state"))
      (node (ref "IC38") (pin "18") (pinfunction "Y1_18") (pintype "tri_state"))
      (node (ref "IC38") (pin "9") (pinfunction "Y1_9") (pintype "tri_state"))
    )
    (net (code "342") (name "~{ACB04}") (class "Default")
      (node (ref "D34L") (pin "10") (pinfunction "10_10") (pintype "passive"))
      (node (ref "IC30") (pin "3") (pinfunction "Y4_3") (pintype "tri_state"))
      (node (ref "IC31") (pin "12") (pinfunction "Y4_12") (pintype "tri_state"))
      (node (ref "IC31") (pin "3") (pinfunction "Y4_3") (pintype "tri_state"))
    )
    (net (code "343") (name "~{ACB05}") (class "Default")
      (node (ref "D34L") (pin "12") (pinfunction "12_12") (pintype "passive"))
      (node (ref "IC30") (pin "5") (pinfunction "Y3_5") (pintype "tri_state"))
      (node (ref "IC31") (pin "14") (pinfunction "Y3_14") (pintype "tri_state"))
      (node (ref "IC31") (pin "5") (pinfunction "Y3_5") (pintype "tri_state"))
    )
    (net (code "344") (name "~{ACB06}") (class "Default")
      (node (ref "D34L") (pin "14") (pinfunction "14_14") (pintype "passive"))
      (node (ref "IC30") (pin "7") (pinfunction "Y2_7") (pintype "tri_state"))
      (node (ref "IC31") (pin "16") (pinfunction "Y2_16") (pintype "tri_state"))
      (node (ref "IC31") (pin "7") (pinfunction "Y2_7") (pintype "tri_state"))
    )
    (net (code "345") (name "~{ACB07}") (class "Default")
      (node (ref "D34L") (pin "16") (pinfunction "16_16") (pintype "passive"))
      (node (ref "IC30") (pin "9") (pinfunction "Y1_9") (pintype "tri_state"))
      (node (ref "IC31") (pin "18") (pinfunction "Y1_18") (pintype "tri_state"))
      (node (ref "IC31") (pin "9") (pinfunction "Y1_9") (pintype "tri_state"))
    )
    (net (code "346") (name "~{ACB08}") (class "Default")
      (node (ref "D34L") (pin "18") (pinfunction "18_18") (pintype "passive"))
      (node (ref "IC24") (pin "12") (pinfunction "Y4_12") (pintype "tri_state"))
      (node (ref "IC24") (pin "3") (pinfunction "Y4_3") (pintype "tri_state"))
      (node (ref "IC30") (pin "12") (pinfunction "Y4_12") (pintype "tri_state"))
    )
    (net (code "347") (name "~{ACB09}") (class "Default")
      (node (ref "D34L") (pin "22") (pinfunction "22_22") (pintype "passive"))
      (node (ref "IC24") (pin "14") (pinfunction "Y3_14") (pintype "tri_state"))
      (node (ref "IC24") (pin "5") (pinfunction "Y3_5") (pintype "tri_state"))
      (node (ref "IC30") (pin "14") (pinfunction "Y3_14") (pintype "tri_state"))
    )
    (net (code "348") (name "~{ACB10}") (class "Default")
      (node (ref "D34L") (pin "24") (pinfunction "24_24") (pintype "passive"))
      (node (ref "IC24") (pin "16") (pinfunction "Y2_16") (pintype "tri_state"))
      (node (ref "IC24") (pin "7") (pinfunction "Y2_7") (pintype "tri_state"))
      (node (ref "IC30") (pin "16") (pinfunction "Y2_16") (pintype "tri_state"))
    )
    (net (code "349") (name "~{ACB11}") (class "Default")
      (node (ref "D34L") (pin "26") (pinfunction "26_26") (pintype "passive"))
      (node (ref "IC24") (pin "18") (pinfunction "Y1_18") (pintype "tri_state"))
      (node (ref "IC24") (pin "9") (pinfunction "Y1_9") (pintype "tri_state"))
      (node (ref "IC30") (pin "18") (pinfunction "Y1_18") (pintype "tri_state"))
    )
    (net (code "350") (name "~{ACCLEAR}") (class "Default")
      (node (ref "D34L") (pin "32") (pinfunction "32_32") (pintype "passive"))
      (node (ref "IC22") (pin "12") (pinfunction "O_12") (pintype "open_collector"))
      (node (ref "IC22") (pin "2") (pinfunction "O_2") (pintype "open_collector"))
      (node (ref "IC22") (pin "4") (pinfunction "O_4") (pintype "open_collector"))
    )
    (net (code "351") (name "~{BADDAC}") (class "Default")
      (node (ref "C36L") (pin "34") (pinfunction "34_34") (pintype "passive"))
      (node (ref "IC11") (pin "1") (pinfunction "CLR_1") (pintype "input"))
    )
    (net (code "352") (name "~{BBREAK}") (class "Default")
      (node (ref "C36L") (pin "32") (pinfunction "32_32") (pintype "passive"))
      (node (ref "DMA8-11") (pin "5") (pinfunction "UP_5") (pintype "input"))
      (node (ref "IC20") (pin "19") (pinfunction "G_19") (pintype "input"))
      (node (ref "IC21") (pin "15") (pinfunction "G_15") (pintype "input"))
      (node (ref "IC41") (pin "1") (pinfunction "G_1") (pintype "input"))
      (node (ref "IC41") (pin "15") (pinfunction "G_15") (pintype "input"))
      (node (ref "IC42") (pin "13") (pinfunction "I_13") (pintype "input"))
      (node (ref "IC6") (pin "1") (pinfunction "G_1") (pintype "input"))
    )
    (net (code "353") (name "~{BMB03}") (class "Default")
      (node (ref "D35L") (pin "8") (pinfunction "8_8") (pintype "passive"))
    )
    (net (code "354") (name "~{BMB04}") (class "Default")
      (node (ref "D35L") (pin "12") (pinfunction "12_12") (pintype "passive"))
    )
    (net (code "355") (name "~{BMB05}") (class "Default")
      (node (ref "D35L") (pin "16") (pinfunction "16_16") (pintype "passive"))
    )
    (net (code "356") (name "~{BMB06}") (class "Default")
      (node (ref "D35L") (pin "22") (pinfunction "22_22") (pintype "passive"))
    )
    (net (code "357") (name "~{BMB07}") (class "Default")
      (node (ref "D35L") (pin "26") (pinfunction "26_26") (pintype "passive"))
    )
    (net (code "358") (name "~{BMB08}") (class "Default")
      (node (ref "D35L") (pin "30") (pinfunction "30_30") (pintype "passive"))
    )
    (net (code "359") (name "~{BRK_RQ}") (class "Default")
      (node (ref "C36L") (pin "28") (pinfunction "28_28") (pintype "passive"))
      (node (ref "IC11") (pin "6") (pinfunction "~{Q}_6") (pintype "output"))
    )
    (net (code "360") (name "~{BRUN}") (class "Default")
      (node (ref "D34L") (pin "34") (pinfunction "34_34") (pintype "passive"))
    )
    (net (code "361") (name "~{BWCO}") (class "Default")
      (node (ref "C35L") (pin "32") (pinfunction "32_32") (pintype "passive"))
      (node (ref "IC10") (pin "13") (pinfunction "CLR_13") (pintype "input"))
      (node (ref "IC11") (pin "12") (pinfunction "D_12") (pintype "input"))
      (node (ref "IC44") (pin "9") (pinfunction "I_9") (pintype "input"))
    )
    (net (code "362") (name "~{DA00}") (class "Default")
      (node (ref "C36L") (pin "2") (pinfunction "2_2") (pintype "passive"))
      (node (ref "J14") (pin "1") (pinfunction "1_1") (pintype "passive"))
    )
    (net (code "363") (name "~{DA01}") (class "Default")
      (node (ref "C36L") (pin "4") (pinfunction "4_4") (pintype "passive"))
      (node (ref "J13") (pin "1") (pinfunction "1_1") (pintype "passive"))
    )
    (net (code "364") (name "~{DA02}") (class "Default")
      (node (ref "C36L") (pin "6") (pinfunction "6_6") (pintype "passive"))
      (node (ref "J12") (pin "1") (pinfunction "1_1") (pintype "passive"))
    )
    (net (code "365") (name "~{DA03}") (class "Default")
      (node (ref "C36L") (pin "8") (pinfunction "8_8") (pintype "passive"))
      (node (ref "J11") (pin "1") (pinfunction "1_1") (pintype "passive"))
    )
    (net (code "366") (name "~{DA04}") (class "Default")
      (node (ref "C36L") (pin "10") (pinfunction "10_10") (pintype "passive"))
      (node (ref "J10") (pin "1") (pinfunction "1_1") (pintype "passive"))
    )
    (net (code "367") (name "~{DA05}") (class "Default")
      (node (ref "C36L") (pin "12") (pinfunction "12_12") (pintype "passive"))
      (node (ref "J9") (pin "1") (pinfunction "1_1") (pintype "passive"))
    )
    (net (code "368") (name "~{DA06}") (class "Default")
      (node (ref "C36L") (pin "14") (pinfunction "14_14") (pintype "passive"))
      (node (ref "J8") (pin "1") (pinfunction "1_1") (pintype "passive"))
    )
    (net (code "369") (name "~{DA07}") (class "Default")
      (node (ref "C36L") (pin "16") (pinfunction "16_16") (pintype "passive"))
      (node (ref "J7") (pin "1") (pinfunction "1_1") (pintype "passive"))
    )
    (net (code "370") (name "~{DA08}") (class "Default")
      (node (ref "C36L") (pin "18") (pinfunction "18_18") (pintype "passive"))
      (node (ref "J6") (pin "1") (pinfunction "1_1") (pintype "passive"))
    )
    (net (code "371") (name "~{DA09}") (class "Default")
      (node (ref "C36L") (pin "22") (pinfunction "22_22") (pintype "passive"))
      (node (ref "J5") (pin "1") (pinfunction "1_1") (pintype "passive"))
    )
    (net (code "372") (name "~{DA10}") (class "Default")
      (node (ref "C36L") (pin "24") (pinfunction "24_24") (pintype "passive"))
      (node (ref "J4") (pin "1") (pinfunction "1_1") (pintype "passive"))
    )
    (net (code "373") (name "~{DA11}") (class "Default")
      (node (ref "C36L") (pin "26") (pinfunction "26_26") (pintype "passive"))
      (node (ref "J3") (pin "1") (pinfunction "1_1") (pintype "passive"))
    )
    (net (code "374") (name "~{DATA00}") (class "Default")
      (node (ref "C35L") (pin "2") (pinfunction "2_2") (pintype "passive"))
      (node (ref "IC34") (pin "12") (pinfunction "Y4_12") (pintype "tri_state"))
    )
    (net (code "375") (name "~{DATA01}") (class "Default")
      (node (ref "C35L") (pin "4") (pinfunction "4_4") (pintype "passive"))
      (node (ref "IC34") (pin "14") (pinfunction "Y3_14") (pintype "tri_state"))
    )
    (net (code "376") (name "~{DATA02}") (class "Default")
      (node (ref "C35L") (pin "6") (pinfunction "6_6") (pintype "passive"))
      (node (ref "IC34") (pin "16") (pinfunction "Y2_16") (pintype "tri_state"))
    )
    (net (code "377") (name "~{DATA03}") (class "Default")
      (node (ref "C35L") (pin "8") (pinfunction "8_8") (pintype "passive"))
      (node (ref "IC34") (pin "18") (pinfunction "Y1_18") (pintype "tri_state"))
    )
    (net (code "378") (name "~{DATA04}") (class "Default")
      (node (ref "C35L") (pin "10") (pinfunction "10_10") (pintype "passive"))
      (node (ref "IC26") (pin "3") (pinfunction "Y4_3") (pintype "tri_state"))
    )
    (net (code "379") (name "~{DATA05}") (class "Default")
      (node (ref "C35L") (pin "12") (pinfunction "12_12") (pintype "passive"))
      (node (ref "IC26") (pin "5") (pinfunction "Y3_5") (pintype "tri_state"))
    )
    (net (code "380") (name "~{DATA06}") (class "Default")
      (node (ref "C35L") (pin "14") (pinfunction "14_14") (pintype "passive"))
      (node (ref "IC26") (pin "7") (pinfunction "Y2_7") (pintype "tri_state"))
    )
    (net (code "381") (name "~{DATA07}") (class "Default")
      (node (ref "C35L") (pin "16") (pinfunction "16_16") (pintype "passive"))
      (node (ref "IC26") (pin "9") (pinfunction "Y1_9") (pintype "tri_state"))
    )
    (net (code "382") (name "~{DATA08}") (class "Default")
      (node (ref "C35L") (pin "18") (pinfunction "18_18") (pintype "passive"))
      (node (ref "IC26") (pin "12") (pinfunction "Y4_12") (pintype "tri_state"))
    )
    (net (code "383") (name "~{DATA09}") (class "Default")
      (node (ref "C35L") (pin "22") (pinfunction "22_22") (pintype "passive"))
      (node (ref "IC26") (pin "14") (pinfunction "Y3_14") (pintype "tri_state"))
    )
    (net (code "384") (name "~{DATA10}") (class "Default")
      (node (ref "C35L") (pin "24") (pinfunction "24_24") (pintype "passive"))
      (node (ref "IC26") (pin "16") (pinfunction "Y2_16") (pintype "tri_state"))
    )
    (net (code "385") (name "~{DATA11}") (class "Default")
      (node (ref "C35L") (pin "26") (pinfunction "26_26") (pintype "passive"))
      (node (ref "IC26") (pin "18") (pinfunction "Y1_18") (pintype "tri_state"))
    )
    (net (code "386") (name "~{DCXA}") (class "Default")
      (node (ref "IC16") (pin "12") (pinfunction "Y0_12") (pintype "output"))
      (node (ref "IC18") (pin "10") (pinfunction "I1_10") (pintype "input"))
      (node (ref "IC18") (pin "9") (pinfunction "I0_9") (pintype "input"))
    )
    (net (code "387") (name "~{DIMA}") (class "Default")
      (node (ref "IC17") (pin "11") (pinfunction "Y1_11") (pintype "output"))
      (node (ref "IC30") (pin "1") (pinfunction "G_1") (pintype "input"))
      (node (ref "IC30") (pin "19") (pinfunction "G_19") (pintype "input"))
      (node (ref "IC37") (pin "1") (pinfunction "G_1") (pintype "input"))
    )
    (net (code "388") (name "~{DIML}") (class "Default")
      (node (ref "FIELD") (pin "11") (pinfunction "LD_11") (pintype "input"))
      (node (ref "IC17") (pin "12") (pinfunction "Y0_12") (pintype "output"))
      (node (ref "INTENB") (pin "11") (pinfunction "LD_11") (pintype "input"))
    )
    (net (code "389") (name "~{DMA-IN}") (class "Default")
      (node (ref "IC13") (pin "4") (pinfunction "OI_4") (pintype "input"))
      (node (ref "IC26") (pin "1") (pinfunction "G_1") (pintype "input"))
      (node (ref "IC26") (pin "19") (pinfunction "G_19") (pintype "input"))
      (node (ref "IC34") (pin "1") (pinfunction "G_1") (pintype "input"))
      (node (ref "IC41") (pin "12") (pinfunction "Y0_12") (pintype "output"))
    )
    (net (code "390") (name "~{DMA-OUT}") (class "Default")
      (node (ref "IC28") (pin "1") (pinfunction "G_1") (pintype "input"))
      (node (ref "IC28") (pin "19") (pinfunction "G_19") (pintype "input"))
      (node (ref "IC35") (pin "1") (pinfunction "G_1") (pintype "input"))
      (node (ref "IC35") (pin "19") (pinfunction "G_19") (pintype "input"))
      (node (ref "IC41") (pin "9") (pinfunction "Y3_9") (pintype "output"))
    )
    (net (code "391") (name "~{DRV01}") (class "Default")
      (node (ref "IC41") (pin "4") (pinfunction "Y0_4") (pintype "output"))
      (node (ref "RS08") (pin "38") (pinfunction "38_38") (pintype "passive"))
    )
    (net (code "392") (name "~{DRV23}") (class "Default")
      (node (ref "IC41") (pin "7") (pinfunction "Y3_7") (pintype "output"))
      (node (ref "RS08") (pin "22") (pinfunction "22_22") (pintype "passive"))
    )
    (net (code "393") (name "~{DRVOK}") (class "Default")
      (node (ref "IC21") (pin "13") (pinfunction "B_13") (pintype "input"))
      (node (ref "IC21") (pin "14") (pinfunction "A_14") (pintype "input"))
      (node (ref "R2") (pin "1") (pinfunction "1_1") (pintype "passive"))
      (node (ref "RS08") (pin "40") (pinfunction "40_40") (pintype "passive"))
    )
    (net (code "394") (name "~{EXAD0}") (class "Default")
      (node (ref "C35L") (pin "34") (pinfunction "34_34") (pintype "passive"))
      (node (ref "IC20") (pin "9") (pinfunction "Y1_9") (pintype "tri_state"))
    )
    (net (code "395") (name "~{EXAD1}") (class "Default")
      (node (ref "C35L") (pin "36") (pinfunction "36_36") (pintype "passive"))
      (node (ref "IC20") (pin "7") (pinfunction "Y2_7") (pintype "tri_state"))
    )
    (net (code "396") (name "~{EXAD2}") (class "Default")
      (node (ref "C35L") (pin "38") (pinfunction "38_38") (pintype "passive"))
      (node (ref "IC20") (pin "5") (pinfunction "Y3_5") (pintype "tri_state"))
    )
    (net (code "397") (name "~{INT_RQ}") (class "Default")
      (node (ref "D34L") (pin "30") (pinfunction "30_30") (pintype "passive"))
      (node (ref "IC40") (pin "3") (pinfunction "O_3") (pintype "open_collector"))
      (node (ref "IC40") (pin "6") (pinfunction "O_6") (pintype "open_collector"))
      (node (ref "IC40") (pin "8") (pinfunction "O_8") (pintype "open_collector"))
    )
    (net (code "398") (name "~{IOS}") (class "Default")
      (node (ref "D34L") (pin "28") (pinfunction "28_28") (pintype "passive"))
      (node (ref "IC22") (pin "10") (pinfunction "O_10") (pintype "open_collector"))
    )
    (net (code "399") (name "~{MEM_INC}") (class "Default")
      (node (ref "C36L") (pin "36") (pinfunction "36_36") (pintype "passive"))
    )
    (net (code "400") (name "~{MYDEV}") (class "Default")
      (node (ref "IC25") (pin "4") (pinfunction "G2A_4") (pintype "input"))
      (node (ref "IC29") (pin "4") (pinfunction "G2A_4") (pintype "input"))
      (node (ref "IC32") (pin "4") (pinfunction "G2A_4") (pintype "input"))
      (node (ref "PAD1") (pin "1") (pinfunction "P_1") (pintype "passive"))
    )
    (net (code "401") (name "~{NXD}") (class "Default")
      (node (ref "IC12") (pin "12") (pinfunction "I0_12") (pintype "input"))
      (node (ref "IC23") (pin "6") (pinfunction "~{Q}_6") (pintype "output"))
    )
    (net (code "402") (name "~{PER}") (class "Default")
      (node (ref "IC12") (pin "4") (pinfunction "I0_4") (pintype "input"))
      (node (ref "IC9") (pin "8") (pinfunction "~{Q}_8") (pintype "output"))
    )
    (net (code "403") (name "~{SETNXD}") (class "Default")
      (node (ref "IC21") (pin "9") (pinfunction "Y3_9") (pintype "output"))
      (node (ref "IC23") (pin "4") (pinfunction "PRE_4") (pintype "input"))
    )
    (net (code "404") (name "~{SETPER}") (class "Default")
      (node (ref "IC13") (pin "5") (pinfunction "EVN_5") (pintype "output"))
      (node (ref "IC9") (pin "10") (pinfunction "PRE_10") (pintype "input"))
    )
    (net (code "405") (name "~{SETWLS}") (class "Default")
      (node (ref "IC6") (pin "7") (pinfunction "Y3_7") (pintype "output"))
      (node (ref "IC9") (pin "4") (pinfunction "PRE_4") (pintype "input"))
    )
    (net (code "406") (name "~{SKIP}") (class "Default")
      (node (ref "IC17") (pin "2") (pinfunction "A_2") (pintype "input"))
      (node (ref "IC19") (pin "10") (pinfunction "O_10") (pintype "open_collector"))
      (node (ref "IC19") (pin "2") (pinfunction "O_2") (pintype "open_collector"))
      (node (ref "IC19") (pin "6") (pinfunction "O_6") (pintype "open_collector"))
      (node (ref "R1") (pin "1") (pinfunction "1_1") (pintype "passive"))
    )
    (net (code "407") (name "~{START}") (class "Default")
      (node (ref "DMA0-3") (pin "11") (pinfunction "LD_11") (pintype "input"))
      (node (ref "DMA4-7") (pin "11") (pinfunction "LD_11") (pintype "input"))
      (node (ref "DMA8-11") (pin "11") (pinfunction "LD_11") (pintype "input"))
      (node (ref "IC18") (pin "3") (pinfunction "O_3") (pintype "output"))
    )
    (net (code "408") (name "~{WE}") (class "Default")
      (node (ref "IC22") (pin "5") (pinfunction "I_5") (pintype "input"))
      (node (ref "IC6") (pin "5") (pinfunction "Y1_5") (pintype "output"))
      (node (ref "RS08") (pin "8") (pinfunction "8_8") (pintype "passive"))
    )
    (net (code "409") (name "~{WLS}") (class "Default")
      (node (ref "IC12") (pin "13") (pinfunction "I1_13") (pintype "input"))
      (node (ref "IC9") (pin "6") (pinfunction "~{Q}_6") (pintype "output"))
    )
  )
)
